# 5409057D.net
KiCad netlist of a schematic drawn in EAGLE
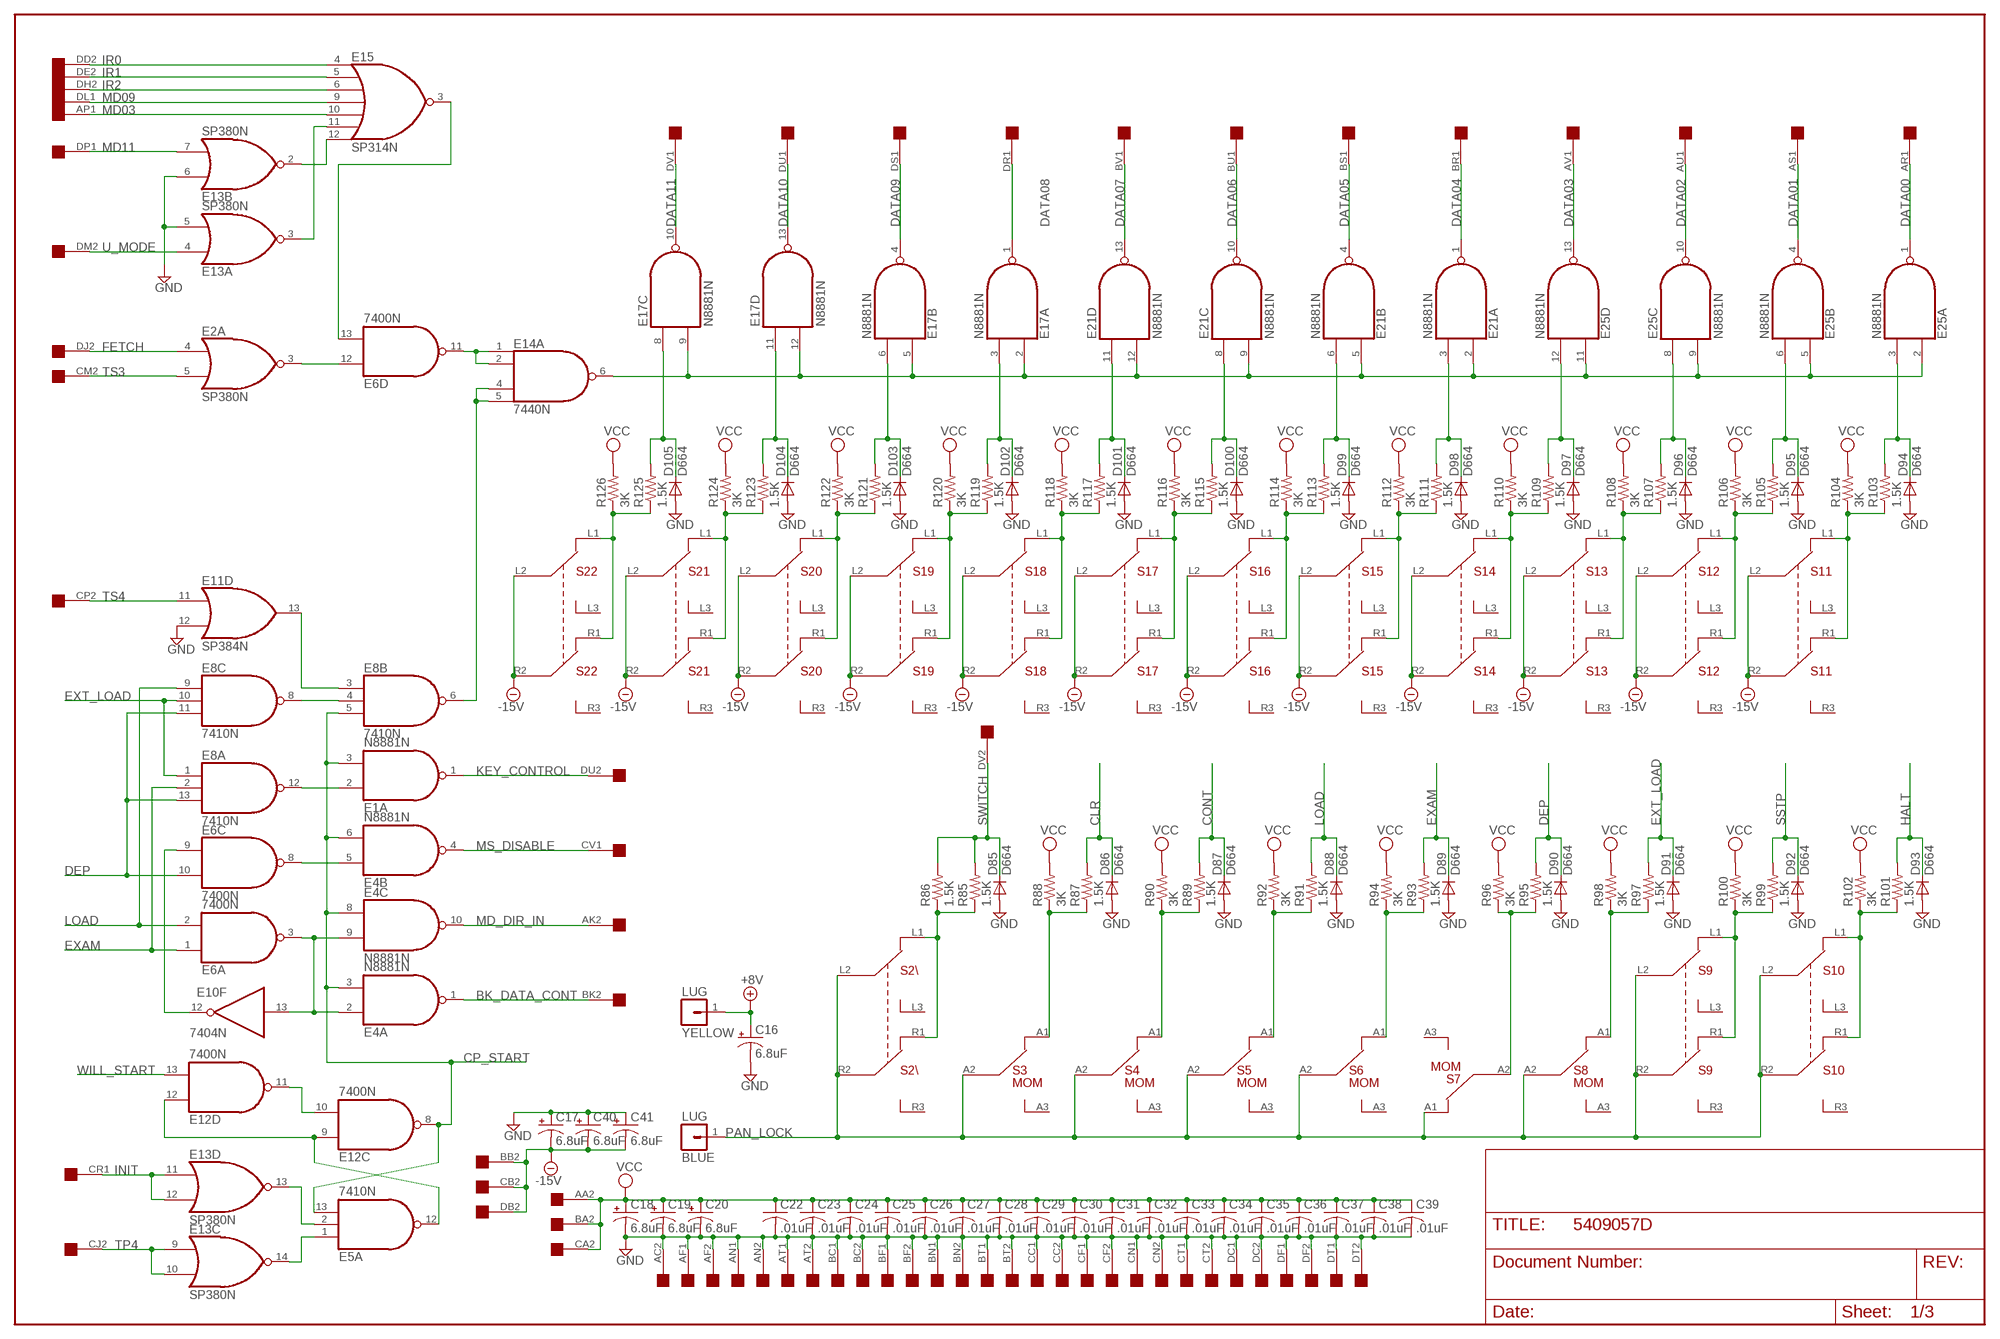
[diagram p0: schematic, sheet 1]
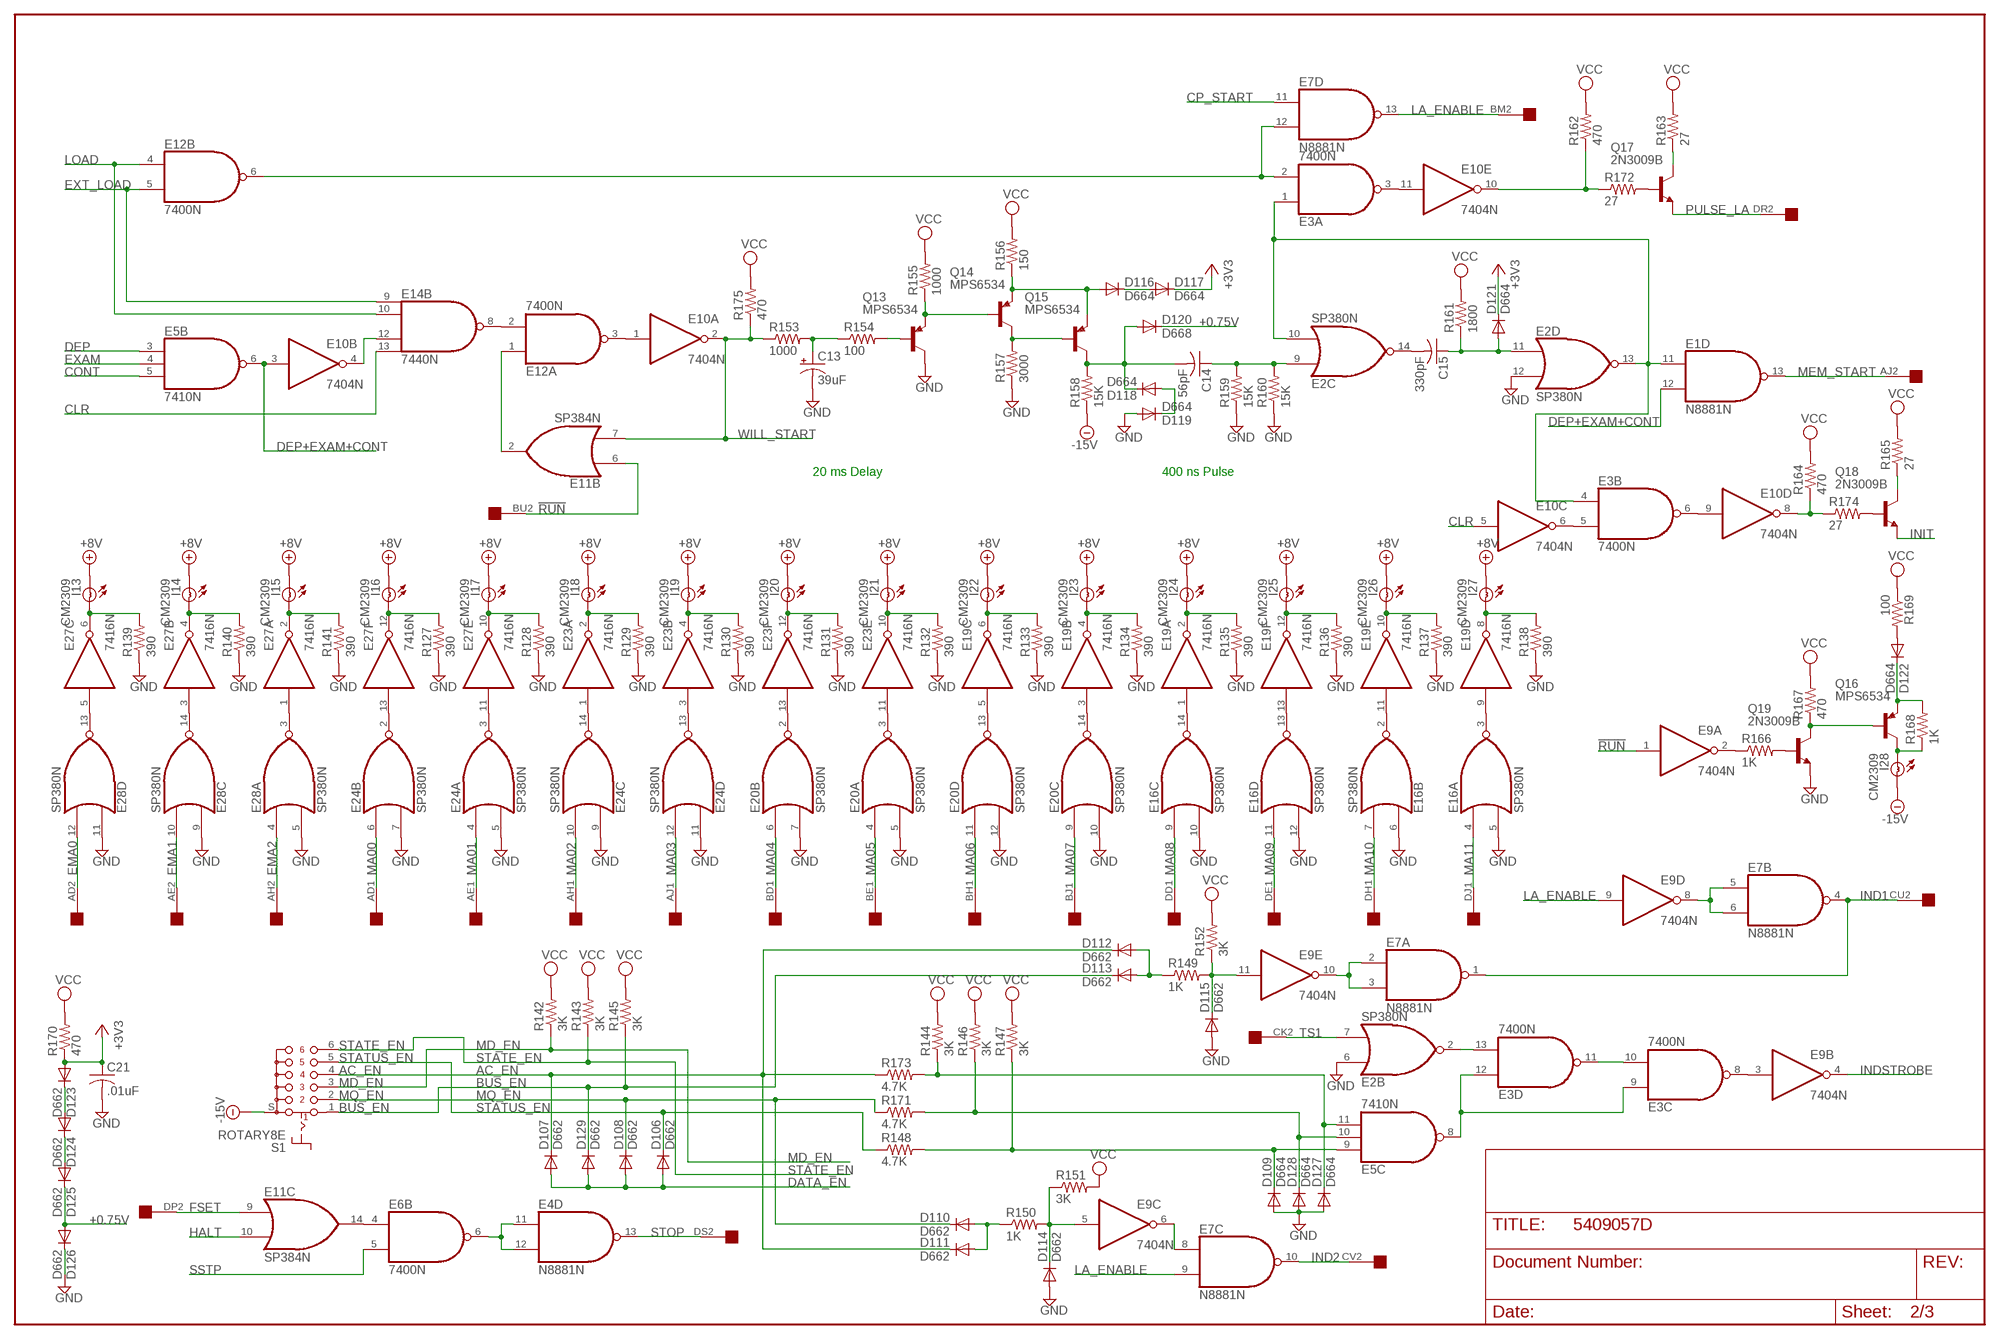
[diagram p1: schematic, sheet 2]
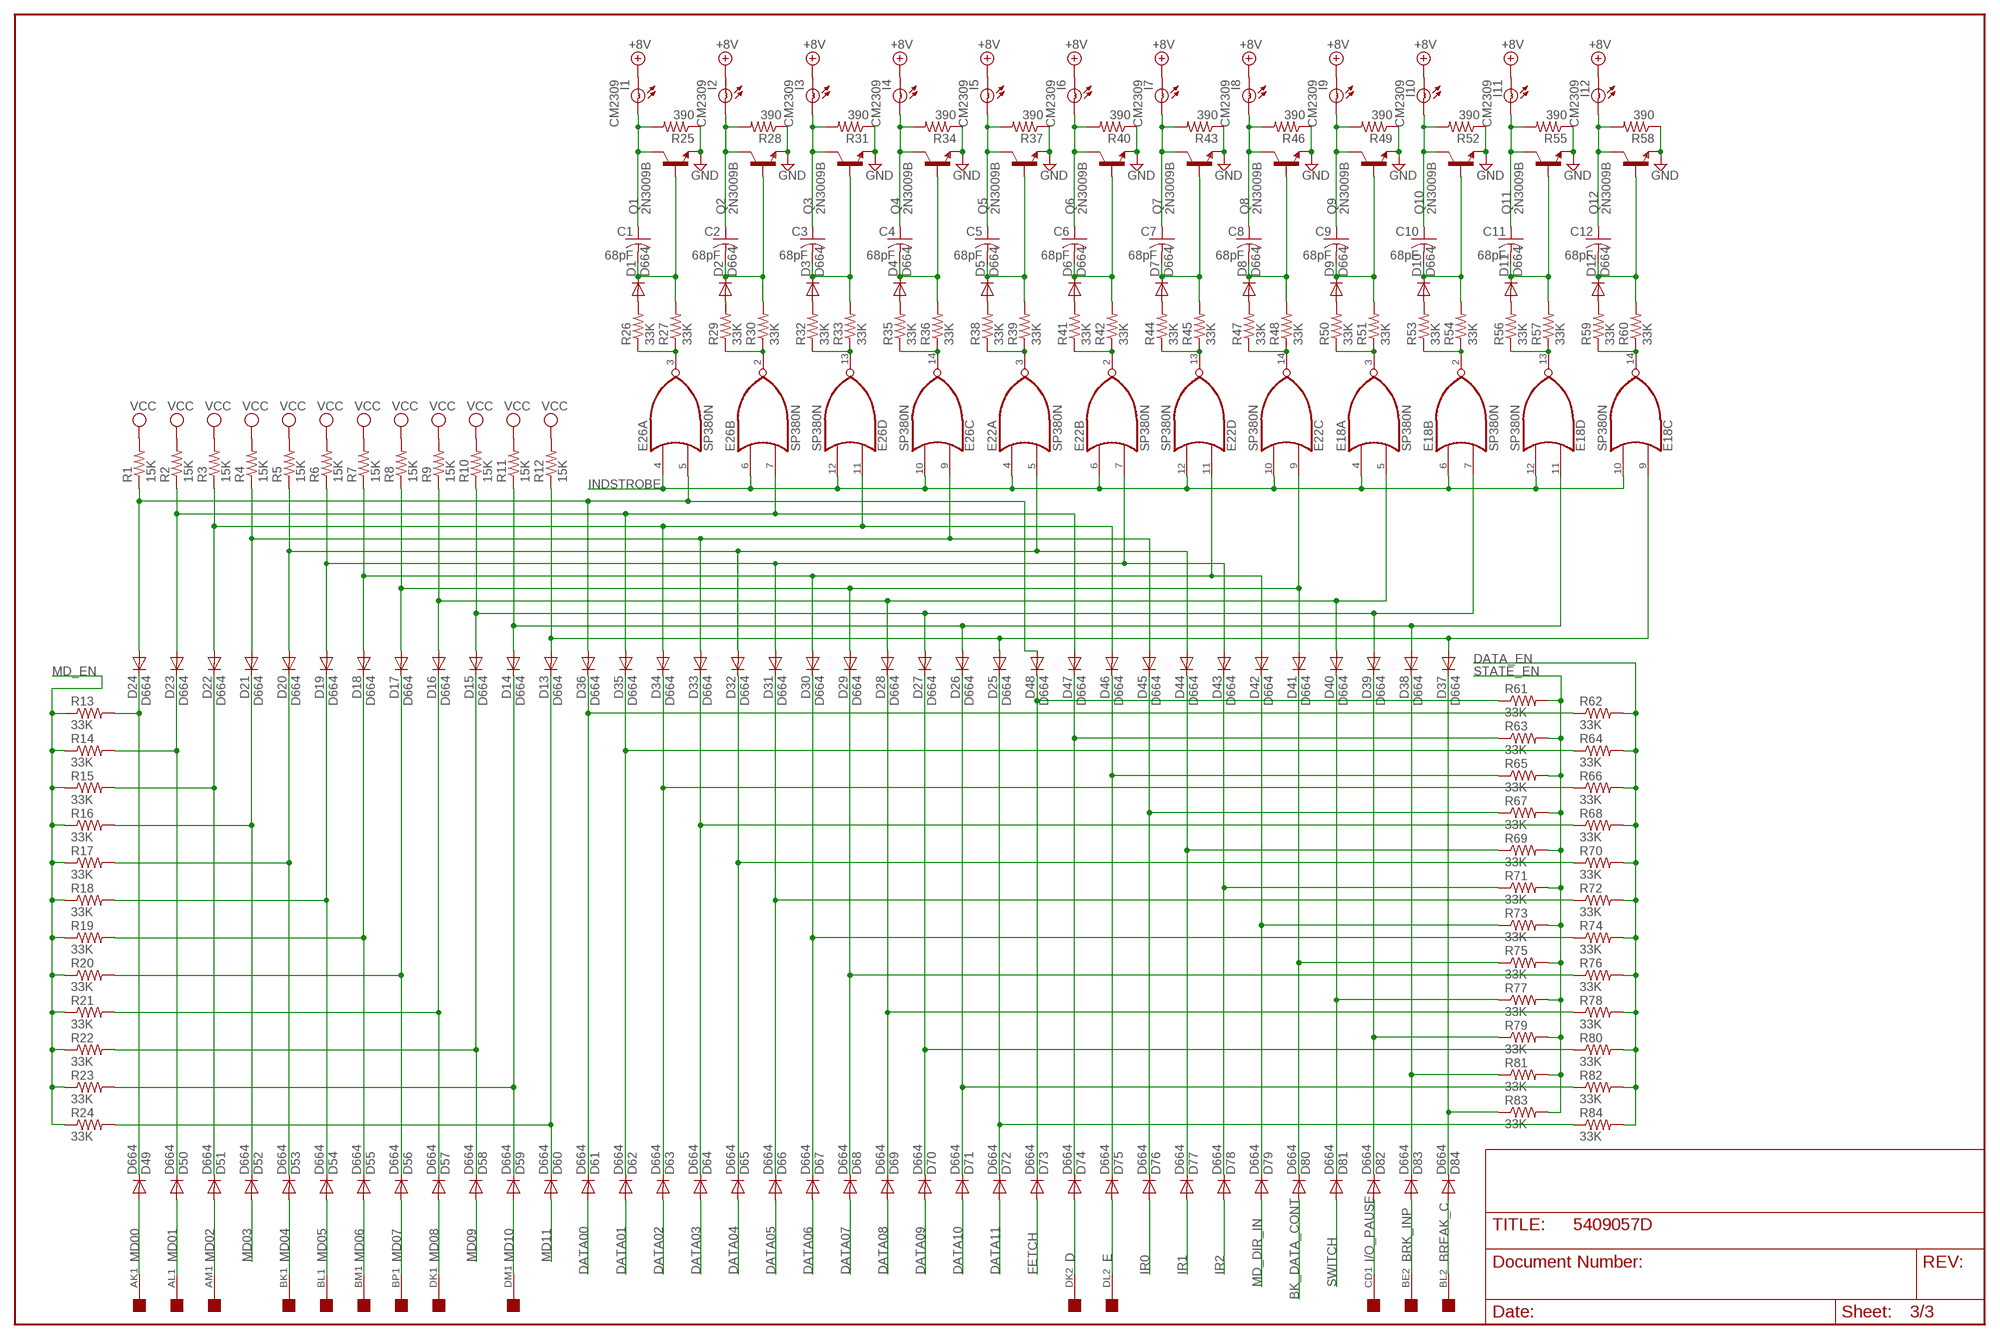
[diagram p2: schematic, sheet 3]

(export (version "E")
  (design (tool "Eeschema 10.0.6"))
  (components
    (comp (ref "BLUE")
      (value "LUG")
      (footprint "eagle-import:SPADELUG")
      (libsource (lib "eagle-import") (part "LUG"))
    )
    (comp (ref "C16")
      (value "6.8uF")
      (footprint "eagle-import:E12-8")
      (libsource (lib "eagle-import") (part "CPOL-USE20-8AXIAL"))
    )
    (comp (ref "C17")
      (value "6.8uF")
      (footprint "eagle-import:E12-8")
      (libsource (lib "eagle-import") (part "CPOL-USE20-8AXIAL"))
    )
    (comp (ref "C18")
      (value "6.8uF")
      (footprint "eagle-import:E12-8")
      (libsource (lib "eagle-import") (part "CPOL-USE20-8AXIAL"))
    )
    (comp (ref "C19")
      (value "6.8uF")
      (footprint "eagle-import:E12-8")
      (libsource (lib "eagle-import") (part "CPOL-USE20-8AXIAL"))
    )
    (comp (ref "C20")
      (value "6.8uF")
      (footprint "eagle-import:E12-8")
      (libsource (lib "eagle-import") (part "CPOL-USE20-8AXIAL"))
    )
    (comp (ref "C22")
      (value ".01uF")
      (footprint "eagle-import:C050-025X075")
      (libsource (lib "eagle-import") (part "C-US050-025X075"))
    )
    (comp (ref "C23")
      (value ".01uF")
      (footprint "eagle-import:C050-025X075")
      (libsource (lib "eagle-import") (part "C-US050-025X075"))
    )
    (comp (ref "C24")
      (value ".01uF")
      (footprint "eagle-import:C050-025X075")
      (libsource (lib "eagle-import") (part "C-US050-025X075"))
    )
    (comp (ref "C25")
      (value ".01uF")
      (footprint "eagle-import:C050-025X075")
      (libsource (lib "eagle-import") (part "C-US050-025X075"))
    )
    (comp (ref "C26")
      (value ".01uF")
      (footprint "eagle-import:C050-025X075")
      (libsource (lib "eagle-import") (part "C-US050-025X075"))
    )
    (comp (ref "C27")
      (value ".01uF")
      (footprint "eagle-import:C050-025X075")
      (libsource (lib "eagle-import") (part "C-US050-025X075"))
    )
    (comp (ref "C28")
      (value ".01uF")
      (footprint "eagle-import:C050-025X075")
      (libsource (lib "eagle-import") (part "C-US050-025X075"))
    )
    (comp (ref "C29")
      (value ".01uF")
      (footprint "eagle-import:C050-025X075")
      (libsource (lib "eagle-import") (part "C-US050-025X075"))
    )
    (comp (ref "C30")
      (value ".01uF")
      (footprint "eagle-import:C050-025X075")
      (libsource (lib "eagle-import") (part "C-US050-025X075"))
    )
    (comp (ref "C31")
      (value ".01uF")
      (footprint "eagle-import:C050-025X075")
      (libsource (lib "eagle-import") (part "C-US050-025X075"))
    )
    (comp (ref "C32")
      (value ".01uF")
      (footprint "eagle-import:C050-025X075")
      (libsource (lib "eagle-import") (part "C-US050-025X075"))
    )
    (comp (ref "C33")
      (value ".01uF")
      (footprint "eagle-import:C050-025X075")
      (libsource (lib "eagle-import") (part "C-US050-025X075"))
    )
    (comp (ref "C34")
      (value ".01uF")
      (footprint "eagle-import:C050-025X075")
      (libsource (lib "eagle-import") (part "C-US050-025X075"))
    )
    (comp (ref "C35")
      (value ".01uF")
      (footprint "eagle-import:C050-025X075")
      (libsource (lib "eagle-import") (part "C-US050-025X075"))
    )
    (comp (ref "C36")
      (value ".01uF")
      (footprint "eagle-import:C050-025X075")
      (libsource (lib "eagle-import") (part "C-US050-025X075"))
    )
    (comp (ref "C37")
      (value ".01uF")
      (footprint "eagle-import:C050-025X075")
      (libsource (lib "eagle-import") (part "C-US050-025X075"))
    )
    (comp (ref "C38")
      (value ".01uF")
      (footprint "eagle-import:C050-025X075")
      (libsource (lib "eagle-import") (part "C-US050-025X075"))
    )
    (comp (ref "C39")
      (value ".01uF")
      (footprint "eagle-import:C050-025X075")
      (libsource (lib "eagle-import") (part "C-US050-025X075"))
    )
    (comp (ref "C40")
      (value "6.8uF")
      (footprint "eagle-import:E12-8")
      (libsource (lib "eagle-import") (part "CPOL-USE20-8AXIAL"))
    )
    (comp (ref "C41")
      (value "6.8uF")
      (footprint "eagle-import:E12-8")
      (libsource (lib "eagle-import") (part "CPOL-USE20-8AXIAL"))
    )
    (comp (ref "D85")
      (value "D664")
      (footprint "eagle-import:DO35-10")
      (libsource (lib "eagle-import") (part "1N4148DO35-10"))
    )
    (comp (ref "D86")
      (value "D664")
      (footprint "eagle-import:DO35-10")
      (libsource (lib "eagle-import") (part "1N4148DO35-10"))
    )
    (comp (ref "D87")
      (value "D664")
      (footprint "eagle-import:DO35-10")
      (libsource (lib "eagle-import") (part "1N4148DO35-10"))
    )
    (comp (ref "D88")
      (value "D664")
      (footprint "eagle-import:DO35-10")
      (libsource (lib "eagle-import") (part "1N4148DO35-10"))
    )
    (comp (ref "D89")
      (value "D664")
      (footprint "eagle-import:DO35-10")
      (libsource (lib "eagle-import") (part "1N4148DO35-10"))
    )
    (comp (ref "D90")
      (value "D664")
      (footprint "eagle-import:DO35-10")
      (libsource (lib "eagle-import") (part "1N4148DO35-10"))
    )
    (comp (ref "D91")
      (value "D664")
      (footprint "eagle-import:DO35-10")
      (libsource (lib "eagle-import") (part "1N4148DO35-10"))
    )
    (comp (ref "D92")
      (value "D664")
      (footprint "eagle-import:DO35-10")
      (libsource (lib "eagle-import") (part "1N4148DO35-10"))
    )
    (comp (ref "D93")
      (value "D664")
      (footprint "eagle-import:DO35-10")
      (libsource (lib "eagle-import") (part "1N4148DO35-10"))
    )
    (comp (ref "D94")
      (value "D664")
      (footprint "eagle-import:DO35-10")
      (libsource (lib "eagle-import") (part "1N4148DO35-10"))
    )
    (comp (ref "D95")
      (value "D664")
      (footprint "eagle-import:DO35-10")
      (libsource (lib "eagle-import") (part "1N4148DO35-10"))
    )
    (comp (ref "D96")
      (value "D664")
      (footprint "eagle-import:DO35-10")
      (libsource (lib "eagle-import") (part "1N4148DO35-10"))
    )
    (comp (ref "D97")
      (value "D664")
      (footprint "eagle-import:DO35-10")
      (libsource (lib "eagle-import") (part "1N4148DO35-10"))
    )
    (comp (ref "D98")
      (value "D664")
      (footprint "eagle-import:DO35-10")
      (libsource (lib "eagle-import") (part "1N4148DO35-10"))
    )
    (comp (ref "D99")
      (value "D664")
      (footprint "eagle-import:DO35-10")
      (libsource (lib "eagle-import") (part "1N4148DO35-10"))
    )
    (comp (ref "D100")
      (value "D664")
      (footprint "eagle-import:DO35-10")
      (libsource (lib "eagle-import") (part "1N4148DO35-10"))
    )
    (comp (ref "D101")
      (value "D664")
      (footprint "eagle-import:DO35-10")
      (libsource (lib "eagle-import") (part "1N4148DO35-10"))
    )
    (comp (ref "D102")
      (value "D664")
      (footprint "eagle-import:DO35-10")
      (libsource (lib "eagle-import") (part "1N4148DO35-10"))
    )
    (comp (ref "D103")
      (value "D664")
      (footprint "eagle-import:DO35-10")
      (libsource (lib "eagle-import") (part "1N4148DO35-10"))
    )
    (comp (ref "D104")
      (value "D664")
      (footprint "eagle-import:DO35-10")
      (libsource (lib "eagle-import") (part "1N4148DO35-10"))
    )
    (comp (ref "D105")
      (value "D664")
      (footprint "eagle-import:DO35-10")
      (libsource (lib "eagle-import") (part "1N4148DO35-10"))
    )
    (comp (ref "E1")
      (value "N8881N")
      (footprint "eagle-import:DIL14")
      (libsource (lib "eagle-import") (part "N8881N"))
    )
    (comp (ref "E2")
      (value "SP380N")
      (footprint "eagle-import:DIL14")
      (libsource (lib "eagle-import") (part "SP380N"))
    )
    (comp (ref "E4")
      (value "N8881N")
      (footprint "eagle-import:DIL14")
      (libsource (lib "eagle-import") (part "N8881N"))
    )
    (comp (ref "E5")
      (value "7410N")
      (footprint "eagle-import:DIL14")
      (libsource (lib "eagle-import") (part "7410N"))
    )
    (comp (ref "E6")
      (value "7400N")
      (footprint "eagle-import:DIL14")
      (libsource (lib "eagle-import") (part "7400N"))
    )
    (comp (ref "E8")
      (value "7410N")
      (footprint "eagle-import:DIL14")
      (libsource (lib "eagle-import") (part "7410N"))
    )
    (comp (ref "E10")
      (value "7404N")
      (footprint "eagle-import:DIL14")
      (libsource (lib "eagle-import") (part "7404N"))
    )
    (comp (ref "E11")
      (value "SP384N")
      (footprint "eagle-import:DIL14")
      (libsource (lib "eagle-import") (part "SP384N"))
    )
    (comp (ref "E12")
      (value "7400N")
      (footprint "eagle-import:DIL14")
      (libsource (lib "eagle-import") (part "7400N"))
    )
    (comp (ref "E13")
      (value "SP380N")
      (footprint "eagle-import:DIL14")
      (libsource (lib "eagle-import") (part "SP380N"))
    )
    (comp (ref "E14")
      (value "7440N")
      (footprint "eagle-import:DIL14")
      (libsource (lib "eagle-import") (part "7420NS"))
    )
    (comp (ref "E15")
      (value "SP314N")
      (footprint "eagle-import:DIL14")
      (libsource (lib "eagle-import") (part "SP314N"))
    )
    (comp (ref "E17")
      (value "N8881N")
      (footprint "eagle-import:DIL14")
      (libsource (lib "eagle-import") (part "N8881N"))
    )
    (comp (ref "E21")
      (value "N8881N")
      (footprint "eagle-import:DIL14")
      (libsource (lib "eagle-import") (part "N8881N"))
    )
    (comp (ref "E25")
      (value "N8881N")
      (footprint "eagle-import:DIL14")
      (libsource (lib "eagle-import") (part "N8881N"))
    )
    (comp (ref "R85")
      (value "1.5K")
      (footprint "eagle-import:0207_10")
      (libsource (lib "eagle-import") (part "R-US_0207/10"))
    )
    (comp (ref "R86")
      (value "1.5K")
      (footprint "eagle-import:0207_10")
      (libsource (lib "eagle-import") (part "R-US_0207/10"))
    )
    (comp (ref "R87")
      (value "1.5K")
      (footprint "eagle-import:0207_10")
      (libsource (lib "eagle-import") (part "R-US_0207/10"))
    )
    (comp (ref "R88")
      (value "3K")
      (footprint "eagle-import:0207_10")
      (libsource (lib "eagle-import") (part "R-US_0207/10"))
    )
    (comp (ref "R89")
      (value "1.5K")
      (footprint "eagle-import:0207_10")
      (libsource (lib "eagle-import") (part "R-US_0207/10"))
    )
    (comp (ref "R90")
      (value "3K")
      (footprint "eagle-import:0207_10")
      (libsource (lib "eagle-import") (part "R-US_0207/10"))
    )
    (comp (ref "R91")
      (value "1.5K")
      (footprint "eagle-import:0207_10")
      (libsource (lib "eagle-import") (part "R-US_0207/10"))
    )
    (comp (ref "R92")
      (value "3K")
      (footprint "eagle-import:0207_10")
      (libsource (lib "eagle-import") (part "R-US_0207/10"))
    )
    (comp (ref "R93")
      (value "1.5K")
      (footprint "eagle-import:0207_10")
      (libsource (lib "eagle-import") (part "R-US_0207/10"))
    )
    (comp (ref "R94")
      (value "3K")
      (footprint "eagle-import:0207_10")
      (libsource (lib "eagle-import") (part "R-US_0207/10"))
    )
    (comp (ref "R95")
      (value "1.5K")
      (footprint "eagle-import:0207_10")
      (libsource (lib "eagle-import") (part "R-US_0207/10"))
    )
    (comp (ref "R96")
      (value "3K")
      (footprint "eagle-import:0207_10")
      (libsource (lib "eagle-import") (part "R-US_0207/10"))
    )
    (comp (ref "R97")
      (value "1.5K")
      (footprint "eagle-import:0207_10")
      (libsource (lib "eagle-import") (part "R-US_0207/10"))
    )
    (comp (ref "R98")
      (value "3K")
      (footprint "eagle-import:0207_10")
      (libsource (lib "eagle-import") (part "R-US_0207/10"))
    )
    (comp (ref "R99")
      (value "1.5K")
      (footprint "eagle-import:0207_10")
      (libsource (lib "eagle-import") (part "R-US_0207/10"))
    )
    (comp (ref "R100")
      (value "3K")
      (footprint "eagle-import:0207_10")
      (libsource (lib "eagle-import") (part "R-US_0207/10"))
    )
    (comp (ref "R101")
      (value "1.5K")
      (footprint "eagle-import:0207_10")
      (libsource (lib "eagle-import") (part "R-US_0207/10"))
    )
    (comp (ref "R102")
      (value "3K")
      (footprint "eagle-import:0207_10")
      (libsource (lib "eagle-import") (part "R-US_0207/10"))
    )
    (comp (ref "R103")
      (value "1.5K")
      (footprint "eagle-import:0207_10")
      (libsource (lib "eagle-import") (part "R-US_0207/10"))
    )
    (comp (ref "R104")
      (value "3K")
      (footprint "eagle-import:0207_10")
      (libsource (lib "eagle-import") (part "R-US_0207/10"))
    )
    (comp (ref "R105")
      (value "1.5K")
      (footprint "eagle-import:0207_10")
      (libsource (lib "eagle-import") (part "R-US_0207/10"))
    )
    (comp (ref "R106")
      (value "3K")
      (footprint "eagle-import:0207_10")
      (libsource (lib "eagle-import") (part "R-US_0207/10"))
    )
    (comp (ref "R107")
      (value "1.5K")
      (footprint "eagle-import:0207_10")
      (libsource (lib "eagle-import") (part "R-US_0207/10"))
    )
    (comp (ref "R108")
      (value "3K")
      (footprint "eagle-import:0207_10")
      (libsource (lib "eagle-import") (part "R-US_0207/10"))
    )
    (comp (ref "R109")
      (value "1.5K")
      (footprint "eagle-import:0207_10")
      (libsource (lib "eagle-import") (part "R-US_0207/10"))
    )
    (comp (ref "R110")
      (value "3K")
      (footprint "eagle-import:0207_10")
      (libsource (lib "eagle-import") (part "R-US_0207/10"))
    )
    (comp (ref "R111")
      (value "1.5K")
      (footprint "eagle-import:0207_10")
      (libsource (lib "eagle-import") (part "R-US_0207/10"))
    )
    (comp (ref "R112")
      (value "3K")
      (footprint "eagle-import:0207_10")
      (libsource (lib "eagle-import") (part "R-US_0207/10"))
    )
    (comp (ref "R113")
      (value "1.5K")
      (footprint "eagle-import:0207_10")
      (libsource (lib "eagle-import") (part "R-US_0207/10"))
    )
    (comp (ref "R114")
      (value "3K")
      (footprint "eagle-import:0207_10")
      (libsource (lib "eagle-import") (part "R-US_0207/10"))
    )
    (comp (ref "R115")
      (value "1.5K")
      (footprint "eagle-import:0207_10")
      (libsource (lib "eagle-import") (part "R-US_0207/10"))
    )
    (comp (ref "R116")
      (value "3K")
      (footprint "eagle-import:0207_10")
      (libsource (lib "eagle-import") (part "R-US_0207/10"))
    )
    (comp (ref "R117")
      (value "1.5K")
      (footprint "eagle-import:0207_10")
      (libsource (lib "eagle-import") (part "R-US_0207/10"))
    )
    (comp (ref "R118")
      (value "3K")
      (footprint "eagle-import:0207_10")
      (libsource (lib "eagle-import") (part "R-US_0207/10"))
    )
    (comp (ref "R119")
      (value "1.5K")
      (footprint "eagle-import:0207_10")
      (libsource (lib "eagle-import") (part "R-US_0207/10"))
    )
    (comp (ref "R120")
      (value "3K")
      (footprint "eagle-import:0207_10")
      (libsource (lib "eagle-import") (part "R-US_0207/10"))
    )
    (comp (ref "R121")
      (value "1.5K")
      (footprint "eagle-import:0207_10")
      (libsource (lib "eagle-import") (part "R-US_0207/10"))
    )
    (comp (ref "R122")
      (value "3K")
      (footprint "eagle-import:0207_10")
      (libsource (lib "eagle-import") (part "R-US_0207/10"))
    )
    (comp (ref "R123")
      (value "1.5K")
      (footprint "eagle-import:0207_10")
      (libsource (lib "eagle-import") (part "R-US_0207/10"))
    )
    (comp (ref "R124")
      (value "3K")
      (footprint "eagle-import:0207_10")
      (libsource (lib "eagle-import") (part "R-US_0207/10"))
    )
    (comp (ref "R125")
      (value "1.5K")
      (footprint "eagle-import:0207_10")
      (libsource (lib "eagle-import") (part "R-US_0207/10"))
    )
    (comp (ref "R126")
      (value "3K")
      (footprint "eagle-import:0207_10")
      (libsource (lib "eagle-import") (part "R-US_0207/10"))
    )
    (comp (ref "S2\\")
      (value "DPDT8I")
      (footprint "eagle-import:DPDT8I")
      (libsource (lib "eagle-import") (part "DPDT8I"))
    )
    (comp (ref "S3")
      (value "SPDT8I")
      (footprint "eagle-import:SPDT8I")
      (libsource (lib "eagle-import") (part "SPDT8I"))
    )
    (comp (ref "S4")
      (value "SPDT8I")
      (footprint "eagle-import:SPDT8I")
      (libsource (lib "eagle-import") (part "SPDT8I"))
    )
    (comp (ref "S5")
      (value "SPDT8I")
      (footprint "eagle-import:SPDT8I")
      (libsource (lib "eagle-import") (part "SPDT8I"))
    )
    (comp (ref "S6")
      (value "SPDT8I")
      (footprint "eagle-import:SPDT8I")
      (libsource (lib "eagle-import") (part "SPDT8I"))
    )
    (comp (ref "S7")
      (value "SPDT8I")
      (footprint "eagle-import:SPDT8I")
      (libsource (lib "eagle-import") (part "SPDT8I"))
    )
    (comp (ref "S8")
      (value "SPDT8I")
      (footprint "eagle-import:SPDT8I")
      (libsource (lib "eagle-import") (part "SPDT8I"))
    )
    (comp (ref "S9")
      (value "DPDT8I")
      (footprint "eagle-import:DPDT8I")
      (libsource (lib "eagle-import") (part "DPDT8I"))
    )
    (comp (ref "S10")
      (value "DPDT8I")
      (footprint "eagle-import:DPDT8I")
      (libsource (lib "eagle-import") (part "DPDT8I"))
    )
    (comp (ref "S11")
      (value "DPDT8I")
      (footprint "eagle-import:DPDT8I")
      (libsource (lib "eagle-import") (part "DPDT8I"))
    )
    (comp (ref "S12")
      (value "DPDT8I")
      (footprint "eagle-import:DPDT8I")
      (libsource (lib "eagle-import") (part "DPDT8I"))
    )
    (comp (ref "S13")
      (value "DPDT8I")
      (footprint "eagle-import:DPDT8I")
      (libsource (lib "eagle-import") (part "DPDT8I"))
    )
    (comp (ref "S14")
      (value "DPDT8I")
      (footprint "eagle-import:DPDT8I")
      (libsource (lib "eagle-import") (part "DPDT8I"))
    )
    (comp (ref "S15")
      (value "DPDT8I")
      (footprint "eagle-import:DPDT8I")
      (libsource (lib "eagle-import") (part "DPDT8I"))
    )
    (comp (ref "S16")
      (value "DPDT8I")
      (footprint "eagle-import:DPDT8I")
      (libsource (lib "eagle-import") (part "DPDT8I"))
    )
    (comp (ref "S17")
      (value "DPDT8I")
      (footprint "eagle-import:DPDT8I")
      (libsource (lib "eagle-import") (part "DPDT8I"))
    )
    (comp (ref "S18")
      (value "DPDT8I")
      (footprint "eagle-import:DPDT8I")
      (libsource (lib "eagle-import") (part "DPDT8I"))
    )
    (comp (ref "S19")
      (value "DPDT8I")
      (footprint "eagle-import:DPDT8I")
      (libsource (lib "eagle-import") (part "DPDT8I"))
    )
    (comp (ref "S20")
      (value "DPDT8I")
      (footprint "eagle-import:DPDT8I")
      (libsource (lib "eagle-import") (part "DPDT8I"))
    )
    (comp (ref "S21")
      (value "DPDT8I")
      (footprint "eagle-import:DPDT8I")
      (libsource (lib "eagle-import") (part "DPDT8I"))
    )
    (comp (ref "S22")
      (value "DPDT8I")
      (footprint "eagle-import:DPDT8I")
      (libsource (lib "eagle-import") (part "DPDT8I"))
    )
    (comp (ref "U$2")
      (value "QUAD")
      (footprint "eagle-import:EDGE-CON8")
      (libsource (lib "eagle-import") (part "QUAD"))
    )
    (comp (ref "YELLOW")
      (value "LUG")
      (footprint "eagle-import:SPADELUG")
      (libsource (lib "eagle-import") (part "LUG"))
    )
    (comp (ref "C1")
      (value "68pF")
      (footprint "eagle-import:C050-025X075")
      (libsource (lib "eagle-import") (part "C-US050-025X075"))
    )
    (comp (ref "C2")
      (value "68pF")
      (footprint "eagle-import:C050-025X075")
      (libsource (lib "eagle-import") (part "C-US050-025X075"))
    )
    (comp (ref "C3")
      (value "68pF")
      (footprint "eagle-import:C050-025X075")
      (libsource (lib "eagle-import") (part "C-US050-025X075"))
    )
    (comp (ref "C4")
      (value "68pF")
      (footprint "eagle-import:C050-025X075")
      (libsource (lib "eagle-import") (part "C-US050-025X075"))
    )
    (comp (ref "C5")
      (value "68pF")
      (footprint "eagle-import:C050-025X075")
      (libsource (lib "eagle-import") (part "C-US050-025X075"))
    )
    (comp (ref "C6")
      (value "68pF")
      (footprint "eagle-import:C050-025X075")
      (libsource (lib "eagle-import") (part "C-US050-025X075"))
    )
    (comp (ref "C7")
      (value "68pF")
      (footprint "eagle-import:C050-025X075")
      (libsource (lib "eagle-import") (part "C-US050-025X075"))
    )
    (comp (ref "C8")
      (value "68pF")
      (footprint "eagle-import:C050-025X075")
      (libsource (lib "eagle-import") (part "C-US050-025X075"))
    )
    (comp (ref "C9")
      (value "68pF")
      (footprint "eagle-import:C050-025X075")
      (libsource (lib "eagle-import") (part "C-US050-025X075"))
    )
    (comp (ref "C10")
      (value "68pF")
      (footprint "eagle-import:C050-025X075")
      (libsource (lib "eagle-import") (part "C-US050-025X075"))
    )
    (comp (ref "C11")
      (value "68pF")
      (footprint "eagle-import:C050-025X075")
      (libsource (lib "eagle-import") (part "C-US050-025X075"))
    )
    (comp (ref "C12")
      (value "68pF")
      (footprint "eagle-import:C050-025X075")
      (libsource (lib "eagle-import") (part "C-US050-025X075"))
    )
    (comp (ref "D1")
      (value "D664")
      (footprint "eagle-import:DO35-10")
      (libsource (lib "eagle-import") (part "1N4148DO35-10"))
    )
    (comp (ref "D2")
      (value "D664")
      (footprint "eagle-import:DO35-10")
      (libsource (lib "eagle-import") (part "1N4148DO35-10"))
    )
    (comp (ref "D3")
      (value "D664")
      (footprint "eagle-import:DO35-10")
      (libsource (lib "eagle-import") (part "1N4148DO35-10"))
    )
    (comp (ref "D4")
      (value "D664")
      (footprint "eagle-import:DO35-10")
      (libsource (lib "eagle-import") (part "1N4148DO35-10"))
    )
    (comp (ref "D5")
      (value "D664")
      (footprint "eagle-import:DO35-10")
      (libsource (lib "eagle-import") (part "1N4148DO35-10"))
    )
    (comp (ref "D6")
      (value "D664")
      (footprint "eagle-import:DO35-10")
      (libsource (lib "eagle-import") (part "1N4148DO35-10"))
    )
    (comp (ref "D7")
      (value "D664")
      (footprint "eagle-import:DO35-10")
      (libsource (lib "eagle-import") (part "1N4148DO35-10"))
    )
    (comp (ref "D8")
      (value "D664")
      (footprint "eagle-import:DO35-10")
      (libsource (lib "eagle-import") (part "1N4148DO35-10"))
    )
    (comp (ref "D9")
      (value "D664")
      (footprint "eagle-import:DO35-10")
      (libsource (lib "eagle-import") (part "1N4148DO35-10"))
    )
    (comp (ref "D10")
      (value "D664")
      (footprint "eagle-import:DO35-10")
      (libsource (lib "eagle-import") (part "1N4148DO35-10"))
    )
    (comp (ref "D11")
      (value "D664")
      (footprint "eagle-import:DO35-10")
      (libsource (lib "eagle-import") (part "1N4148DO35-10"))
    )
    (comp (ref "D12")
      (value "D664")
      (footprint "eagle-import:DO35-10")
      (libsource (lib "eagle-import") (part "1N4148DO35-10"))
    )
    (comp (ref "D13")
      (value "D664")
      (footprint "eagle-import:DO35-10")
      (libsource (lib "eagle-import") (part "1N4148DO35-10"))
    )
    (comp (ref "D14")
      (value "D664")
      (footprint "eagle-import:DO35-10")
      (libsource (lib "eagle-import") (part "1N4148DO35-10"))
    )
    (comp (ref "D15")
      (value "D664")
      (footprint "eagle-import:DO35-10")
      (libsource (lib "eagle-import") (part "1N4148DO35-10"))
    )
    (comp (ref "D16")
      (value "D664")
      (footprint "eagle-import:DO35-10")
      (libsource (lib "eagle-import") (part "1N4148DO35-10"))
    )
    (comp (ref "D17")
      (value "D664")
      (footprint "eagle-import:DO35-10")
      (libsource (lib "eagle-import") (part "1N4148DO35-10"))
    )
    (comp (ref "D18")
      (value "D664")
      (footprint "eagle-import:DO35-10")
      (libsource (lib "eagle-import") (part "1N4148DO35-10"))
    )
    (comp (ref "D19")
      (value "D664")
      (footprint "eagle-import:DO35-10")
      (libsource (lib "eagle-import") (part "1N4148DO35-10"))
    )
    (comp (ref "D20")
      (value "D664")
      (footprint "eagle-import:DO35-10")
      (libsource (lib "eagle-import") (part "1N4148DO35-10"))
    )
    (comp (ref "D21")
      (value "D664")
      (footprint "eagle-import:DO35-10")
      (libsource (lib "eagle-import") (part "1N4148DO35-10"))
    )
    (comp (ref "D22")
      (value "D664")
      (footprint "eagle-import:DO35-10")
      (libsource (lib "eagle-import") (part "1N4148DO35-10"))
    )
    (comp (ref "D23")
      (value "D664")
      (footprint "eagle-import:DO35-10")
      (libsource (lib "eagle-import") (part "1N4148DO35-10"))
    )
    (comp (ref "D24")
      (value "D664")
      (footprint "eagle-import:DO35-10")
      (libsource (lib "eagle-import") (part "1N4148DO35-10"))
    )
    (comp (ref "D25")
      (value "D664")
      (footprint "eagle-import:DO35-10")
      (libsource (lib "eagle-import") (part "1N4148DO35-10"))
    )
    (comp (ref "D26")
      (value "D664")
      (footprint "eagle-import:DO35-10")
      (libsource (lib "eagle-import") (part "1N4148DO35-10"))
    )
    (comp (ref "D27")
      (value "D664")
      (footprint "eagle-import:DO35-10")
      (libsource (lib "eagle-import") (part "1N4148DO35-10"))
    )
    (comp (ref "D28")
      (value "D664")
      (footprint "eagle-import:DO35-10")
      (libsource (lib "eagle-import") (part "1N4148DO35-10"))
    )
    (comp (ref "D29")
      (value "D664")
      (footprint "eagle-import:DO35-10")
      (libsource (lib "eagle-import") (part "1N4148DO35-10"))
    )
    (comp (ref "D30")
      (value "D664")
      (footprint "eagle-import:DO35-10")
      (libsource (lib "eagle-import") (part "1N4148DO35-10"))
    )
    (comp (ref "D31")
      (value "D664")
      (footprint "eagle-import:DO35-10")
      (libsource (lib "eagle-import") (part "1N4148DO35-10"))
    )
    (comp (ref "D32")
      (value "D664")
      (footprint "eagle-import:DO35-10")
      (libsource (lib "eagle-import") (part "1N4148DO35-10"))
    )
    (comp (ref "D33")
      (value "D664")
      (footprint "eagle-import:DO35-10")
      (libsource (lib "eagle-import") (part "1N4148DO35-10"))
    )
    (comp (ref "D34")
      (value "D664")
      (footprint "eagle-import:DO35-10")
      (libsource (lib "eagle-import") (part "1N4148DO35-10"))
    )
    (comp (ref "D35")
      (value "D664")
      (footprint "eagle-import:DO35-10")
      (libsource (lib "eagle-import") (part "1N4148DO35-10"))
    )
    (comp (ref "D36")
      (value "D664")
      (footprint "eagle-import:DO35-10")
      (libsource (lib "eagle-import") (part "1N4148DO35-10"))
    )
    (comp (ref "D37")
      (value "D664")
      (footprint "eagle-import:DO35-10")
      (libsource (lib "eagle-import") (part "1N4148DO35-10"))
    )
    (comp (ref "D38")
      (value "D664")
      (footprint "eagle-import:DO35-10")
      (libsource (lib "eagle-import") (part "1N4148DO35-10"))
    )
    (comp (ref "D39")
      (value "D664")
      (footprint "eagle-import:DO35-10")
      (libsource (lib "eagle-import") (part "1N4148DO35-10"))
    )
    (comp (ref "D40")
      (value "D664")
      (footprint "eagle-import:DO35-10")
      (libsource (lib "eagle-import") (part "1N4148DO35-10"))
    )
    (comp (ref "D41")
      (value "D664")
      (footprint "eagle-import:DO35-10")
      (libsource (lib "eagle-import") (part "1N4148DO35-10"))
    )
    (comp (ref "D42")
      (value "D664")
      (footprint "eagle-import:DO35-10")
      (libsource (lib "eagle-import") (part "1N4148DO35-10"))
    )
    (comp (ref "D43")
      (value "D664")
      (footprint "eagle-import:DO35-10")
      (libsource (lib "eagle-import") (part "1N4148DO35-10"))
    )
    (comp (ref "D44")
      (value "D664")
      (footprint "eagle-import:DO35-10")
      (libsource (lib "eagle-import") (part "1N4148DO35-10"))
    )
    (comp (ref "D45")
      (value "D664")
      (footprint "eagle-import:DO35-10")
      (libsource (lib "eagle-import") (part "1N4148DO35-10"))
    )
    (comp (ref "D46")
      (value "D664")
      (footprint "eagle-import:DO35-10")
      (libsource (lib "eagle-import") (part "1N4148DO35-10"))
    )
    (comp (ref "D47")
      (value "D664")
      (footprint "eagle-import:DO35-10")
      (libsource (lib "eagle-import") (part "1N4148DO35-10"))
    )
    (comp (ref "D48")
      (value "D664")
      (footprint "eagle-import:DO35-10")
      (libsource (lib "eagle-import") (part "1N4148DO35-10"))
    )
    (comp (ref "D49")
      (value "D664")
      (footprint "eagle-import:DO35-10")
      (libsource (lib "eagle-import") (part "1N4148DO35-10"))
    )
    (comp (ref "D50")
      (value "D664")
      (footprint "eagle-import:DO35-10")
      (libsource (lib "eagle-import") (part "1N4148DO35-10"))
    )
    (comp (ref "D51")
      (value "D664")
      (footprint "eagle-import:DO35-10")
      (libsource (lib "eagle-import") (part "1N4148DO35-10"))
    )
    (comp (ref "D52")
      (value "D664")
      (footprint "eagle-import:DO35-10")
      (libsource (lib "eagle-import") (part "1N4148DO35-10"))
    )
    (comp (ref "D53")
      (value "D664")
      (footprint "eagle-import:DO35-10")
      (libsource (lib "eagle-import") (part "1N4148DO35-10"))
    )
    (comp (ref "D54")
      (value "D664")
      (footprint "eagle-import:DO35-10")
      (libsource (lib "eagle-import") (part "1N4148DO35-10"))
    )
    (comp (ref "D55")
      (value "D664")
      (footprint "eagle-import:DO35-10")
      (libsource (lib "eagle-import") (part "1N4148DO35-10"))
    )
    (comp (ref "D56")
      (value "D664")
      (footprint "eagle-import:DO35-10")
      (libsource (lib "eagle-import") (part "1N4148DO35-10"))
    )
    (comp (ref "D57")
      (value "D664")
      (footprint "eagle-import:DO35-10")
      (libsource (lib "eagle-import") (part "1N4148DO35-10"))
    )
    (comp (ref "D58")
      (value "D664")
      (footprint "eagle-import:DO35-10")
      (libsource (lib "eagle-import") (part "1N4148DO35-10"))
    )
    (comp (ref "D59")
      (value "D664")
      (footprint "eagle-import:DO35-10")
      (libsource (lib "eagle-import") (part "1N4148DO35-10"))
    )
    (comp (ref "D60")
      (value "D664")
      (footprint "eagle-import:DO35-10")
      (libsource (lib "eagle-import") (part "1N4148DO35-10"))
    )
    (comp (ref "D61")
      (value "D664")
      (footprint "eagle-import:DO35-10")
      (libsource (lib "eagle-import") (part "1N4148DO35-10"))
    )
    (comp (ref "D62")
      (value "D664")
      (footprint "eagle-import:DO35-10")
      (libsource (lib "eagle-import") (part "1N4148DO35-10"))
    )
    (comp (ref "D63")
      (value "D664")
      (footprint "eagle-import:DO35-10")
      (libsource (lib "eagle-import") (part "1N4148DO35-10"))
    )
    (comp (ref "D64")
      (value "D664")
      (footprint "eagle-import:DO35-10")
      (libsource (lib "eagle-import") (part "1N4148DO35-10"))
    )
    (comp (ref "D65")
      (value "D664")
      (footprint "eagle-import:DO35-10")
      (libsource (lib "eagle-import") (part "1N4148DO35-10"))
    )
    (comp (ref "D66")
      (value "D664")
      (footprint "eagle-import:DO35-10")
      (libsource (lib "eagle-import") (part "1N4148DO35-10"))
    )
    (comp (ref "D67")
      (value "D664")
      (footprint "eagle-import:DO35-10")
      (libsource (lib "eagle-import") (part "1N4148DO35-10"))
    )
    (comp (ref "D68")
      (value "D664")
      (footprint "eagle-import:DO35-10")
      (libsource (lib "eagle-import") (part "1N4148DO35-10"))
    )
    (comp (ref "D69")
      (value "D664")
      (footprint "eagle-import:DO35-10")
      (libsource (lib "eagle-import") (part "1N4148DO35-10"))
    )
    (comp (ref "D70")
      (value "D664")
      (footprint "eagle-import:DO35-10")
      (libsource (lib "eagle-import") (part "1N4148DO35-10"))
    )
    (comp (ref "D71")
      (value "D664")
      (footprint "eagle-import:DO35-10")
      (libsource (lib "eagle-import") (part "1N4148DO35-10"))
    )
    (comp (ref "D72")
      (value "D664")
      (footprint "eagle-import:DO35-10")
      (libsource (lib "eagle-import") (part "1N4148DO35-10"))
    )
    (comp (ref "D73")
      (value "D664")
      (footprint "eagle-import:DO35-10")
      (libsource (lib "eagle-import") (part "1N4148DO35-10"))
    )
    (comp (ref "D74")
      (value "D664")
      (footprint "eagle-import:DO35-10")
      (libsource (lib "eagle-import") (part "1N4148DO35-10"))
    )
    (comp (ref "D75")
      (value "D664")
      (footprint "eagle-import:DO35-10")
      (libsource (lib "eagle-import") (part "1N4148DO35-10"))
    )
    (comp (ref "D76")
      (value "D664")
      (footprint "eagle-import:DO35-10")
      (libsource (lib "eagle-import") (part "1N4148DO35-10"))
    )
    (comp (ref "D77")
      (value "D664")
      (footprint "eagle-import:DO35-10")
      (libsource (lib "eagle-import") (part "1N4148DO35-10"))
    )
    (comp (ref "D78")
      (value "D664")
      (footprint "eagle-import:DO35-10")
      (libsource (lib "eagle-import") (part "1N4148DO35-10"))
    )
    (comp (ref "D79")
      (value "D664")
      (footprint "eagle-import:DO35-10")
      (libsource (lib "eagle-import") (part "1N4148DO35-10"))
    )
    (comp (ref "D80")
      (value "D664")
      (footprint "eagle-import:DO35-10")
      (libsource (lib "eagle-import") (part "1N4148DO35-10"))
    )
    (comp (ref "D81")
      (value "D664")
      (footprint "eagle-import:DO35-10")
      (libsource (lib "eagle-import") (part "1N4148DO35-10"))
    )
    (comp (ref "D82")
      (value "D664")
      (footprint "eagle-import:DO35-10")
      (libsource (lib "eagle-import") (part "1N4148DO35-10"))
    )
    (comp (ref "D83")
      (value "D664")
      (footprint "eagle-import:DO35-10")
      (libsource (lib "eagle-import") (part "1N4148DO35-10"))
    )
    (comp (ref "D84")
      (value "D664")
      (footprint "eagle-import:DO35-10")
      (libsource (lib "eagle-import") (part "1N4148DO35-10"))
    )
    (comp (ref "E18")
      (value "SP380N")
      (footprint "eagle-import:DIL14")
      (libsource (lib "eagle-import") (part "SP380N"))
    )
    (comp (ref "E22")
      (value "SP380N")
      (footprint "eagle-import:DIL14")
      (libsource (lib "eagle-import") (part "SP380N"))
    )
    (comp (ref "E26")
      (value "SP380N")
      (footprint "eagle-import:DIL14")
      (libsource (lib "eagle-import") (part "SP380N"))
    )
    (comp (ref "I1")
      (value "CM2309")
      (footprint "eagle-import:BULB")
      (libsource (lib "eagle-import") (part "BULB"))
    )
    (comp (ref "I2")
      (value "CM2309")
      (footprint "eagle-import:BULB")
      (libsource (lib "eagle-import") (part "BULB"))
    )
    (comp (ref "I3")
      (value "CM2309")
      (footprint "eagle-import:BULB")
      (libsource (lib "eagle-import") (part "BULB"))
    )
    (comp (ref "I4")
      (value "CM2309")
      (footprint "eagle-import:BULB")
      (libsource (lib "eagle-import") (part "BULB"))
    )
    (comp (ref "I5")
      (value "CM2309")
      (footprint "eagle-import:BULB")
      (libsource (lib "eagle-import") (part "BULB"))
    )
    (comp (ref "I6")
      (value "CM2309")
      (footprint "eagle-import:BULB")
      (libsource (lib "eagle-import") (part "BULB"))
    )
    (comp (ref "I7")
      (value "CM2309")
      (footprint "eagle-import:BULB")
      (libsource (lib "eagle-import") (part "BULB"))
    )
    (comp (ref "I8")
      (value "CM2309")
      (footprint "eagle-import:BULB")
      (libsource (lib "eagle-import") (part "BULB"))
    )
    (comp (ref "I9")
      (value "CM2309")
      (footprint "eagle-import:BULB")
      (libsource (lib "eagle-import") (part "BULB"))
    )
    (comp (ref "I10")
      (value "CM2309")
      (footprint "eagle-import:BULB")
      (libsource (lib "eagle-import") (part "BULB"))
    )
    (comp (ref "I11")
      (value "CM2309")
      (footprint "eagle-import:BULB")
      (libsource (lib "eagle-import") (part "BULB"))
    )
    (comp (ref "I12")
      (value "CM2309")
      (footprint "eagle-import:BULB")
      (libsource (lib "eagle-import") (part "BULB"))
    )
    (comp (ref "Q1")
      (value "2N3009B")
      (footprint "eagle-import:TO39")
      (libsource (lib "eagle-import") (part "2N3019"))
    )
    (comp (ref "Q2")
      (value "2N3009B")
      (footprint "eagle-import:TO39")
      (libsource (lib "eagle-import") (part "2N3019"))
    )
    (comp (ref "Q3")
      (value "2N3009B")
      (footprint "eagle-import:TO39")
      (libsource (lib "eagle-import") (part "2N3019"))
    )
    (comp (ref "Q4")
      (value "2N3009B")
      (footprint "eagle-import:TO39")
      (libsource (lib "eagle-import") (part "2N3019"))
    )
    (comp (ref "Q5")
      (value "2N3009B")
      (footprint "eagle-import:TO39")
      (libsource (lib "eagle-import") (part "2N3019"))
    )
    (comp (ref "Q6")
      (value "2N3009B")
      (footprint "eagle-import:TO39")
      (libsource (lib "eagle-import") (part "2N3019"))
    )
    (comp (ref "Q7")
      (value "2N3009B")
      (footprint "eagle-import:TO39")
      (libsource (lib "eagle-import") (part "2N3019"))
    )
    (comp (ref "Q8")
      (value "2N3009B")
      (footprint "eagle-import:TO39")
      (libsource (lib "eagle-import") (part "2N3019"))
    )
    (comp (ref "Q9")
      (value "2N3009B")
      (footprint "eagle-import:TO39")
      (libsource (lib "eagle-import") (part "2N3019"))
    )
    (comp (ref "Q10")
      (value "2N3009B")
      (footprint "eagle-import:TO39")
      (libsource (lib "eagle-import") (part "2N3019"))
    )
    (comp (ref "Q11")
      (value "2N3009B")
      (footprint "eagle-import:TO39")
      (libsource (lib "eagle-import") (part "2N3019"))
    )
    (comp (ref "Q12")
      (value "2N3009B")
      (footprint "eagle-import:TO39")
      (libsource (lib "eagle-import") (part "2N3019"))
    )
    (comp (ref "R1")
      (value "15K")
      (footprint "eagle-import:0207_10")
      (libsource (lib "eagle-import") (part "R-US_0207/10"))
    )
    (comp (ref "R2")
      (value "15K")
      (footprint "eagle-import:0207_10")
      (libsource (lib "eagle-import") (part "R-US_0207/10"))
    )
    (comp (ref "R3")
      (value "15K")
      (footprint "eagle-import:0207_10")
      (libsource (lib "eagle-import") (part "R-US_0207/10"))
    )
    (comp (ref "R4")
      (value "15K")
      (footprint "eagle-import:0207_10")
      (libsource (lib "eagle-import") (part "R-US_0207/10"))
    )
    (comp (ref "R5")
      (value "15K")
      (footprint "eagle-import:0207_10")
      (libsource (lib "eagle-import") (part "R-US_0207/10"))
    )
    (comp (ref "R6")
      (value "15K")
      (footprint "eagle-import:0207_10")
      (libsource (lib "eagle-import") (part "R-US_0207/10"))
    )
    (comp (ref "R7")
      (value "15K")
      (footprint "eagle-import:0207_10")
      (libsource (lib "eagle-import") (part "R-US_0207/10"))
    )
    (comp (ref "R8")
      (value "15K")
      (footprint "eagle-import:0207_10")
      (libsource (lib "eagle-import") (part "R-US_0207/10"))
    )
    (comp (ref "R9")
      (value "15K")
      (footprint "eagle-import:0207_10")
      (libsource (lib "eagle-import") (part "R-US_0207/10"))
    )
    (comp (ref "R10")
      (value "15K")
      (footprint "eagle-import:0207_10")
      (libsource (lib "eagle-import") (part "R-US_0207/10"))
    )
    (comp (ref "R11")
      (value "15K")
      (footprint "eagle-import:0207_10")
      (libsource (lib "eagle-import") (part "R-US_0207/10"))
    )
    (comp (ref "R12")
      (value "15K")
      (footprint "eagle-import:0207_10")
      (libsource (lib "eagle-import") (part "R-US_0207/10"))
    )
    (comp (ref "R13")
      (value "33K")
      (footprint "eagle-import:0207_10")
      (libsource (lib "eagle-import") (part "R-US_0207/10"))
    )
    (comp (ref "R14")
      (value "33K")
      (footprint "eagle-import:0207_10")
      (libsource (lib "eagle-import") (part "R-US_0207/10"))
    )
    (comp (ref "R15")
      (value "33K")
      (footprint "eagle-import:0207_10")
      (libsource (lib "eagle-import") (part "R-US_0207/10"))
    )
    (comp (ref "R16")
      (value "33K")
      (footprint "eagle-import:0207_10")
      (libsource (lib "eagle-import") (part "R-US_0207/10"))
    )
    (comp (ref "R17")
      (value "33K")
      (footprint "eagle-import:0207_10")
      (libsource (lib "eagle-import") (part "R-US_0207/10"))
    )
    (comp (ref "R18")
      (value "33K")
      (footprint "eagle-import:0207_10")
      (libsource (lib "eagle-import") (part "R-US_0207/10"))
    )
    (comp (ref "R19")
      (value "33K")
      (footprint "eagle-import:0207_10")
      (libsource (lib "eagle-import") (part "R-US_0207/10"))
    )
    (comp (ref "R20")
      (value "33K")
      (footprint "eagle-import:0207_10")
      (libsource (lib "eagle-import") (part "R-US_0207/10"))
    )
    (comp (ref "R21")
      (value "33K")
      (footprint "eagle-import:0207_10")
      (libsource (lib "eagle-import") (part "R-US_0207/10"))
    )
    (comp (ref "R22")
      (value "33K")
      (footprint "eagle-import:0207_10")
      (libsource (lib "eagle-import") (part "R-US_0207/10"))
    )
    (comp (ref "R23")
      (value "33K")
      (footprint "eagle-import:0207_10")
      (libsource (lib "eagle-import") (part "R-US_0207/10"))
    )
    (comp (ref "R24")
      (value "33K")
      (footprint "eagle-import:0207_10")
      (libsource (lib "eagle-import") (part "R-US_0207/10"))
    )
    (comp (ref "R25")
      (value "390")
      (footprint "eagle-import:0207_10")
      (libsource (lib "eagle-import") (part "R-US_0207/10"))
    )
    (comp (ref "R26")
      (value "33K")
      (footprint "eagle-import:0207_10")
      (libsource (lib "eagle-import") (part "R-US_0207/10"))
    )
    (comp (ref "R27")
      (value "33K")
      (footprint "eagle-import:0207_10")
      (libsource (lib "eagle-import") (part "R-US_0207/10"))
    )
    (comp (ref "R28")
      (value "390")
      (footprint "eagle-import:0207_10")
      (libsource (lib "eagle-import") (part "R-US_0207/10"))
    )
    (comp (ref "R29")
      (value "33K")
      (footprint "eagle-import:0207_10")
      (libsource (lib "eagle-import") (part "R-US_0207/10"))
    )
    (comp (ref "R30")
      (value "33K")
      (footprint "eagle-import:0207_10")
      (libsource (lib "eagle-import") (part "R-US_0207/10"))
    )
    (comp (ref "R31")
      (value "390")
      (footprint "eagle-import:0207_10")
      (libsource (lib "eagle-import") (part "R-US_0207/10"))
    )
    (comp (ref "R32")
      (value "33K")
      (footprint "eagle-import:0207_10")
      (libsource (lib "eagle-import") (part "R-US_0207/10"))
    )
    (comp (ref "R33")
      (value "33K")
      (footprint "eagle-import:0207_10")
      (libsource (lib "eagle-import") (part "R-US_0207/10"))
    )
    (comp (ref "R34")
      (value "390")
      (footprint "eagle-import:0207_10")
      (libsource (lib "eagle-import") (part "R-US_0207/10"))
    )
    (comp (ref "R35")
      (value "33K")
      (footprint "eagle-import:0207_10")
      (libsource (lib "eagle-import") (part "R-US_0207/10"))
    )
    (comp (ref "R36")
      (value "33K")
      (footprint "eagle-import:0207_10")
      (libsource (lib "eagle-import") (part "R-US_0207/10"))
    )
    (comp (ref "R37")
      (value "390")
      (footprint "eagle-import:0207_10")
      (libsource (lib "eagle-import") (part "R-US_0207/10"))
    )
    (comp (ref "R38")
      (value "33K")
      (footprint "eagle-import:0207_10")
      (libsource (lib "eagle-import") (part "R-US_0207/10"))
    )
    (comp (ref "R39")
      (value "33K")
      (footprint "eagle-import:0207_10")
      (libsource (lib "eagle-import") (part "R-US_0207/10"))
    )
    (comp (ref "R40")
      (value "390")
      (footprint "eagle-import:0207_10")
      (libsource (lib "eagle-import") (part "R-US_0207/10"))
    )
    (comp (ref "R41")
      (value "33K")
      (footprint "eagle-import:0207_10")
      (libsource (lib "eagle-import") (part "R-US_0207/10"))
    )
    (comp (ref "R42")
      (value "33K")
      (footprint "eagle-import:0207_10")
      (libsource (lib "eagle-import") (part "R-US_0207/10"))
    )
    (comp (ref "R43")
      (value "390")
      (footprint "eagle-import:0207_10")
      (libsource (lib "eagle-import") (part "R-US_0207/10"))
    )
    (comp (ref "R44")
      (value "33K")
      (footprint "eagle-import:0207_10")
      (libsource (lib "eagle-import") (part "R-US_0207/10"))
    )
    (comp (ref "R45")
      (value "33K")
      (footprint "eagle-import:0207_10")
      (libsource (lib "eagle-import") (part "R-US_0207/10"))
    )
    (comp (ref "R46")
      (value "390")
      (footprint "eagle-import:0207_10")
      (libsource (lib "eagle-import") (part "R-US_0207/10"))
    )
    (comp (ref "R47")
      (value "33K")
      (footprint "eagle-import:0207_10")
      (libsource (lib "eagle-import") (part "R-US_0207/10"))
    )
    (comp (ref "R48")
      (value "33K")
      (footprint "eagle-import:0207_10")
      (libsource (lib "eagle-import") (part "R-US_0207/10"))
    )
    (comp (ref "R49")
      (value "390")
      (footprint "eagle-import:0207_10")
      (libsource (lib "eagle-import") (part "R-US_0207/10"))
    )
    (comp (ref "R50")
      (value "33K")
      (footprint "eagle-import:0207_10")
      (libsource (lib "eagle-import") (part "R-US_0207/10"))
    )
    (comp (ref "R51")
      (value "33K")
      (footprint "eagle-import:0207_10")
      (libsource (lib "eagle-import") (part "R-US_0207/10"))
    )
    (comp (ref "R52")
      (value "390")
      (footprint "eagle-import:0207_10")
      (libsource (lib "eagle-import") (part "R-US_0207/10"))
    )
    (comp (ref "R53")
      (value "33K")
      (footprint "eagle-import:0207_10")
      (libsource (lib "eagle-import") (part "R-US_0207/10"))
    )
    (comp (ref "R54")
      (value "33K")
      (footprint "eagle-import:0207_10")
      (libsource (lib "eagle-import") (part "R-US_0207/10"))
    )
    (comp (ref "R55")
      (value "390")
      (footprint "eagle-import:0207_10")
      (libsource (lib "eagle-import") (part "R-US_0207/10"))
    )
    (comp (ref "R56")
      (value "33K")
      (footprint "eagle-import:0207_10")
      (libsource (lib "eagle-import") (part "R-US_0207/10"))
    )
    (comp (ref "R57")
      (value "33K")
      (footprint "eagle-import:0207_10")
      (libsource (lib "eagle-import") (part "R-US_0207/10"))
    )
    (comp (ref "R58")
      (value "390")
      (footprint "eagle-import:0207_10")
      (libsource (lib "eagle-import") (part "R-US_0207/10"))
    )
    (comp (ref "R59")
      (value "33K")
      (footprint "eagle-import:0207_10")
      (libsource (lib "eagle-import") (part "R-US_0207/10"))
    )
    (comp (ref "R60")
      (value "33K")
      (footprint "eagle-import:0207_10")
      (libsource (lib "eagle-import") (part "R-US_0207/10"))
    )
    (comp (ref "R61")
      (value "33K")
      (footprint "eagle-import:0207_10")
      (libsource (lib "eagle-import") (part "R-US_0207/10"))
    )
    (comp (ref "R62")
      (value "33K")
      (footprint "eagle-import:0207_10")
      (libsource (lib "eagle-import") (part "R-US_0207/10"))
    )
    (comp (ref "R63")
      (value "33K")
      (footprint "eagle-import:0207_10")
      (libsource (lib "eagle-import") (part "R-US_0207/10"))
    )
    (comp (ref "R64")
      (value "33K")
      (footprint "eagle-import:0207_10")
      (libsource (lib "eagle-import") (part "R-US_0207/10"))
    )
    (comp (ref "R65")
      (value "33K")
      (footprint "eagle-import:0207_10")
      (libsource (lib "eagle-import") (part "R-US_0207/10"))
    )
    (comp (ref "R66")
      (value "33K")
      (footprint "eagle-import:0207_10")
      (libsource (lib "eagle-import") (part "R-US_0207/10"))
    )
    (comp (ref "R67")
      (value "33K")
      (footprint "eagle-import:0207_10")
      (libsource (lib "eagle-import") (part "R-US_0207/10"))
    )
    (comp (ref "R68")
      (value "33K")
      (footprint "eagle-import:0207_10")
      (libsource (lib "eagle-import") (part "R-US_0207/10"))
    )
    (comp (ref "R69")
      (value "33K")
      (footprint "eagle-import:0207_10")
      (libsource (lib "eagle-import") (part "R-US_0207/10"))
    )
    (comp (ref "R70")
      (value "33K")
      (footprint "eagle-import:0207_10")
      (libsource (lib "eagle-import") (part "R-US_0207/10"))
    )
    (comp (ref "R71")
      (value "33K")
      (footprint "eagle-import:0207_10")
      (libsource (lib "eagle-import") (part "R-US_0207/10"))
    )
    (comp (ref "R72")
      (value "33K")
      (footprint "eagle-import:0207_10")
      (libsource (lib "eagle-import") (part "R-US_0207/10"))
    )
    (comp (ref "R73")
      (value "33K")
      (footprint "eagle-import:0207_10")
      (libsource (lib "eagle-import") (part "R-US_0207/10"))
    )
    (comp (ref "R74")
      (value "33K")
      (footprint "eagle-import:0207_10")
      (libsource (lib "eagle-import") (part "R-US_0207/10"))
    )
    (comp (ref "R75")
      (value "33K")
      (footprint "eagle-import:0207_10")
      (libsource (lib "eagle-import") (part "R-US_0207/10"))
    )
    (comp (ref "R76")
      (value "33K")
      (footprint "eagle-import:0207_10")
      (libsource (lib "eagle-import") (part "R-US_0207/10"))
    )
    (comp (ref "R77")
      (value "33K")
      (footprint "eagle-import:0207_10")
      (libsource (lib "eagle-import") (part "R-US_0207/10"))
    )
    (comp (ref "R78")
      (value "33K")
      (footprint "eagle-import:0207_10")
      (libsource (lib "eagle-import") (part "R-US_0207/10"))
    )
    (comp (ref "R79")
      (value "33K")
      (footprint "eagle-import:0207_10")
      (libsource (lib "eagle-import") (part "R-US_0207/10"))
    )
    (comp (ref "R80")
      (value "33K")
      (footprint "eagle-import:0207_10")
      (libsource (lib "eagle-import") (part "R-US_0207/10"))
    )
    (comp (ref "R81")
      (value "33K")
      (footprint "eagle-import:0207_10")
      (libsource (lib "eagle-import") (part "R-US_0207/10"))
    )
    (comp (ref "R82")
      (value "33K")
      (footprint "eagle-import:0207_10")
      (libsource (lib "eagle-import") (part "R-US_0207/10"))
    )
    (comp (ref "R83")
      (value "33K")
      (footprint "eagle-import:0207_10")
      (libsource (lib "eagle-import") (part "R-US_0207/10"))
    )
    (comp (ref "R84")
      (value "33K")
      (footprint "eagle-import:0207_10")
      (libsource (lib "eagle-import") (part "R-US_0207/10"))
    )
    (comp (ref "C13")
      (value "39uF")
      (footprint "eagle-import:E12-8")
      (libsource (lib "eagle-import") (part "CPOL-USE20-8AXIAL"))
    )
    (comp (ref "C14")
      (value "56pF")
      (footprint "eagle-import:C050-025X075")
      (libsource (lib "eagle-import") (part "C-US050-025X075"))
    )
    (comp (ref "C15")
      (value "330pF")
      (footprint "eagle-import:C050-025X075")
      (libsource (lib "eagle-import") (part "C-US050-025X075"))
    )
    (comp (ref "C21")
      (value ".01uF")
      (footprint "eagle-import:C050-025X075")
      (libsource (lib "eagle-import") (part "C-US050-025X075"))
    )
    (comp (ref "D106")
      (value "D662")
      (footprint "eagle-import:DO35-10")
      (libsource (lib "eagle-import") (part "1N4148DO35-10"))
    )
    (comp (ref "D107")
      (value "D662")
      (footprint "eagle-import:DO35-10")
      (libsource (lib "eagle-import") (part "1N4148DO35-10"))
    )
    (comp (ref "D108")
      (value "D662")
      (footprint "eagle-import:DO35-10")
      (libsource (lib "eagle-import") (part "1N4148DO35-10"))
    )
    (comp (ref "D109")
      (value "D664")
      (footprint "eagle-import:DO35-10")
      (libsource (lib "eagle-import") (part "1N4148DO35-10"))
    )
    (comp (ref "D110")
      (value "D662")
      (footprint "eagle-import:DO35-10")
      (libsource (lib "eagle-import") (part "1N4148DO35-10"))
    )
    (comp (ref "D111")
      (value "D662")
      (footprint "eagle-import:DO35-10")
      (libsource (lib "eagle-import") (part "1N4148DO35-10"))
    )
    (comp (ref "D112")
      (value "D662")
      (footprint "eagle-import:DO35-10")
      (libsource (lib "eagle-import") (part "1N4148DO35-10"))
    )
    (comp (ref "D113")
      (value "D662")
      (footprint "eagle-import:DO35-10")
      (libsource (lib "eagle-import") (part "1N4148DO35-10"))
    )
    (comp (ref "D114")
      (value "D662")
      (footprint "eagle-import:DO35-10")
      (libsource (lib "eagle-import") (part "1N4148DO35-10"))
    )
    (comp (ref "D115")
      (value "D662")
      (footprint "eagle-import:DO35-10")
      (libsource (lib "eagle-import") (part "1N4148DO35-10"))
    )
    (comp (ref "D116")
      (value "D664")
      (footprint "eagle-import:DO35-10")
      (libsource (lib "eagle-import") (part "1N4148DO35-10"))
    )
    (comp (ref "D117")
      (value "D664")
      (footprint "eagle-import:DO35-10")
      (libsource (lib "eagle-import") (part "1N4148DO35-10"))
    )
    (comp (ref "D118")
      (value "D664")
      (footprint "eagle-import:DO35-10")
      (libsource (lib "eagle-import") (part "1N4148DO35-10"))
    )
    (comp (ref "D119")
      (value "D664")
      (footprint "eagle-import:DO35-10")
      (libsource (lib "eagle-import") (part "1N4148DO35-10"))
    )
    (comp (ref "D120")
      (value "D668")
      (footprint "eagle-import:DO35-10")
      (libsource (lib "eagle-import") (part "1N4148DO35-10"))
    )
    (comp (ref "D121")
      (value "D664")
      (footprint "eagle-import:DO35-10")
      (libsource (lib "eagle-import") (part "1N4148DO35-10"))
    )
    (comp (ref "D122")
      (value "D664")
      (footprint "eagle-import:DO35-10")
      (libsource (lib "eagle-import") (part "1N4148DO35-10"))
    )
    (comp (ref "D123")
      (value "D662")
      (footprint "eagle-import:DO35-10")
      (libsource (lib "eagle-import") (part "1N4148DO35-10"))
    )
    (comp (ref "D124")
      (value "D662")
      (footprint "eagle-import:DO35-10")
      (libsource (lib "eagle-import") (part "1N4148DO35-10"))
    )
    (comp (ref "D125")
      (value "D662")
      (footprint "eagle-import:DO35-10")
      (libsource (lib "eagle-import") (part "1N4148DO35-10"))
    )
    (comp (ref "D126")
      (value "D662")
      (footprint "eagle-import:DO35-10")
      (libsource (lib "eagle-import") (part "1N4148DO35-10"))
    )
    (comp (ref "D127")
      (value "D664")
      (footprint "eagle-import:DO35-10")
      (libsource (lib "eagle-import") (part "1N4148DO35-10"))
    )
    (comp (ref "D128")
      (value "D664")
      (footprint "eagle-import:DO35-10")
      (libsource (lib "eagle-import") (part "1N4148DO35-10"))
    )
    (comp (ref "D129")
      (value "D662")
      (footprint "eagle-import:DO35-10")
      (libsource (lib "eagle-import") (part "1N4148DO35-10"))
    )
    (comp (ref "E3")
      (value "7400N")
      (footprint "eagle-import:DIL14")
      (libsource (lib "eagle-import") (part "7400N"))
    )
    (comp (ref "E7")
      (value "N8881N")
      (footprint "eagle-import:DIL14")
      (libsource (lib "eagle-import") (part "N8881N"))
    )
    (comp (ref "E9")
      (value "7404N")
      (footprint "eagle-import:DIL14")
      (libsource (lib "eagle-import") (part "7404N"))
    )
    (comp (ref "E16")
      (value "SP380N")
      (footprint "eagle-import:DIL14")
      (libsource (lib "eagle-import") (part "SP380N"))
    )
    (comp (ref "E19")
      (value "7416N")
      (footprint "eagle-import:DIL14")
      (libsource (lib "eagle-import") (part "7416N"))
    )
    (comp (ref "E20")
      (value "SP380N")
      (footprint "eagle-import:DIL14")
      (libsource (lib "eagle-import") (part "SP380N"))
    )
    (comp (ref "E23")
      (value "7416N")
      (footprint "eagle-import:DIL14")
      (libsource (lib "eagle-import") (part "7416N"))
    )
    (comp (ref "E24")
      (value "SP380N")
      (footprint "eagle-import:DIL14")
      (libsource (lib "eagle-import") (part "SP380N"))
    )
    (comp (ref "E27")
      (value "7416N")
      (footprint "eagle-import:DIL14")
      (libsource (lib "eagle-import") (part "7416N"))
    )
    (comp (ref "E28")
      (value "SP380N")
      (footprint "eagle-import:DIL14")
      (libsource (lib "eagle-import") (part "SP380N"))
    )
    (comp (ref "I13")
      (value "CM2309")
      (footprint "eagle-import:BULB")
      (libsource (lib "eagle-import") (part "BULB"))
    )
    (comp (ref "I14")
      (value "CM2309")
      (footprint "eagle-import:BULB")
      (libsource (lib "eagle-import") (part "BULB"))
    )
    (comp (ref "I15")
      (value "CM2309")
      (footprint "eagle-import:BULB")
      (libsource (lib "eagle-import") (part "BULB"))
    )
    (comp (ref "I16")
      (value "CM2309")
      (footprint "eagle-import:BULB")
      (libsource (lib "eagle-import") (part "BULB"))
    )
    (comp (ref "I17")
      (value "CM2309")
      (footprint "eagle-import:BULB")
      (libsource (lib "eagle-import") (part "BULB"))
    )
    (comp (ref "I18")
      (value "CM2309")
      (footprint "eagle-import:BULB")
      (libsource (lib "eagle-import") (part "BULB"))
    )
    (comp (ref "I19")
      (value "CM2309")
      (footprint "eagle-import:BULB")
      (libsource (lib "eagle-import") (part "BULB"))
    )
    (comp (ref "I20")
      (value "CM2309")
      (footprint "eagle-import:BULB")
      (libsource (lib "eagle-import") (part "BULB"))
    )
    (comp (ref "I21")
      (value "CM2309")
      (footprint "eagle-import:BULB")
      (libsource (lib "eagle-import") (part "BULB"))
    )
    (comp (ref "I22")
      (value "CM2309")
      (footprint "eagle-import:BULB")
      (libsource (lib "eagle-import") (part "BULB"))
    )
    (comp (ref "I23")
      (value "CM2309")
      (footprint "eagle-import:BULB")
      (libsource (lib "eagle-import") (part "BULB"))
    )
    (comp (ref "I24")
      (value "CM2309")
      (footprint "eagle-import:BULB")
      (libsource (lib "eagle-import") (part "BULB"))
    )
    (comp (ref "I25")
      (value "CM2309")
      (footprint "eagle-import:BULB")
      (libsource (lib "eagle-import") (part "BULB"))
    )
    (comp (ref "I26")
      (value "CM2309")
      (footprint "eagle-import:BULB")
      (libsource (lib "eagle-import") (part "BULB"))
    )
    (comp (ref "I27")
      (value "CM2309")
      (footprint "eagle-import:BULB")
      (libsource (lib "eagle-import") (part "BULB"))
    )
    (comp (ref "I28")
      (value "CM2309")
      (footprint "eagle-import:BULB")
      (libsource (lib "eagle-import") (part "BULB"))
    )
    (comp (ref "Q13")
      (value "MPS6534")
      (footprint "eagle-import:TO39")
      (libsource (lib "eagle-import") (part "2N3637"))
    )
    (comp (ref "Q14")
      (value "MPS6534")
      (footprint "eagle-import:TO39")
      (libsource (lib "eagle-import") (part "2N3637"))
    )
    (comp (ref "Q15")
      (value "MPS6534")
      (footprint "eagle-import:TO39")
      (libsource (lib "eagle-import") (part "2N3637"))
    )
    (comp (ref "Q16")
      (value "MPS6534")
      (footprint "eagle-import:TO39")
      (libsource (lib "eagle-import") (part "2N3637"))
    )
    (comp (ref "Q17")
      (value "2N3009B")
      (footprint "eagle-import:TO39")
      (libsource (lib "eagle-import") (part "2N3019"))
    )
    (comp (ref "Q18")
      (value "2N3009B")
      (footprint "eagle-import:TO39")
      (libsource (lib "eagle-import") (part "2N3019"))
    )
    (comp (ref "Q19")
      (value "2N3009B")
      (footprint "eagle-import:TO39")
      (libsource (lib "eagle-import") (part "2N3019"))
    )
    (comp (ref "R127")
      (value "390")
      (footprint "eagle-import:0207_10")
      (libsource (lib "eagle-import") (part "R-US_0207/10"))
    )
    (comp (ref "R128")
      (value "390")
      (footprint "eagle-import:0207_10")
      (libsource (lib "eagle-import") (part "R-US_0207/10"))
    )
    (comp (ref "R129")
      (value "390")
      (footprint "eagle-import:0207_10")
      (libsource (lib "eagle-import") (part "R-US_0207/10"))
    )
    (comp (ref "R130")
      (value "390")
      (footprint "eagle-import:0207_10")
      (libsource (lib "eagle-import") (part "R-US_0207/10"))
    )
    (comp (ref "R131")
      (value "390")
      (footprint "eagle-import:0207_10")
      (libsource (lib "eagle-import") (part "R-US_0207/10"))
    )
    (comp (ref "R132")
      (value "390")
      (footprint "eagle-import:0207_10")
      (libsource (lib "eagle-import") (part "R-US_0207/10"))
    )
    (comp (ref "R133")
      (value "390")
      (footprint "eagle-import:0207_10")
      (libsource (lib "eagle-import") (part "R-US_0207/10"))
    )
    (comp (ref "R134")
      (value "390")
      (footprint "eagle-import:0207_10")
      (libsource (lib "eagle-import") (part "R-US_0207/10"))
    )
    (comp (ref "R135")
      (value "390")
      (footprint "eagle-import:0207_10")
      (libsource (lib "eagle-import") (part "R-US_0207/10"))
    )
    (comp (ref "R136")
      (value "390")
      (footprint "eagle-import:0207_10")
      (libsource (lib "eagle-import") (part "R-US_0207/10"))
    )
    (comp (ref "R137")
      (value "390")
      (footprint "eagle-import:0207_10")
      (libsource (lib "eagle-import") (part "R-US_0207/10"))
    )
    (comp (ref "R138")
      (value "390")
      (footprint "eagle-import:0207_10")
      (libsource (lib "eagle-import") (part "R-US_0207/10"))
    )
    (comp (ref "R139")
      (value "390")
      (footprint "eagle-import:0207_10")
      (libsource (lib "eagle-import") (part "R-US_0207/10"))
    )
    (comp (ref "R140")
      (value "390")
      (footprint "eagle-import:0207_10")
      (libsource (lib "eagle-import") (part "R-US_0207/10"))
    )
    (comp (ref "R141")
      (value "390")
      (footprint "eagle-import:0207_10")
      (libsource (lib "eagle-import") (part "R-US_0207/10"))
    )
    (comp (ref "R142")
      (value "3K")
      (footprint "eagle-import:0207_10")
      (libsource (lib "eagle-import") (part "R-US_0207/10"))
    )
    (comp (ref "R143")
      (value "3K")
      (footprint "eagle-import:0207_10")
      (libsource (lib "eagle-import") (part "R-US_0207/10"))
    )
    (comp (ref "R144")
      (value "3K")
      (footprint "eagle-import:0207_10")
      (libsource (lib "eagle-import") (part "R-US_0207/10"))
    )
    (comp (ref "R145")
      (value "3K")
      (footprint "eagle-import:0207_10")
      (libsource (lib "eagle-import") (part "R-US_0207/10"))
    )
    (comp (ref "R146")
      (value "3K")
      (footprint "eagle-import:0207_10")
      (libsource (lib "eagle-import") (part "R-US_0207/10"))
    )
    (comp (ref "R147")
      (value "3K")
      (footprint "eagle-import:0207_10")
      (libsource (lib "eagle-import") (part "R-US_0207/10"))
    )
    (comp (ref "R148")
      (value "4.7K")
      (footprint "eagle-import:0207_10")
      (libsource (lib "eagle-import") (part "R-US_0207/10"))
    )
    (comp (ref "R149")
      (value "1K")
      (footprint "eagle-import:0207_10")
      (libsource (lib "eagle-import") (part "R-US_0207/10"))
    )
    (comp (ref "R150")
      (value "1K")
      (footprint "eagle-import:0207_10")
      (libsource (lib "eagle-import") (part "R-US_0207/10"))
    )
    (comp (ref "R151")
      (value "3K")
      (footprint "eagle-import:0207_10")
      (libsource (lib "eagle-import") (part "R-US_0207/10"))
    )
    (comp (ref "R152")
      (value "3K")
      (footprint "eagle-import:0207_10")
      (libsource (lib "eagle-import") (part "R-US_0207/10"))
    )
    (comp (ref "R153")
      (value "1000")
      (footprint "eagle-import:0207_10")
      (libsource (lib "eagle-import") (part "R-US_0207/10"))
    )
    (comp (ref "R154")
      (value "100")
      (footprint "eagle-import:0207_10")
      (libsource (lib "eagle-import") (part "R-US_0207/10"))
    )
    (comp (ref "R155")
      (value "1000")
      (footprint "eagle-import:0207_10")
      (libsource (lib "eagle-import") (part "R-US_0207/10"))
    )
    (comp (ref "R156")
      (value "150")
      (footprint "eagle-import:0207_10")
      (libsource (lib "eagle-import") (part "R-US_0207/10"))
    )
    (comp (ref "R157")
      (value "3000")
      (footprint "eagle-import:0207_10")
      (libsource (lib "eagle-import") (part "R-US_0207/10"))
    )
    (comp (ref "R158")
      (value "15K")
      (footprint "eagle-import:0207_10")
      (libsource (lib "eagle-import") (part "R-US_0207/10"))
    )
    (comp (ref "R159")
      (value "15K")
      (footprint "eagle-import:0207_10")
      (libsource (lib "eagle-import") (part "R-US_0207/10"))
    )
    (comp (ref "R160")
      (value "15K")
      (footprint "eagle-import:0207_10")
      (libsource (lib "eagle-import") (part "R-US_0207/10"))
    )
    (comp (ref "R161")
      (value "1800")
      (footprint "eagle-import:0207_10")
      (libsource (lib "eagle-import") (part "R-US_0207/10"))
    )
    (comp (ref "R162")
      (value "470")
      (footprint "eagle-import:0207_10")
      (libsource (lib "eagle-import") (part "R-US_0207/10"))
    )
    (comp (ref "R163")
      (value "27")
      (footprint "eagle-import:0207_10")
      (libsource (lib "eagle-import") (part "R-US_0207/10"))
    )
    (comp (ref "R164")
      (value "470")
      (footprint "eagle-import:0207_10")
      (libsource (lib "eagle-import") (part "R-US_0207/10"))
    )
    (comp (ref "R165")
      (value "27")
      (footprint "eagle-import:0207_10")
      (libsource (lib "eagle-import") (part "R-US_0207/10"))
    )
    (comp (ref "R166")
      (value "1K")
      (footprint "eagle-import:0207_10")
      (libsource (lib "eagle-import") (part "R-US_0207/10"))
    )
    (comp (ref "R167")
      (value "470")
      (footprint "eagle-import:0207_10")
      (libsource (lib "eagle-import") (part "R-US_0207/10"))
    )
    (comp (ref "R168")
      (value "1K")
      (footprint "eagle-import:0207_10")
      (libsource (lib "eagle-import") (part "R-US_0207/10"))
    )
    (comp (ref "R169")
      (value "100")
      (footprint "eagle-import:0207_10")
      (libsource (lib "eagle-import") (part "R-US_0207/10"))
    )
    (comp (ref "R170")
      (value "470")
      (footprint "eagle-import:0207_10")
      (libsource (lib "eagle-import") (part "R-US_0207/10"))
    )
    (comp (ref "R171")
      (value "4.7K")
      (footprint "eagle-import:0207_10")
      (libsource (lib "eagle-import") (part "R-US_0207/10"))
    )
    (comp (ref "R172")
      (value "27")
      (footprint "eagle-import:0207_10")
      (libsource (lib "eagle-import") (part "R-US_0207/10"))
    )
    (comp (ref "R173")
      (value "4.7K")
      (footprint "eagle-import:0207_10")
      (libsource (lib "eagle-import") (part "R-US_0207/10"))
    )
    (comp (ref "R174")
      (value "27")
      (footprint "eagle-import:0207_10")
      (libsource (lib "eagle-import") (part "R-US_0207/10"))
    )
    (comp (ref "R175")
      (value "470")
      (footprint "eagle-import:0204_7")
      (libsource (lib "eagle-import") (part "R-US_0204/7"))
    )
    (comp (ref "S1")
      (value "ROTARY8E")
      (footprint "eagle-import:ROTARY-8E")
      (libsource (lib "eagle-import") (part "ROTARY8E"))
    )
  )
  (nets
    (net (code "1") (name "+0.75V") (class "Default")
      (node (ref "D120") (pin "C") (pinfunction "C_C") (pintype "passive"))
      (node (ref "D125") (pin "C") (pinfunction "C_C") (pintype "passive"))
      (node (ref "D126") (pin "A") (pinfunction "A_A") (pintype "passive"))
    )
    (net (code "2") (name "+3V3") (class "Default")
      (node (ref "C21") (pin "1") (pinfunction "1_1") (pintype "passive"))
      (node (ref "D117") (pin "C") (pinfunction "C_C") (pintype "passive"))
      (node (ref "D121") (pin "C") (pinfunction "C_C") (pintype "passive"))
      (node (ref "D123") (pin "A") (pinfunction "A_A") (pintype "passive"))
      (node (ref "R170") (pin "1") (pinfunction "1_1") (pintype "passive"))
    )
    (net (code "3") (name "+8V") (class "Default")
      (node (ref "C16") (pin "+") (pinfunction "+_+") (pintype "passive"))
      (node (ref "I1") (pin "B") (pinfunction "B_B") (pintype "passive"))
      (node (ref "I10") (pin "B") (pinfunction "B_B") (pintype "passive"))
      (node (ref "I11") (pin "B") (pinfunction "B_B") (pintype "passive"))
      (node (ref "I12") (pin "B") (pinfunction "B_B") (pintype "passive"))
      (node (ref "I13") (pin "B") (pinfunction "B_B") (pintype "passive"))
      (node (ref "I14") (pin "B") (pinfunction "B_B") (pintype "passive"))
      (node (ref "I15") (pin "B") (pinfunction "B_B") (pintype "passive"))
      (node (ref "I16") (pin "B") (pinfunction "B_B") (pintype "passive"))
      (node (ref "I17") (pin "B") (pinfunction "B_B") (pintype "passive"))
      (node (ref "I18") (pin "B") (pinfunction "B_B") (pintype "passive"))
      (node (ref "I19") (pin "B") (pinfunction "B_B") (pintype "passive"))
      (node (ref "I2") (pin "B") (pinfunction "B_B") (pintype "passive"))
      (node (ref "I20") (pin "B") (pinfunction "B_B") (pintype "passive"))
      (node (ref "I21") (pin "B") (pinfunction "B_B") (pintype "passive"))
      (node (ref "I22") (pin "B") (pinfunction "B_B") (pintype "passive"))
      (node (ref "I23") (pin "B") (pinfunction "B_B") (pintype "passive"))
      (node (ref "I24") (pin "B") (pinfunction "B_B") (pintype "passive"))
      (node (ref "I25") (pin "B") (pinfunction "B_B") (pintype "passive"))
      (node (ref "I26") (pin "B") (pinfunction "B_B") (pintype "passive"))
      (node (ref "I27") (pin "B") (pinfunction "B_B") (pintype "passive"))
      (node (ref "I3") (pin "B") (pinfunction "B_B") (pintype "passive"))
      (node (ref "I4") (pin "B") (pinfunction "B_B") (pintype "passive"))
      (node (ref "I5") (pin "B") (pinfunction "B_B") (pintype "passive"))
      (node (ref "I6") (pin "B") (pinfunction "B_B") (pintype "passive"))
      (node (ref "I7") (pin "B") (pinfunction "B_B") (pintype "passive"))
      (node (ref "I8") (pin "B") (pinfunction "B_B") (pintype "passive"))
      (node (ref "I9") (pin "B") (pinfunction "B_B") (pintype "passive"))
      (node (ref "YELLOW") (pin "1") (pinfunction "1_1") (pintype "passive"))
    )
    (net (code "4") (name "-15V") (class "Default")
      (node (ref "C17") (pin "-") (pinfunction "-_-") (pintype "passive"))
      (node (ref "C40") (pin "-") (pinfunction "-_-") (pintype "passive"))
      (node (ref "C41") (pin "-") (pinfunction "-_-") (pintype "passive"))
      (node (ref "I28") (pin "A") (pinfunction "A_A") (pintype "passive"))
      (node (ref "R158") (pin "1") (pinfunction "1_1") (pintype "passive"))
      (node (ref "S1") (pin "S") (pinfunction "S_S") (pintype "passive"))
      (node (ref "S11") (pin "L2") (pinfunction "A2_L2") (pintype "bidirectional"))
      (node (ref "S11") (pin "R2") (pinfunction "B2_R2") (pintype "bidirectional"))
      (node (ref "S12") (pin "L2") (pinfunction "A2_L2") (pintype "bidirectional"))
      (node (ref "S12") (pin "R2") (pinfunction "B2_R2") (pintype "bidirectional"))
      (node (ref "S13") (pin "L2") (pinfunction "A2_L2") (pintype "bidirectional"))
      (node (ref "S13") (pin "R2") (pinfunction "B2_R2") (pintype "bidirectional"))
      (node (ref "S14") (pin "L2") (pinfunction "A2_L2") (pintype "bidirectional"))
      (node (ref "S14") (pin "R2") (pinfunction "B2_R2") (pintype "bidirectional"))
      (node (ref "S15") (pin "L2") (pinfunction "A2_L2") (pintype "bidirectional"))
      (node (ref "S15") (pin "R2") (pinfunction "B2_R2") (pintype "bidirectional"))
      (node (ref "S16") (pin "L2") (pinfunction "A2_L2") (pintype "bidirectional"))
      (node (ref "S16") (pin "R2") (pinfunction "B2_R2") (pintype "bidirectional"))
      (node (ref "S17") (pin "L2") (pinfunction "A2_L2") (pintype "bidirectional"))
      (node (ref "S17") (pin "R2") (pinfunction "B2_R2") (pintype "bidirectional"))
      (node (ref "S18") (pin "L2") (pinfunction "A2_L2") (pintype "bidirectional"))
      (node (ref "S18") (pin "R2") (pinfunction "B2_R2") (pintype "bidirectional"))
      (node (ref "S19") (pin "L2") (pinfunction "A2_L2") (pintype "bidirectional"))
      (node (ref "S19") (pin "R2") (pinfunction "B2_R2") (pintype "bidirectional"))
      (node (ref "S20") (pin "L2") (pinfunction "A2_L2") (pintype "bidirectional"))
      (node (ref "S20") (pin "R2") (pinfunction "B2_R2") (pintype "bidirectional"))
      (node (ref "S21") (pin "L2") (pinfunction "A2_L2") (pintype "bidirectional"))
      (node (ref "S21") (pin "R2") (pinfunction "B2_R2") (pintype "bidirectional"))
      (node (ref "S22") (pin "L2") (pinfunction "A2_L2") (pintype "bidirectional"))
      (node (ref "S22") (pin "R2") (pinfunction "B2_R2") (pintype "bidirectional"))
      (node (ref "U$2") (pin "BB2") (pinfunction "1_BB2") (pintype "bidirectional"))
      (node (ref "U$2") (pin "CB2") (pinfunction "1_CB2") (pintype "bidirectional"))
      (node (ref "U$2") (pin "DB2") (pinfunction "1_DB2") (pintype "bidirectional"))
    )
    (net (code "5") (name "AC_EN") (class "Default")
      (node (ref "D107") (pin "C") (pinfunction "C_C") (pintype "passive"))
      (node (ref "D111") (pin "C") (pinfunction "C_C") (pintype "passive"))
      (node (ref "D112") (pin "C") (pinfunction "C_C") (pintype "passive"))
      (node (ref "R173") (pin "1") (pinfunction "1_1") (pintype "passive"))
      (node (ref "S1") (pin "4") (pinfunction "4_4") (pintype "passive"))
    )
    (net (code "6") (name "BK_DATA_CONT") (class "Default")
      (node (ref "D80") (pin "A") (pinfunction "A_A") (pintype "passive"))
      (node (ref "E4") (pin "1") (pinfunction "O_1") (pintype "open_collector"))
      (node (ref "U$2") (pin "BK2") (pinfunction "1_BK2") (pintype "bidirectional"))
    )
    (net (code "7") (name "BREAK_C") (class "Default")
      (node (ref "D84") (pin "A") (pinfunction "A_A") (pintype "passive"))
      (node (ref "U$2") (pin "BL2") (pinfunction "1_BL2") (pintype "bidirectional"))
    )
    (net (code "8") (name "BRK_INP") (class "Default")
      (node (ref "D83") (pin "A") (pinfunction "A_A") (pintype "passive"))
      (node (ref "U$2") (pin "BE2") (pinfunction "1_BE2") (pintype "bidirectional"))
    )
    (net (code "9") (name "BUS_EN") (class "Default")
      (node (ref "D113") (pin "C") (pinfunction "C_C") (pintype "passive"))
      (node (ref "D129") (pin "C") (pinfunction "C_C") (pintype "passive"))
      (node (ref "R145") (pin "1") (pinfunction "1_1") (pintype "passive"))
      (node (ref "S1") (pin "1") (pinfunction "1_1") (pintype "passive"))
    )
    (net (code "10") (name "CLR") (class "Default")
      (node (ref "D86") (pin "C") (pinfunction "C_C") (pintype "passive"))
      (node (ref "E10") (pin "5") (pinfunction "I_5") (pintype "input"))
      (node (ref "E14") (pin "13") (pinfunction "I3_13") (pintype "input"))
      (node (ref "R87") (pin "2") (pinfunction "2_2") (pintype "passive"))
    )
    (net (code "11") (name "CONT") (class "Default")
      (node (ref "D87") (pin "C") (pinfunction "C_C") (pintype "passive"))
      (node (ref "E5") (pin "5") (pinfunction "I2_5") (pintype "input"))
      (node (ref "R89") (pin "2") (pinfunction "2_2") (pintype "passive"))
    )
    (net (code "12") (name "CP_START") (class "Default")
      (node (ref "E1") (pin "3") (pinfunction "I1_3") (pintype "input"))
      (node (ref "E12") (pin "8") (pinfunction "O_8") (pintype "output"))
      (node (ref "E4") (pin "3") (pinfunction "I1_3") (pintype "input"))
      (node (ref "E4") (pin "6") (pinfunction "I1_6") (pintype "input"))
      (node (ref "E4") (pin "8") (pinfunction "I0_8") (pintype "input"))
      (node (ref "E5") (pin "13") (pinfunction "I2_13") (pintype "input"))
      (node (ref "E7") (pin "11") (pinfunction "I0_11") (pintype "input"))
      (node (ref "E8") (pin "5") (pinfunction "I2_5") (pintype "input"))
    )
    (net (code "13") (name "D") (class "Default")
      (node (ref "D74") (pin "A") (pinfunction "A_A") (pintype "passive"))
      (node (ref "U$2") (pin "DK2") (pinfunction "1_DK2") (pintype "bidirectional"))
    )
    (net (code "14") (name "DATA00") (class "Default")
      (node (ref "D61") (pin "A") (pinfunction "A_A") (pintype "passive"))
      (node (ref "E25") (pin "1") (pinfunction "O_1") (pintype "open_collector"))
      (node (ref "U$2") (pin "AR1") (pinfunction "1_AR1") (pintype "bidirectional"))
    )
    (net (code "15") (name "DATA01") (class "Default")
      (node (ref "D62") (pin "A") (pinfunction "A_A") (pintype "passive"))
      (node (ref "E25") (pin "4") (pinfunction "O_4") (pintype "open_collector"))
      (node (ref "U$2") (pin "AS1") (pinfunction "1_AS1") (pintype "bidirectional"))
    )
    (net (code "16") (name "DATA02") (class "Default")
      (node (ref "D63") (pin "A") (pinfunction "A_A") (pintype "passive"))
      (node (ref "E25") (pin "10") (pinfunction "O_10") (pintype "open_collector"))
      (node (ref "U$2") (pin "AU1") (pinfunction "1_AU1") (pintype "bidirectional"))
    )
    (net (code "17") (name "DATA03") (class "Default")
      (node (ref "D64") (pin "A") (pinfunction "A_A") (pintype "passive"))
      (node (ref "E25") (pin "13") (pinfunction "O_13") (pintype "open_collector"))
      (node (ref "U$2") (pin "AV1") (pinfunction "1_AV1") (pintype "bidirectional"))
    )
    (net (code "18") (name "DATA04") (class "Default")
      (node (ref "D65") (pin "A") (pinfunction "A_A") (pintype "passive"))
      (node (ref "E21") (pin "1") (pinfunction "O_1") (pintype "open_collector"))
      (node (ref "U$2") (pin "BR1") (pinfunction "1_BR1") (pintype "bidirectional"))
    )
    (net (code "19") (name "DATA05") (class "Default")
      (node (ref "D66") (pin "A") (pinfunction "A_A") (pintype "passive"))
      (node (ref "E21") (pin "4") (pinfunction "O_4") (pintype "open_collector"))
      (node (ref "U$2") (pin "BS1") (pinfunction "1_BS1") (pintype "bidirectional"))
    )
    (net (code "20") (name "DATA06") (class "Default")
      (node (ref "D67") (pin "A") (pinfunction "A_A") (pintype "passive"))
      (node (ref "E21") (pin "10") (pinfunction "O_10") (pintype "open_collector"))
      (node (ref "U$2") (pin "BU1") (pinfunction "1_BU1") (pintype "bidirectional"))
    )
    (net (code "21") (name "DATA07") (class "Default")
      (node (ref "D68") (pin "A") (pinfunction "A_A") (pintype "passive"))
      (node (ref "E21") (pin "13") (pinfunction "O_13") (pintype "open_collector"))
      (node (ref "U$2") (pin "BV1") (pinfunction "1_BV1") (pintype "bidirectional"))
    )
    (net (code "22") (name "DATA08") (class "Default")
      (node (ref "D69") (pin "A") (pinfunction "A_A") (pintype "passive"))
      (node (ref "E17") (pin "1") (pinfunction "O_1") (pintype "open_collector"))
      (node (ref "U$2") (pin "DR1") (pinfunction "1_DR1") (pintype "bidirectional"))
    )
    (net (code "23") (name "DATA09") (class "Default")
      (node (ref "D70") (pin "A") (pinfunction "A_A") (pintype "passive"))
      (node (ref "E17") (pin "4") (pinfunction "O_4") (pintype "open_collector"))
      (node (ref "U$2") (pin "DS1") (pinfunction "1_DS1") (pintype "bidirectional"))
    )
    (net (code "24") (name "DATA10") (class "Default")
      (node (ref "D71") (pin "A") (pinfunction "A_A") (pintype "passive"))
      (node (ref "E17") (pin "13") (pinfunction "O_13") (pintype "open_collector"))
      (node (ref "U$2") (pin "DU1") (pinfunction "1_DU1") (pintype "bidirectional"))
    )
    (net (code "25") (name "DATA11") (class "Default")
      (node (ref "D72") (pin "A") (pinfunction "A_A") (pintype "passive"))
      (node (ref "E17") (pin "10") (pinfunction "O_10") (pintype "open_collector"))
      (node (ref "U$2") (pin "DV1") (pinfunction "1_DV1") (pintype "bidirectional"))
    )
    (net (code "26") (name "DATA_EN") (class "Default")
      (node (ref "D106") (pin "A") (pinfunction "A_A") (pintype "passive"))
      (node (ref "D107") (pin "A") (pinfunction "A_A") (pintype "passive"))
      (node (ref "D108") (pin "A") (pinfunction "A_A") (pintype "passive"))
      (node (ref "D129") (pin "A") (pinfunction "A_A") (pintype "passive"))
      (node (ref "R62") (pin "2") (pinfunction "2_2") (pintype "passive"))
      (node (ref "R64") (pin "2") (pinfunction "2_2") (pintype "passive"))
      (node (ref "R66") (pin "2") (pinfunction "2_2") (pintype "passive"))
      (node (ref "R68") (pin "2") (pinfunction "2_2") (pintype "passive"))
      (node (ref "R70") (pin "2") (pinfunction "2_2") (pintype "passive"))
      (node (ref "R72") (pin "2") (pinfunction "2_2") (pintype "passive"))
      (node (ref "R74") (pin "2") (pinfunction "2_2") (pintype "passive"))
      (node (ref "R76") (pin "2") (pinfunction "2_2") (pintype "passive"))
      (node (ref "R78") (pin "2") (pinfunction "2_2") (pintype "passive"))
      (node (ref "R80") (pin "2") (pinfunction "2_2") (pintype "passive"))
      (node (ref "R82") (pin "2") (pinfunction "2_2") (pintype "passive"))
      (node (ref "R84") (pin "2") (pinfunction "2_2") (pintype "passive"))
    )
    (net (code "27") (name "DEP") (class "Default")
      (node (ref "D90") (pin "C") (pinfunction "C_C") (pintype "passive"))
      (node (ref "E5") (pin "3") (pinfunction "I0_3") (pintype "input"))
      (node (ref "E6") (pin "10") (pinfunction "I1_10") (pintype "input"))
      (node (ref "E8") (pin "11") (pinfunction "I2_11") (pintype "input"))
      (node (ref "E8") (pin "13") (pinfunction "I2_13") (pintype "input"))
      (node (ref "R95") (pin "2") (pinfunction "2_2") (pintype "passive"))
    )
    (net (code "28") (name "DEP+EXAM+CONT") (class "Default")
      (node (ref "E1") (pin "12") (pinfunction "I1_12") (pintype "input"))
      (node (ref "E10") (pin "3") (pinfunction "I_3") (pintype "input"))
      (node (ref "E5") (pin "6") (pinfunction "O_6") (pintype "output"))
    )
    (net (code "29") (name "E") (class "Default")
      (node (ref "D75") (pin "A") (pinfunction "A_A") (pintype "passive"))
      (node (ref "U$2") (pin "DL2") (pinfunction "1_DL2") (pintype "bidirectional"))
    )
    (net (code "30") (name "EMA0") (class "Default")
      (node (ref "E28") (pin "12") (pinfunction "I1_12") (pintype "input"))
      (node (ref "U$2") (pin "AD2") (pinfunction "1_AD2") (pintype "bidirectional"))
    )
    (net (code "31") (name "EMA1") (class "Default")
      (node (ref "E28") (pin "10") (pinfunction "I1_10") (pintype "input"))
      (node (ref "U$2") (pin "AE2") (pinfunction "1_AE2") (pintype "bidirectional"))
    )
    (net (code "32") (name "EMA2") (class "Default")
      (node (ref "E28") (pin "4") (pinfunction "I0_4") (pintype "input"))
      (node (ref "U$2") (pin "AH2") (pinfunction "1_AH2") (pintype "bidirectional"))
    )
    (net (code "33") (name "EXAM") (class "Default")
      (node (ref "D89") (pin "C") (pinfunction "C_C") (pintype "passive"))
      (node (ref "E5") (pin "4") (pinfunction "I1_4") (pintype "input"))
      (node (ref "E6") (pin "1") (pinfunction "I0_1") (pintype "input"))
      (node (ref "E8") (pin "2") (pinfunction "I1_2") (pintype "input"))
      (node (ref "R93") (pin "2") (pinfunction "2_2") (pintype "passive"))
    )
    (net (code "34") (name "EXT_LOAD") (class "Default")
      (node (ref "D91") (pin "C") (pinfunction "C_C") (pintype "passive"))
      (node (ref "E12") (pin "5") (pinfunction "I1_5") (pintype "input"))
      (node (ref "E14") (pin "9") (pinfunction "I0_9") (pintype "input"))
      (node (ref "E8") (pin "1") (pinfunction "I0_1") (pintype "input"))
      (node (ref "E8") (pin "10") (pinfunction "I1_10") (pintype "input"))
      (node (ref "R97") (pin "2") (pinfunction "2_2") (pintype "passive"))
    )
    (net (code "35") (name "FETCH") (class "Default")
      (node (ref "D73") (pin "A") (pinfunction "A_A") (pintype "passive"))
      (node (ref "E2") (pin "4") (pinfunction "I0_4") (pintype "input"))
      (node (ref "U$2") (pin "DJ2") (pinfunction "1_DJ2") (pintype "bidirectional"))
    )
    (net (code "36") (name "FSET") (class "Default")
      (node (ref "E11") (pin "9") (pinfunction "I0_9") (pintype "input"))
      (node (ref "U$2") (pin "DP2") (pinfunction "1_DP2") (pintype "bidirectional"))
    )
    (net (code "37") (name "GND") (class "Default")
      (node (ref "C13") (pin "-") (pinfunction "-_-") (pintype "passive"))
      (node (ref "C16") (pin "-") (pinfunction "-_-") (pintype "passive"))
      (node (ref "C17") (pin "+") (pinfunction "+_+") (pintype "passive"))
      (node (ref "C18") (pin "-") (pinfunction "-_-") (pintype "passive"))
      (node (ref "C19") (pin "-") (pinfunction "-_-") (pintype "passive"))
      (node (ref "C20") (pin "-") (pinfunction "-_-") (pintype "passive"))
      (node (ref "C21") (pin "2") (pinfunction "2_2") (pintype "passive"))
      (node (ref "C22") (pin "2") (pinfunction "2_2") (pintype "passive"))
      (node (ref "C23") (pin "2") (pinfunction "2_2") (pintype "passive"))
      (node (ref "C24") (pin "2") (pinfunction "2_2") (pintype "passive"))
      (node (ref "C25") (pin "2") (pinfunction "2_2") (pintype "passive"))
      (node (ref "C26") (pin "2") (pinfunction "2_2") (pintype "passive"))
      (node (ref "C27") (pin "2") (pinfunction "2_2") (pintype "passive"))
      (node (ref "C28") (pin "2") (pinfunction "2_2") (pintype "passive"))
      (node (ref "C29") (pin "2") (pinfunction "2_2") (pintype "passive"))
      (node (ref "C30") (pin "2") (pinfunction "2_2") (pintype "passive"))
      (node (ref "C31") (pin "2") (pinfunction "2_2") (pintype "passive"))
      (node (ref "C32") (pin "2") (pinfunction "2_2") (pintype "passive"))
      (node (ref "C33") (pin "2") (pinfunction "2_2") (pintype "passive"))
      (node (ref "C34") (pin "2") (pinfunction "2_2") (pintype "passive"))
      (node (ref "C35") (pin "2") (pinfunction "2_2") (pintype "passive"))
      (node (ref "C36") (pin "2") (pinfunction "2_2") (pintype "passive"))
      (node (ref "C37") (pin "2") (pinfunction "2_2") (pintype "passive"))
      (node (ref "C38") (pin "2") (pinfunction "2_2") (pintype "passive"))
      (node (ref "C39") (pin "2") (pinfunction "2_2") (pintype "passive"))
      (node (ref "C40") (pin "+") (pinfunction "+_+") (pintype "passive"))
      (node (ref "C41") (pin "+") (pinfunction "+_+") (pintype "passive"))
      (node (ref "D100") (pin "A") (pinfunction "A_A") (pintype "passive"))
      (node (ref "D101") (pin "A") (pinfunction "A_A") (pintype "passive"))
      (node (ref "D102") (pin "A") (pinfunction "A_A") (pintype "passive"))
      (node (ref "D103") (pin "A") (pinfunction "A_A") (pintype "passive"))
      (node (ref "D104") (pin "A") (pinfunction "A_A") (pintype "passive"))
      (node (ref "D105") (pin "A") (pinfunction "A_A") (pintype "passive"))
      (node (ref "D109") (pin "A") (pinfunction "A_A") (pintype "passive"))
      (node (ref "D114") (pin "A") (pinfunction "A_A") (pintype "passive"))
      (node (ref "D115") (pin "A") (pinfunction "A_A") (pintype "passive"))
      (node (ref "D119") (pin "A") (pinfunction "A_A") (pintype "passive"))
      (node (ref "D126") (pin "C") (pinfunction "C_C") (pintype "passive"))
      (node (ref "D127") (pin "A") (pinfunction "A_A") (pintype "passive"))
      (node (ref "D128") (pin "A") (pinfunction "A_A") (pintype "passive"))
      (node (ref "D85") (pin "A") (pinfunction "A_A") (pintype "passive"))
      (node (ref "D86") (pin "A") (pinfunction "A_A") (pintype "passive"))
      (node (ref "D87") (pin "A") (pinfunction "A_A") (pintype "passive"))
      (node (ref "D88") (pin "A") (pinfunction "A_A") (pintype "passive"))
      (node (ref "D89") (pin "A") (pinfunction "A_A") (pintype "passive"))
      (node (ref "D90") (pin "A") (pinfunction "A_A") (pintype "passive"))
      (node (ref "D91") (pin "A") (pinfunction "A_A") (pintype "passive"))
      (node (ref "D92") (pin "A") (pinfunction "A_A") (pintype "passive"))
      (node (ref "D93") (pin "A") (pinfunction "A_A") (pintype "passive"))
      (node (ref "D94") (pin "A") (pinfunction "A_A") (pintype "passive"))
      (node (ref "D95") (pin "A") (pinfunction "A_A") (pintype "passive"))
      (node (ref "D96") (pin "A") (pinfunction "A_A") (pintype "passive"))
      (node (ref "D97") (pin "A") (pinfunction "A_A") (pintype "passive"))
      (node (ref "D98") (pin "A") (pinfunction "A_A") (pintype "passive"))
      (node (ref "D99") (pin "A") (pinfunction "A_A") (pintype "passive"))
      (node (ref "E11") (pin "12") (pinfunction "I1_12") (pintype "input"))
      (node (ref "E13") (pin "5") (pinfunction "I1_5") (pintype "input"))
      (node (ref "E13") (pin "6") (pinfunction "I0_6") (pintype "input"))
      (node (ref "E16") (pin "10") (pinfunction "I1_10") (pintype "input"))
      (node (ref "E16") (pin "12") (pinfunction "I1_12") (pintype "input"))
      (node (ref "E16") (pin "5") (pinfunction "I1_5") (pintype "input"))
      (node (ref "E16") (pin "6") (pinfunction "I0_6") (pintype "input"))
      (node (ref "E2") (pin "12") (pinfunction "I1_12") (pintype "input"))
      (node (ref "E2") (pin "6") (pinfunction "I0_6") (pintype "input"))
      (node (ref "E20") (pin "10") (pinfunction "I1_10") (pintype "input"))
      (node (ref "E20") (pin "12") (pinfunction "I1_12") (pintype "input"))
      (node (ref "E20") (pin "5") (pinfunction "I1_5") (pintype "input"))
      (node (ref "E20") (pin "7") (pinfunction "I1_7") (pintype "input"))
      (node (ref "E24") (pin "11") (pinfunction "I0_11") (pintype "input"))
      (node (ref "E24") (pin "5") (pinfunction "I1_5") (pintype "input"))
      (node (ref "E24") (pin "7") (pinfunction "I1_7") (pintype "input"))
      (node (ref "E24") (pin "9") (pinfunction "I0_9") (pintype "input"))
      (node (ref "E28") (pin "11") (pinfunction "I0_11") (pintype "input"))
      (node (ref "E28") (pin "5") (pinfunction "I1_5") (pintype "input"))
      (node (ref "E28") (pin "9") (pinfunction "I0_9") (pintype "input"))
      (node (ref "Q1") (pin "1") (pinfunction "E_1") (pintype "passive"))
      (node (ref "Q10") (pin "1") (pinfunction "E_1") (pintype "passive"))
      (node (ref "Q11") (pin "1") (pinfunction "E_1") (pintype "passive"))
      (node (ref "Q12") (pin "1") (pinfunction "E_1") (pintype "passive"))
      (node (ref "Q13") (pin "3") (pinfunction "C_3") (pintype "passive"))
      (node (ref "Q19") (pin "1") (pinfunction "E_1") (pintype "passive"))
      (node (ref "Q2") (pin "1") (pinfunction "E_1") (pintype "passive"))
      (node (ref "Q3") (pin "1") (pinfunction "E_1") (pintype "passive"))
      (node (ref "Q4") (pin "1") (pinfunction "E_1") (pintype "passive"))
      (node (ref "Q5") (pin "1") (pinfunction "E_1") (pintype "passive"))
      (node (ref "Q6") (pin "1") (pinfunction "E_1") (pintype "passive"))
      (node (ref "Q7") (pin "1") (pinfunction "E_1") (pintype "passive"))
      (node (ref "Q8") (pin "1") (pinfunction "E_1") (pintype "passive"))
      (node (ref "Q9") (pin "1") (pinfunction "E_1") (pintype "passive"))
      (node (ref "R127") (pin "1") (pinfunction "1_1") (pintype "passive"))
      (node (ref "R128") (pin "1") (pinfunction "1_1") (pintype "passive"))
      (node (ref "R129") (pin "1") (pinfunction "1_1") (pintype "passive"))
      (node (ref "R130") (pin "1") (pinfunction "1_1") (pintype "passive"))
      (node (ref "R131") (pin "1") (pinfunction "1_1") (pintype "passive"))
      (node (ref "R132") (pin "1") (pinfunction "1_1") (pintype "passive"))
      (node (ref "R133") (pin "1") (pinfunction "1_1") (pintype "passive"))
      (node (ref "R134") (pin "1") (pinfunction "1_1") (pintype "passive"))
      (node (ref "R135") (pin "1") (pinfunction "1_1") (pintype "passive"))
      (node (ref "R136") (pin "1") (pinfunction "1_1") (pintype "passive"))
      (node (ref "R137") (pin "1") (pinfunction "1_1") (pintype "passive"))
      (node (ref "R138") (pin "1") (pinfunction "1_1") (pintype "passive"))
      (node (ref "R139") (pin "1") (pinfunction "1_1") (pintype "passive"))
      (node (ref "R140") (pin "1") (pinfunction "1_1") (pintype "passive"))
      (node (ref "R141") (pin "1") (pinfunction "1_1") (pintype "passive"))
      (node (ref "R157") (pin "1") (pinfunction "1_1") (pintype "passive"))
      (node (ref "R159") (pin "1") (pinfunction "1_1") (pintype "passive"))
      (node (ref "R160") (pin "1") (pinfunction "1_1") (pintype "passive"))
      (node (ref "R25") (pin "1") (pinfunction "1_1") (pintype "passive"))
      (node (ref "R28") (pin "1") (pinfunction "1_1") (pintype "passive"))
      (node (ref "R31") (pin "1") (pinfunction "1_1") (pintype "passive"))
      (node (ref "R34") (pin "1") (pinfunction "1_1") (pintype "passive"))
      (node (ref "R37") (pin "1") (pinfunction "1_1") (pintype "passive"))
      (node (ref "R40") (pin "1") (pinfunction "1_1") (pintype "passive"))
      (node (ref "R43") (pin "1") (pinfunction "1_1") (pintype "passive"))
      (node (ref "R46") (pin "1") (pinfunction "1_1") (pintype "passive"))
      (node (ref "R49") (pin "1") (pinfunction "1_1") (pintype "passive"))
      (node (ref "R52") (pin "1") (pinfunction "1_1") (pintype "passive"))
      (node (ref "R55") (pin "1") (pinfunction "1_1") (pintype "passive"))
      (node (ref "R58") (pin "1") (pinfunction "1_1") (pintype "passive"))
      (node (ref "U$2") (pin "AC2") (pinfunction "1_AC2") (pintype "bidirectional"))
      (node (ref "U$2") (pin "AF1") (pinfunction "1_AF1") (pintype "bidirectional"))
      (node (ref "U$2") (pin "AF2") (pinfunction "1_AF2") (pintype "bidirectional"))
      (node (ref "U$2") (pin "AN1") (pinfunction "1_AN1") (pintype "bidirectional"))
      (node (ref "U$2") (pin "AN2") (pinfunction "1_AN2") (pintype "bidirectional"))
      (node (ref "U$2") (pin "AT1") (pinfunction "1_AT1") (pintype "bidirectional"))
      (node (ref "U$2") (pin "AT2") (pinfunction "1_AT2") (pintype "bidirectional"))
      (node (ref "U$2") (pin "BC1") (pinfunction "1_BC1") (pintype "bidirectional"))
      (node (ref "U$2") (pin "BC2") (pinfunction "1_BC2") (pintype "bidirectional"))
      (node (ref "U$2") (pin "BF1") (pinfunction "1_BF1") (pintype "bidirectional"))
      (node (ref "U$2") (pin "BF2") (pinfunction "1_BF2") (pintype "bidirectional"))
      (node (ref "U$2") (pin "BN1") (pinfunction "1_BN1") (pintype "bidirectional"))
      (node (ref "U$2") (pin "BN2") (pinfunction "1_BN2") (pintype "bidirectional"))
      (node (ref "U$2") (pin "BT1") (pinfunction "1_BT1") (pintype "bidirectional"))
      (node (ref "U$2") (pin "BT2") (pinfunction "1_BT2") (pintype "bidirectional"))
      (node (ref "U$2") (pin "CC1") (pinfunction "1_CC1") (pintype "bidirectional"))
      (node (ref "U$2") (pin "CC2") (pinfunction "1_CC2") (pintype "bidirectional"))
      (node (ref "U$2") (pin "CF1") (pinfunction "1_CF1") (pintype "bidirectional"))
      (node (ref "U$2") (pin "CF2") (pinfunction "1_CF2") (pintype "bidirectional"))
      (node (ref "U$2") (pin "CN1") (pinfunction "1_CN1") (pintype "bidirectional"))
      (node (ref "U$2") (pin "CN2") (pinfunction "1_CN2") (pintype "bidirectional"))
      (node (ref "U$2") (pin "CT1") (pinfunction "1_CT1") (pintype "bidirectional"))
      (node (ref "U$2") (pin "CT2") (pinfunction "1_CT2") (pintype "bidirectional"))
      (node (ref "U$2") (pin "DC1") (pinfunction "1_DC1") (pintype "bidirectional"))
      (node (ref "U$2") (pin "DC2") (pinfunction "1_DC2") (pintype "bidirectional"))
      (node (ref "U$2") (pin "DF1") (pinfunction "1_DF1") (pintype "bidirectional"))
      (node (ref "U$2") (pin "DF2") (pinfunction "1_DF2") (pintype "bidirectional"))
      (node (ref "U$2") (pin "DT1") (pinfunction "1_DT1") (pintype "bidirectional"))
      (node (ref "U$2") (pin "DT2") (pinfunction "1_DT2") (pintype "bidirectional"))
    )
    (net (code "38") (name "HALT") (class "Default")
      (node (ref "D93") (pin "C") (pinfunction "C_C") (pintype "passive"))
      (node (ref "E11") (pin "10") (pinfunction "I1_10") (pintype "input"))
      (node (ref "R101") (pin "2") (pinfunction "2_2") (pintype "passive"))
    )
    (net (code "39") (name "IND1") (class "Default")
      (node (ref "E7") (pin "1") (pinfunction "O_1") (pintype "open_collector"))
      (node (ref "E7") (pin "4") (pinfunction "O_4") (pintype "open_collector"))
      (node (ref "U$2") (pin "CU2") (pinfunction "1_CU2") (pintype "bidirectional"))
    )
    (net (code "40") (name "IND2") (class "Default")
      (node (ref "E7") (pin "10") (pinfunction "O_10") (pintype "open_collector"))
      (node (ref "U$2") (pin "CV2") (pinfunction "1_CV2") (pintype "bidirectional"))
    )
    (net (code "41") (name "INDSTROBE") (class "Default")
      (node (ref "E18") (pin "10") (pinfunction "I1_10") (pintype "input"))
      (node (ref "E18") (pin "12") (pinfunction "I1_12") (pintype "input"))
      (node (ref "E18") (pin "4") (pinfunction "I0_4") (pintype "input"))
      (node (ref "E18") (pin "6") (pinfunction "I0_6") (pintype "input"))
      (node (ref "E22") (pin "10") (pinfunction "I1_10") (pintype "input"))
      (node (ref "E22") (pin "12") (pinfunction "I1_12") (pintype "input"))
      (node (ref "E22") (pin "4") (pinfunction "I0_4") (pintype "input"))
      (node (ref "E22") (pin "6") (pinfunction "I0_6") (pintype "input"))
      (node (ref "E26") (pin "10") (pinfunction "I1_10") (pintype "input"))
      (node (ref "E26") (pin "12") (pinfunction "I1_12") (pintype "input"))
      (node (ref "E26") (pin "4") (pinfunction "I0_4") (pintype "input"))
      (node (ref "E26") (pin "6") (pinfunction "I0_6") (pintype "input"))
      (node (ref "E9") (pin "4") (pinfunction "O_4") (pintype "output"))
    )
    (net (code "42") (name "INIT") (class "Default")
      (node (ref "E13") (pin "11") (pinfunction "I0_11") (pintype "input"))
      (node (ref "E13") (pin "12") (pinfunction "I1_12") (pintype "input"))
      (node (ref "Q18") (pin "1") (pinfunction "E_1") (pintype "passive"))
      (node (ref "U$2") (pin "CR1") (pinfunction "1_CR1") (pintype "bidirectional"))
    )
    (net (code "43") (name "IR0") (class "Default")
      (node (ref "D76") (pin "A") (pinfunction "A_A") (pintype "passive"))
      (node (ref "E15") (pin "4") (pinfunction "I0_4") (pintype "input"))
      (node (ref "U$2") (pin "DD2") (pinfunction "1_DD2") (pintype "bidirectional"))
    )
    (net (code "44") (name "IR1") (class "Default")
      (node (ref "D77") (pin "A") (pinfunction "A_A") (pintype "passive"))
      (node (ref "E15") (pin "5") (pinfunction "I1_5") (pintype "input"))
      (node (ref "U$2") (pin "DE2") (pinfunction "1_DE2") (pintype "bidirectional"))
    )
    (net (code "45") (name "IR2") (class "Default")
      (node (ref "D78") (pin "A") (pinfunction "A_A") (pintype "passive"))
      (node (ref "E15") (pin "6") (pinfunction "I2_6") (pintype "input"))
      (node (ref "U$2") (pin "DH2") (pinfunction "1_DH2") (pintype "bidirectional"))
    )
    (net (code "46") (name "I{slash}O_PAUSE") (class "Default")
      (node (ref "D82") (pin "A") (pinfunction "A_A") (pintype "passive"))
      (node (ref "U$2") (pin "CD1") (pinfunction "1_CD1") (pintype "bidirectional"))
    )
    (net (code "47") (name "KEY_CONTROL") (class "Default")
      (node (ref "E1") (pin "1") (pinfunction "O_1") (pintype "open_collector"))
      (node (ref "U$2") (pin "DU2") (pinfunction "1_DU2") (pintype "bidirectional"))
    )
    (net (code "48") (name "LA_ENABLE") (class "Default")
      (node (ref "E7") (pin "13") (pinfunction "O_13") (pintype "open_collector"))
      (node (ref "E7") (pin "9") (pinfunction "I1_9") (pintype "input"))
      (node (ref "E9") (pin "9") (pinfunction "I_9") (pintype "input"))
      (node (ref "U$2") (pin "BM2") (pinfunction "1_BM2") (pintype "bidirectional"))
    )
    (net (code "49") (name "LOAD") (class "Default")
      (node (ref "D88") (pin "C") (pinfunction "C_C") (pintype "passive"))
      (node (ref "E12") (pin "4") (pinfunction "I0_4") (pintype "input"))
      (node (ref "E14") (pin "10") (pinfunction "I1_10") (pintype "input"))
      (node (ref "E6") (pin "2") (pinfunction "I1_2") (pintype "input"))
      (node (ref "E8") (pin "9") (pinfunction "I0_9") (pintype "input"))
      (node (ref "R91") (pin "2") (pinfunction "2_2") (pintype "passive"))
    )
    (net (code "50") (name "MA00") (class "Default")
      (node (ref "E24") (pin "6") (pinfunction "I0_6") (pintype "input"))
      (node (ref "U$2") (pin "AD1") (pinfunction "1_AD1") (pintype "bidirectional"))
    )
    (net (code "51") (name "MA01") (class "Default")
      (node (ref "E24") (pin "4") (pinfunction "I0_4") (pintype "input"))
      (node (ref "U$2") (pin "AE1") (pinfunction "1_AE1") (pintype "bidirectional"))
    )
    (net (code "52") (name "MA02") (class "Default")
      (node (ref "E24") (pin "10") (pinfunction "I1_10") (pintype "input"))
      (node (ref "U$2") (pin "AH1") (pinfunction "1_AH1") (pintype "bidirectional"))
    )
    (net (code "53") (name "MA03") (class "Default")
      (node (ref "E24") (pin "12") (pinfunction "I1_12") (pintype "input"))
      (node (ref "U$2") (pin "AJ1") (pinfunction "1_AJ1") (pintype "bidirectional"))
    )
    (net (code "54") (name "MA04") (class "Default")
      (node (ref "E20") (pin "6") (pinfunction "I0_6") (pintype "input"))
      (node (ref "U$2") (pin "BD1") (pinfunction "1_BD1") (pintype "bidirectional"))
    )
    (net (code "55") (name "MA05") (class "Default")
      (node (ref "E20") (pin "4") (pinfunction "I0_4") (pintype "input"))
      (node (ref "U$2") (pin "BE1") (pinfunction "1_BE1") (pintype "bidirectional"))
    )
    (net (code "56") (name "MA06") (class "Default")
      (node (ref "E20") (pin "11") (pinfunction "I0_11") (pintype "input"))
      (node (ref "U$2") (pin "BH1") (pinfunction "1_BH1") (pintype "bidirectional"))
    )
    (net (code "57") (name "MA07") (class "Default")
      (node (ref "E20") (pin "9") (pinfunction "I0_9") (pintype "input"))
      (node (ref "U$2") (pin "BJ1") (pinfunction "1_BJ1") (pintype "bidirectional"))
    )
    (net (code "58") (name "MA08") (class "Default")
      (node (ref "E16") (pin "9") (pinfunction "I0_9") (pintype "input"))
      (node (ref "U$2") (pin "DD1") (pinfunction "1_DD1") (pintype "bidirectional"))
    )
    (net (code "59") (name "MA09") (class "Default")
      (node (ref "E16") (pin "11") (pinfunction "I0_11") (pintype "input"))
      (node (ref "U$2") (pin "DE1") (pinfunction "1_DE1") (pintype "bidirectional"))
    )
    (net (code "60") (name "MA10") (class "Default")
      (node (ref "E16") (pin "7") (pinfunction "I1_7") (pintype "input"))
      (node (ref "U$2") (pin "DH1") (pinfunction "1_DH1") (pintype "bidirectional"))
    )
    (net (code "61") (name "MA11") (class "Default")
      (node (ref "E16") (pin "4") (pinfunction "I0_4") (pintype "input"))
      (node (ref "U$2") (pin "DJ1") (pinfunction "1_DJ1") (pintype "bidirectional"))
    )
    (net (code "62") (name "MD00") (class "Default")
      (node (ref "D49") (pin "A") (pinfunction "A_A") (pintype "passive"))
      (node (ref "U$2") (pin "AK1") (pinfunction "1_AK1") (pintype "bidirectional"))
    )
    (net (code "63") (name "MD01") (class "Default")
      (node (ref "D50") (pin "A") (pinfunction "A_A") (pintype "passive"))
      (node (ref "U$2") (pin "AL1") (pinfunction "1_AL1") (pintype "bidirectional"))
    )
    (net (code "64") (name "MD02") (class "Default")
      (node (ref "D51") (pin "A") (pinfunction "A_A") (pintype "passive"))
      (node (ref "U$2") (pin "AM1") (pinfunction "1_AM1") (pintype "bidirectional"))
    )
    (net (code "65") (name "MD03") (class "Default")
      (node (ref "D52") (pin "A") (pinfunction "A_A") (pintype "passive"))
      (node (ref "E15") (pin "10") (pinfunction "I4_10") (pintype "input"))
      (node (ref "U$2") (pin "AP1") (pinfunction "1_AP1") (pintype "bidirectional"))
    )
    (net (code "66") (name "MD04") (class "Default")
      (node (ref "D53") (pin "A") (pinfunction "A_A") (pintype "passive"))
      (node (ref "U$2") (pin "BK1") (pinfunction "1_BK1") (pintype "bidirectional"))
    )
    (net (code "67") (name "MD05") (class "Default")
      (node (ref "D54") (pin "A") (pinfunction "A_A") (pintype "passive"))
      (node (ref "U$2") (pin "BL1") (pinfunction "1_BL1") (pintype "bidirectional"))
    )
    (net (code "68") (name "MD06") (class "Default")
      (node (ref "D55") (pin "A") (pinfunction "A_A") (pintype "passive"))
      (node (ref "U$2") (pin "BM1") (pinfunction "1_BM1") (pintype "bidirectional"))
    )
    (net (code "69") (name "MD07") (class "Default")
      (node (ref "D56") (pin "A") (pinfunction "A_A") (pintype "passive"))
      (node (ref "U$2") (pin "BP1") (pinfunction "1_BP1") (pintype "bidirectional"))
    )
    (net (code "70") (name "MD08") (class "Default")
      (node (ref "D57") (pin "A") (pinfunction "A_A") (pintype "passive"))
      (node (ref "U$2") (pin "DK1") (pinfunction "1_DK1") (pintype "bidirectional"))
    )
    (net (code "71") (name "MD09") (class "Default")
      (node (ref "D58") (pin "A") (pinfunction "A_A") (pintype "passive"))
      (node (ref "E15") (pin "9") (pinfunction "I3_9") (pintype "input"))
      (node (ref "U$2") (pin "DL1") (pinfunction "1_DL1") (pintype "bidirectional"))
    )
    (net (code "72") (name "MD10") (class "Default")
      (node (ref "D59") (pin "A") (pinfunction "A_A") (pintype "passive"))
      (node (ref "U$2") (pin "DM1") (pinfunction "1_DM1") (pintype "bidirectional"))
    )
    (net (code "73") (name "MD11") (class "Default")
      (node (ref "D60") (pin "A") (pinfunction "A_A") (pintype "passive"))
      (node (ref "E13") (pin "7") (pinfunction "I1_7") (pintype "input"))
      (node (ref "U$2") (pin "DP1") (pinfunction "1_DP1") (pintype "bidirectional"))
    )
    (net (code "74") (name "MD_DIR_IN") (class "Default")
      (node (ref "D79") (pin "A") (pinfunction "A_A") (pintype "passive"))
      (node (ref "E4") (pin "10") (pinfunction "O_10") (pintype "open_collector"))
      (node (ref "U$2") (pin "AK2") (pinfunction "1_AK2") (pintype "bidirectional"))
    )
    (net (code "75") (name "MD_EN") (class "Default")
      (node (ref "R13") (pin "1") (pinfunction "1_1") (pintype "passive"))
      (node (ref "R14") (pin "1") (pinfunction "1_1") (pintype "passive"))
      (node (ref "R142") (pin "1") (pinfunction "1_1") (pintype "passive"))
      (node (ref "R15") (pin "1") (pinfunction "1_1") (pintype "passive"))
      (node (ref "R16") (pin "1") (pinfunction "1_1") (pintype "passive"))
      (node (ref "R17") (pin "1") (pinfunction "1_1") (pintype "passive"))
      (node (ref "R18") (pin "1") (pinfunction "1_1") (pintype "passive"))
      (node (ref "R19") (pin "1") (pinfunction "1_1") (pintype "passive"))
      (node (ref "R20") (pin "1") (pinfunction "1_1") (pintype "passive"))
      (node (ref "R21") (pin "1") (pinfunction "1_1") (pintype "passive"))
      (node (ref "R22") (pin "1") (pinfunction "1_1") (pintype "passive"))
      (node (ref "R23") (pin "1") (pinfunction "1_1") (pintype "passive"))
      (node (ref "R24") (pin "1") (pinfunction "1_1") (pintype "passive"))
      (node (ref "S1") (pin "3") (pinfunction "3_3") (pintype "passive"))
    )
    (net (code "76") (name "MEM_START") (class "Default")
      (node (ref "E1") (pin "13") (pinfunction "O_13") (pintype "open_collector"))
      (node (ref "U$2") (pin "AJ2") (pinfunction "1_AJ2") (pintype "bidirectional"))
    )
    (net (code "77") (name "MQ_EN") (class "Default")
      (node (ref "D108") (pin "C") (pinfunction "C_C") (pintype "passive"))
      (node (ref "D110") (pin "C") (pinfunction "C_C") (pintype "passive"))
      (node (ref "R171") (pin "1") (pinfunction "1_1") (pintype "passive"))
      (node (ref "S1") (pin "2") (pinfunction "2_2") (pintype "passive"))
    )
    (net (code "78") (name "MS_DISABLE") (class "Default")
      (node (ref "E4") (pin "4") (pinfunction "O_4") (pintype "open_collector"))
      (node (ref "U$2") (pin "CV1") (pinfunction "1_CV1") (pintype "bidirectional"))
    )
    (net (code "79") (name "Net-(C13-Pad+)") (class "Default")
      (node (ref "C13") (pin "+") (pinfunction "+_+") (pintype "passive"))
      (node (ref "R153") (pin "2") (pinfunction "2_2") (pintype "passive"))
      (node (ref "R154") (pin "1") (pinfunction "1_1") (pintype "passive"))
    )
    (net (code "80") (name "Net-(D1-PadA)") (class "Default")
      (node (ref "D1") (pin "A") (pinfunction "A_A") (pintype "passive"))
      (node (ref "R26") (pin "2") (pinfunction "2_2") (pintype "passive"))
    )
    (net (code "81") (name "Net-(D2-PadA)") (class "Default")
      (node (ref "D2") (pin "A") (pinfunction "A_A") (pintype "passive"))
      (node (ref "R29") (pin "2") (pinfunction "2_2") (pintype "passive"))
    )
    (net (code "82") (name "Net-(D3-PadA)") (class "Default")
      (node (ref "D3") (pin "A") (pinfunction "A_A") (pintype "passive"))
      (node (ref "R32") (pin "2") (pinfunction "2_2") (pintype "passive"))
    )
    (net (code "83") (name "Net-(D4-PadA)") (class "Default")
      (node (ref "D4") (pin "A") (pinfunction "A_A") (pintype "passive"))
      (node (ref "R35") (pin "2") (pinfunction "2_2") (pintype "passive"))
    )
    (net (code "84") (name "Net-(D5-PadA)") (class "Default")
      (node (ref "D5") (pin "A") (pinfunction "A_A") (pintype "passive"))
      (node (ref "R38") (pin "2") (pinfunction "2_2") (pintype "passive"))
    )
    (net (code "85") (name "Net-(D6-PadA)") (class "Default")
      (node (ref "D6") (pin "A") (pinfunction "A_A") (pintype "passive"))
      (node (ref "R41") (pin "2") (pinfunction "2_2") (pintype "passive"))
    )
    (net (code "86") (name "Net-(D7-PadA)") (class "Default")
      (node (ref "D7") (pin "A") (pinfunction "A_A") (pintype "passive"))
      (node (ref "R44") (pin "2") (pinfunction "2_2") (pintype "passive"))
    )
    (net (code "87") (name "Net-(D8-PadA)") (class "Default")
      (node (ref "D8") (pin "A") (pinfunction "A_A") (pintype "passive"))
      (node (ref "R47") (pin "2") (pinfunction "2_2") (pintype "passive"))
    )
    (net (code "88") (name "Net-(D9-PadA)") (class "Default")
      (node (ref "D9") (pin "A") (pinfunction "A_A") (pintype "passive"))
      (node (ref "R50") (pin "2") (pinfunction "2_2") (pintype "passive"))
    )
    (net (code "89") (name "Net-(D10-PadA)") (class "Default")
      (node (ref "D10") (pin "A") (pinfunction "A_A") (pintype "passive"))
      (node (ref "R53") (pin "2") (pinfunction "2_2") (pintype "passive"))
    )
    (net (code "90") (name "Net-(D11-PadA)") (class "Default")
      (node (ref "D11") (pin "A") (pinfunction "A_A") (pintype "passive"))
      (node (ref "R56") (pin "2") (pinfunction "2_2") (pintype "passive"))
    )
    (net (code "91") (name "Net-(D12-PadA)") (class "Default")
      (node (ref "D12") (pin "A") (pinfunction "A_A") (pintype "passive"))
      (node (ref "R59") (pin "2") (pinfunction "2_2") (pintype "passive"))
    )
    (net (code "92") (name "Net-(D13-PadC)") (class "Default")
      (node (ref "D13") (pin "C") (pinfunction "C_C") (pintype "passive"))
      (node (ref "D60") (pin "C") (pinfunction "C_C") (pintype "passive"))
      (node (ref "R24") (pin "2") (pinfunction "2_2") (pintype "passive"))
    )
    (net (code "93") (name "Net-(D14-PadC)") (class "Default")
      (node (ref "D14") (pin "C") (pinfunction "C_C") (pintype "passive"))
      (node (ref "D59") (pin "C") (pinfunction "C_C") (pintype "passive"))
      (node (ref "R23") (pin "2") (pinfunction "2_2") (pintype "passive"))
    )
    (net (code "94") (name "Net-(D15-PadC)") (class "Default")
      (node (ref "D15") (pin "C") (pinfunction "C_C") (pintype "passive"))
      (node (ref "D58") (pin "C") (pinfunction "C_C") (pintype "passive"))
      (node (ref "R22") (pin "2") (pinfunction "2_2") (pintype "passive"))
    )
    (net (code "95") (name "Net-(D16-PadC)") (class "Default")
      (node (ref "D16") (pin "C") (pinfunction "C_C") (pintype "passive"))
      (node (ref "D57") (pin "C") (pinfunction "C_C") (pintype "passive"))
      (node (ref "R21") (pin "2") (pinfunction "2_2") (pintype "passive"))
    )
    (net (code "96") (name "Net-(D17-PadC)") (class "Default")
      (node (ref "D17") (pin "C") (pinfunction "C_C") (pintype "passive"))
      (node (ref "D56") (pin "C") (pinfunction "C_C") (pintype "passive"))
      (node (ref "R20") (pin "2") (pinfunction "2_2") (pintype "passive"))
    )
    (net (code "97") (name "Net-(D18-PadC)") (class "Default")
      (node (ref "D18") (pin "C") (pinfunction "C_C") (pintype "passive"))
      (node (ref "D55") (pin "C") (pinfunction "C_C") (pintype "passive"))
      (node (ref "R19") (pin "2") (pinfunction "2_2") (pintype "passive"))
    )
    (net (code "98") (name "Net-(D19-PadC)") (class "Default")
      (node (ref "D19") (pin "C") (pinfunction "C_C") (pintype "passive"))
      (node (ref "D54") (pin "C") (pinfunction "C_C") (pintype "passive"))
      (node (ref "R18") (pin "2") (pinfunction "2_2") (pintype "passive"))
    )
    (net (code "99") (name "Net-(D20-PadC)") (class "Default")
      (node (ref "D20") (pin "C") (pinfunction "C_C") (pintype "passive"))
      (node (ref "D53") (pin "C") (pinfunction "C_C") (pintype "passive"))
      (node (ref "R17") (pin "2") (pinfunction "2_2") (pintype "passive"))
    )
    (net (code "100") (name "Net-(D21-PadC)") (class "Default")
      (node (ref "D21") (pin "C") (pinfunction "C_C") (pintype "passive"))
      (node (ref "D52") (pin "C") (pinfunction "C_C") (pintype "passive"))
      (node (ref "R16") (pin "2") (pinfunction "2_2") (pintype "passive"))
    )
    (net (code "101") (name "Net-(D22-PadC)") (class "Default")
      (node (ref "D22") (pin "C") (pinfunction "C_C") (pintype "passive"))
      (node (ref "D51") (pin "C") (pinfunction "C_C") (pintype "passive"))
      (node (ref "R15") (pin "2") (pinfunction "2_2") (pintype "passive"))
    )
    (net (code "102") (name "Net-(D23-PadC)") (class "Default")
      (node (ref "D23") (pin "C") (pinfunction "C_C") (pintype "passive"))
      (node (ref "D50") (pin "C") (pinfunction "C_C") (pintype "passive"))
      (node (ref "R14") (pin "2") (pinfunction "2_2") (pintype "passive"))
    )
    (net (code "103") (name "Net-(D24-PadC)") (class "Default")
      (node (ref "D24") (pin "C") (pinfunction "C_C") (pintype "passive"))
      (node (ref "D49") (pin "C") (pinfunction "C_C") (pintype "passive"))
      (node (ref "R13") (pin "2") (pinfunction "2_2") (pintype "passive"))
    )
    (net (code "104") (name "Net-(D25-PadC)") (class "Default")
      (node (ref "D25") (pin "C") (pinfunction "C_C") (pintype "passive"))
      (node (ref "D72") (pin "C") (pinfunction "C_C") (pintype "passive"))
      (node (ref "R84") (pin "1") (pinfunction "1_1") (pintype "passive"))
    )
    (net (code "105") (name "Net-(D26-PadC)") (class "Default")
      (node (ref "D26") (pin "C") (pinfunction "C_C") (pintype "passive"))
      (node (ref "D71") (pin "C") (pinfunction "C_C") (pintype "passive"))
      (node (ref "R82") (pin "1") (pinfunction "1_1") (pintype "passive"))
    )
    (net (code "106") (name "Net-(D27-PadC)") (class "Default")
      (node (ref "D27") (pin "C") (pinfunction "C_C") (pintype "passive"))
      (node (ref "D70") (pin "C") (pinfunction "C_C") (pintype "passive"))
      (node (ref "R80") (pin "1") (pinfunction "1_1") (pintype "passive"))
    )
    (net (code "107") (name "Net-(D28-PadC)") (class "Default")
      (node (ref "D28") (pin "C") (pinfunction "C_C") (pintype "passive"))
      (node (ref "D69") (pin "C") (pinfunction "C_C") (pintype "passive"))
      (node (ref "R78") (pin "1") (pinfunction "1_1") (pintype "passive"))
    )
    (net (code "108") (name "Net-(D29-PadC)") (class "Default")
      (node (ref "D29") (pin "C") (pinfunction "C_C") (pintype "passive"))
      (node (ref "D68") (pin "C") (pinfunction "C_C") (pintype "passive"))
      (node (ref "R76") (pin "1") (pinfunction "1_1") (pintype "passive"))
    )
    (net (code "109") (name "Net-(D30-PadC)") (class "Default")
      (node (ref "D30") (pin "C") (pinfunction "C_C") (pintype "passive"))
      (node (ref "D67") (pin "C") (pinfunction "C_C") (pintype "passive"))
      (node (ref "R74") (pin "1") (pinfunction "1_1") (pintype "passive"))
    )
    (net (code "110") (name "Net-(D31-PadC)") (class "Default")
      (node (ref "D31") (pin "C") (pinfunction "C_C") (pintype "passive"))
      (node (ref "D66") (pin "C") (pinfunction "C_C") (pintype "passive"))
      (node (ref "R72") (pin "1") (pinfunction "1_1") (pintype "passive"))
    )
    (net (code "111") (name "Net-(D32-PadC)") (class "Default")
      (node (ref "D32") (pin "C") (pinfunction "C_C") (pintype "passive"))
      (node (ref "D65") (pin "C") (pinfunction "C_C") (pintype "passive"))
      (node (ref "R70") (pin "1") (pinfunction "1_1") (pintype "passive"))
    )
    (net (code "112") (name "Net-(D33-PadC)") (class "Default")
      (node (ref "D33") (pin "C") (pinfunction "C_C") (pintype "passive"))
      (node (ref "D64") (pin "C") (pinfunction "C_C") (pintype "passive"))
      (node (ref "R68") (pin "1") (pinfunction "1_1") (pintype "passive"))
    )
    (net (code "113") (name "Net-(D34-PadC)") (class "Default")
      (node (ref "D34") (pin "C") (pinfunction "C_C") (pintype "passive"))
      (node (ref "D63") (pin "C") (pinfunction "C_C") (pintype "passive"))
      (node (ref "R66") (pin "1") (pinfunction "1_1") (pintype "passive"))
    )
    (net (code "114") (name "Net-(D35-PadC)") (class "Default")
      (node (ref "D35") (pin "C") (pinfunction "C_C") (pintype "passive"))
      (node (ref "D62") (pin "C") (pinfunction "C_C") (pintype "passive"))
      (node (ref "R64") (pin "1") (pinfunction "1_1") (pintype "passive"))
    )
    (net (code "115") (name "Net-(D36-PadC)") (class "Default")
      (node (ref "D36") (pin "C") (pinfunction "C_C") (pintype "passive"))
      (node (ref "D61") (pin "C") (pinfunction "C_C") (pintype "passive"))
      (node (ref "R62") (pin "1") (pinfunction "1_1") (pintype "passive"))
    )
    (net (code "116") (name "Net-(D37-PadC)") (class "Default")
      (node (ref "D37") (pin "C") (pinfunction "C_C") (pintype "passive"))
      (node (ref "D84") (pin "C") (pinfunction "C_C") (pintype "passive"))
      (node (ref "R83") (pin "1") (pinfunction "1_1") (pintype "passive"))
    )
    (net (code "117") (name "Net-(D38-PadC)") (class "Default")
      (node (ref "D38") (pin "C") (pinfunction "C_C") (pintype "passive"))
      (node (ref "D83") (pin "C") (pinfunction "C_C") (pintype "passive"))
      (node (ref "R81") (pin "1") (pinfunction "1_1") (pintype "passive"))
    )
    (net (code "118") (name "Net-(D39-PadC)") (class "Default")
      (node (ref "D39") (pin "C") (pinfunction "C_C") (pintype "passive"))
      (node (ref "D82") (pin "C") (pinfunction "C_C") (pintype "passive"))
      (node (ref "R79") (pin "1") (pinfunction "1_1") (pintype "passive"))
    )
    (net (code "119") (name "Net-(D40-PadC)") (class "Default")
      (node (ref "D40") (pin "C") (pinfunction "C_C") (pintype "passive"))
      (node (ref "D81") (pin "C") (pinfunction "C_C") (pintype "passive"))
      (node (ref "R77") (pin "1") (pinfunction "1_1") (pintype "passive"))
    )
    (net (code "120") (name "Net-(D41-PadC)") (class "Default")
      (node (ref "D41") (pin "C") (pinfunction "C_C") (pintype "passive"))
      (node (ref "D80") (pin "C") (pinfunction "C_C") (pintype "passive"))
      (node (ref "R75") (pin "1") (pinfunction "1_1") (pintype "passive"))
    )
    (net (code "121") (name "Net-(D42-PadC)") (class "Default")
      (node (ref "D42") (pin "C") (pinfunction "C_C") (pintype "passive"))
      (node (ref "D79") (pin "C") (pinfunction "C_C") (pintype "passive"))
      (node (ref "R73") (pin "1") (pinfunction "1_1") (pintype "passive"))
    )
    (net (code "122") (name "Net-(D43-PadC)") (class "Default")
      (node (ref "D43") (pin "C") (pinfunction "C_C") (pintype "passive"))
      (node (ref "D78") (pin "C") (pinfunction "C_C") (pintype "passive"))
      (node (ref "R71") (pin "1") (pinfunction "1_1") (pintype "passive"))
    )
    (net (code "123") (name "Net-(D44-PadC)") (class "Default")
      (node (ref "D44") (pin "C") (pinfunction "C_C") (pintype "passive"))
      (node (ref "D77") (pin "C") (pinfunction "C_C") (pintype "passive"))
      (node (ref "R69") (pin "1") (pinfunction "1_1") (pintype "passive"))
    )
    (net (code "124") (name "Net-(D45-PadC)") (class "Default")
      (node (ref "D45") (pin "C") (pinfunction "C_C") (pintype "passive"))
      (node (ref "D76") (pin "C") (pinfunction "C_C") (pintype "passive"))
      (node (ref "R67") (pin "1") (pinfunction "1_1") (pintype "passive"))
    )
    (net (code "125") (name "Net-(D46-PadC)") (class "Default")
      (node (ref "D46") (pin "C") (pinfunction "C_C") (pintype "passive"))
      (node (ref "D75") (pin "C") (pinfunction "C_C") (pintype "passive"))
      (node (ref "R65") (pin "1") (pinfunction "1_1") (pintype "passive"))
    )
    (net (code "126") (name "Net-(D47-PadC)") (class "Default")
      (node (ref "D47") (pin "C") (pinfunction "C_C") (pintype "passive"))
      (node (ref "D74") (pin "C") (pinfunction "C_C") (pintype "passive"))
      (node (ref "R63") (pin "1") (pinfunction "1_1") (pintype "passive"))
    )
    (net (code "127") (name "Net-(D48-PadC)") (class "Default")
      (node (ref "D48") (pin "C") (pinfunction "C_C") (pintype "passive"))
      (node (ref "D73") (pin "C") (pinfunction "C_C") (pintype "passive"))
      (node (ref "R61") (pin "1") (pinfunction "1_1") (pintype "passive"))
    )
    (net (code "128") (name "Net-(D110-PadA)") (class "Default")
      (node (ref "D110") (pin "A") (pinfunction "A_A") (pintype "passive"))
      (node (ref "D111") (pin "A") (pinfunction "A_A") (pintype "passive"))
      (node (ref "R150") (pin "1") (pinfunction "1_1") (pintype "passive"))
    )
    (net (code "129") (name "Net-(D112-PadA)") (class "Default")
      (node (ref "D112") (pin "A") (pinfunction "A_A") (pintype "passive"))
      (node (ref "D113") (pin "A") (pinfunction "A_A") (pintype "passive"))
      (node (ref "R149") (pin "1") (pinfunction "1_1") (pintype "passive"))
    )
    (net (code "130") (name "Net-(D116-PadC)") (class "Default")
      (node (ref "D116") (pin "C") (pinfunction "C_C") (pintype "passive"))
      (node (ref "D117") (pin "A") (pinfunction "A_A") (pintype "passive"))
    )
    (net (code "131") (name "Net-(D118-PadA)") (class "Default")
      (node (ref "D118") (pin "A") (pinfunction "A_A") (pintype "passive"))
      (node (ref "D119") (pin "C") (pinfunction "C_C") (pintype "passive"))
    )
    (net (code "132") (name "Net-(D122-PadA)") (class "Default")
      (node (ref "D122") (pin "A") (pinfunction "A_A") (pintype "passive"))
      (node (ref "R169") (pin "2") (pinfunction "2_2") (pintype "passive"))
    )
    (net (code "133") (name "Net-(D123-PadC)") (class "Default")
      (node (ref "D123") (pin "C") (pinfunction "C_C") (pintype "passive"))
      (node (ref "D124") (pin "A") (pinfunction "A_A") (pintype "passive"))
    )
    (net (code "134") (name "Net-(D124-PadC)") (class "Default")
      (node (ref "D124") (pin "C") (pinfunction "C_C") (pintype "passive"))
      (node (ref "D125") (pin "A") (pinfunction "A_A") (pintype "passive"))
    )
    (net (code "135") (name "Net-(E1A-I0)") (class "Default")
      (node (ref "E1") (pin "2") (pinfunction "I0_2") (pintype "input"))
      (node (ref "E8") (pin "12") (pinfunction "O_12") (pintype "output"))
    )
    (net (code "136") (name "Net-(E1D-I0)") (class "Default")
      (node (ref "E1") (pin "11") (pinfunction "I0_11") (pintype "input"))
      (node (ref "E2") (pin "10") (pinfunction "I1_10") (pintype "input"))
      (node (ref "E2") (pin "13") (pinfunction "O_13") (pintype "output"))
      (node (ref "E3") (pin "1") (pinfunction "I0_1") (pintype "input"))
      (node (ref "E3") (pin "4") (pinfunction "I0_4") (pintype "input"))
    )
    (net (code "137") (name "Net-(E2A-O)") (class "Default")
      (node (ref "E2") (pin "3") (pinfunction "O_3") (pintype "output"))
      (node (ref "E6") (pin "12") (pinfunction "I0_12") (pintype "input"))
    )
    (net (code "138") (name "Net-(E2B-O)") (class "Default")
      (node (ref "E2") (pin "2") (pinfunction "O_2") (pintype "output"))
      (node (ref "E3") (pin "13") (pinfunction "I1_13") (pintype "input"))
    )
    (net (code "139") (name "Net-(E2C-I0)") (class "Default")
      (node (ref "C14") (pin "1") (pinfunction "1_1") (pintype "passive"))
      (node (ref "E2") (pin "9") (pinfunction "I0_9") (pintype "input"))
      (node (ref "R159") (pin "2") (pinfunction "2_2") (pintype "passive"))
      (node (ref "R160") (pin "2") (pinfunction "2_2") (pintype "passive"))
    )
    (net (code "140") (name "Net-(E2C-O)") (class "Default")
      (node (ref "C15") (pin "2") (pinfunction "2_2") (pintype "passive"))
      (node (ref "E2") (pin "14") (pinfunction "O_14") (pintype "output"))
    )
    (net (code "141") (name "Net-(E2D-I0)") (class "Default")
      (node (ref "C15") (pin "1") (pinfunction "1_1") (pintype "passive"))
      (node (ref "D121") (pin "A") (pinfunction "A_A") (pintype "passive"))
      (node (ref "E2") (pin "11") (pinfunction "I0_11") (pintype "input"))
      (node (ref "R161") (pin "1") (pinfunction "1_1") (pintype "passive"))
    )
    (net (code "142") (name "Net-(E3C-I0)") (class "Default")
      (node (ref "E3") (pin "12") (pinfunction "I0_12") (pintype "input"))
      (node (ref "E3") (pin "9") (pinfunction "I0_9") (pintype "input"))
      (node (ref "E5") (pin "8") (pinfunction "O_8") (pintype "output"))
    )
    (net (code "143") (name "Net-(E3C-I1)") (class "Default")
      (node (ref "E3") (pin "10") (pinfunction "I1_10") (pintype "input"))
      (node (ref "E3") (pin "11") (pinfunction "O_11") (pintype "output"))
    )
    (net (code "144") (name "Net-(E3C-O)") (class "Default")
      (node (ref "E3") (pin "8") (pinfunction "O_8") (pintype "output"))
      (node (ref "E9") (pin "3") (pinfunction "I_3") (pintype "input"))
    )
    (net (code "145") (name "Net-(E4B-I0)") (class "Default")
      (node (ref "E4") (pin "5") (pinfunction "I0_5") (pintype "input"))
      (node (ref "E6") (pin "8") (pinfunction "O_8") (pintype "output"))
    )
    (net (code "146") (name "Net-(E4D-I0)") (class "Default")
      (node (ref "E4") (pin "11") (pinfunction "I0_11") (pintype "input"))
      (node (ref "E4") (pin "12") (pinfunction "I1_12") (pintype "input"))
      (node (ref "E6") (pin "6") (pinfunction "O_6") (pintype "output"))
    )
    (net (code "147") (name "Net-(E5C-I0)") (class "Default")
      (node (ref "D109") (pin "C") (pinfunction "C_C") (pintype "passive"))
      (node (ref "E5") (pin "9") (pinfunction "I0_9") (pintype "input"))
      (node (ref "R147") (pin "1") (pinfunction "1_1") (pintype "passive"))
      (node (ref "R148") (pin "2") (pinfunction "2_2") (pintype "passive"))
    )
    (net (code "148") (name "Net-(E5C-I1)") (class "Default")
      (node (ref "D128") (pin "C") (pinfunction "C_C") (pintype "passive"))
      (node (ref "E5") (pin "10") (pinfunction "I1_10") (pintype "input"))
      (node (ref "R146") (pin "1") (pinfunction "1_1") (pintype "passive"))
      (node (ref "R171") (pin "2") (pinfunction "2_2") (pintype "passive"))
    )
    (net (code "149") (name "Net-(E5C-I2)") (class "Default")
      (node (ref "D127") (pin "C") (pinfunction "C_C") (pintype "passive"))
      (node (ref "E5") (pin "11") (pinfunction "I2_11") (pintype "input"))
      (node (ref "R144") (pin "1") (pinfunction "1_1") (pintype "passive"))
      (node (ref "R173") (pin "2") (pinfunction "2_2") (pintype "passive"))
    )
    (net (code "150") (name "Net-(E7A-I0)") (class "Default")
      (node (ref "E7") (pin "2") (pinfunction "I0_2") (pintype "input"))
      (node (ref "E7") (pin "3") (pinfunction "I1_3") (pintype "input"))
      (node (ref "E9") (pin "10") (pinfunction "O_10") (pintype "output"))
    )
    (net (code "151") (name "Net-(E7B-I0)") (class "Default")
      (node (ref "E7") (pin "5") (pinfunction "I0_5") (pintype "input"))
      (node (ref "E7") (pin "6") (pinfunction "I1_6") (pintype "input"))
      (node (ref "E9") (pin "8") (pinfunction "O_8") (pintype "output"))
    )
    (net (code "152") (name "Net-(E7C-I0)") (class "Default")
      (node (ref "E7") (pin "8") (pinfunction "I0_8") (pintype "input"))
      (node (ref "E9") (pin "6") (pinfunction "O_6") (pintype "output"))
    )
    (net (code "153") (name "Net-(E8B-I1)") (class "Default")
      (node (ref "E8") (pin "4") (pinfunction "I1_4") (pintype "input"))
      (node (ref "E8") (pin "8") (pinfunction "O_8") (pintype "output"))
    )
    (net (code "154") (name "Net-(E9A-O)") (class "Default")
      (node (ref "E9") (pin "2") (pinfunction "O_2") (pintype "output"))
      (node (ref "R166") (pin "1") (pinfunction "1_1") (pintype "passive"))
    )
    (net (code "155") (name "Net-(E9C-I)") (class "Default")
      (node (ref "D114") (pin "C") (pinfunction "C_C") (pintype "passive"))
      (node (ref "E9") (pin "5") (pinfunction "I_5") (pintype "input"))
      (node (ref "R150") (pin "2") (pinfunction "2_2") (pintype "passive"))
      (node (ref "R151") (pin "1") (pinfunction "1_1") (pintype "passive"))
    )
    (net (code "156") (name "Net-(E9E-I)") (class "Default")
      (node (ref "D115") (pin "C") (pinfunction "C_C") (pintype "passive"))
      (node (ref "E9") (pin "11") (pinfunction "I_11") (pintype "input"))
      (node (ref "R149") (pin "2") (pinfunction "2_2") (pintype "passive"))
      (node (ref "R152") (pin "1") (pinfunction "1_1") (pintype "passive"))
    )
    (net (code "157") (name "Net-(E10A-I)") (class "Default")
      (node (ref "E10") (pin "1") (pinfunction "I_1") (pintype "input"))
      (node (ref "E12") (pin "3") (pinfunction "O_3") (pintype "output"))
    )
    (net (code "158") (name "Net-(E10B-O)") (class "Default")
      (node (ref "E10") (pin "4") (pinfunction "O_4") (pintype "output"))
      (node (ref "E14") (pin "12") (pinfunction "I2_12") (pintype "input"))
    )
    (net (code "159") (name "Net-(E10C-O)") (class "Default")
      (node (ref "E10") (pin "6") (pinfunction "O_6") (pintype "output"))
      (node (ref "E3") (pin "5") (pinfunction "I1_5") (pintype "input"))
    )
    (net (code "160") (name "Net-(E10D-I)") (class "Default")
      (node (ref "E10") (pin "9") (pinfunction "I_9") (pintype "input"))
      (node (ref "E3") (pin "6") (pinfunction "O_6") (pintype "output"))
    )
    (net (code "161") (name "Net-(E10D-O)") (class "Default")
      (node (ref "E10") (pin "8") (pinfunction "O_8") (pintype "output"))
      (node (ref "R164") (pin "1") (pinfunction "1_1") (pintype "passive"))
      (node (ref "R174") (pin "1") (pinfunction "1_1") (pintype "passive"))
    )
    (net (code "162") (name "Net-(E10E-I)") (class "Default")
      (node (ref "E10") (pin "11") (pinfunction "I_11") (pintype "input"))
      (node (ref "E3") (pin "3") (pinfunction "O_3") (pintype "output"))
    )
    (net (code "163") (name "Net-(E10E-O)") (class "Default")
      (node (ref "E10") (pin "10") (pinfunction "O_10") (pintype "output"))
      (node (ref "R162") (pin "1") (pinfunction "1_1") (pintype "passive"))
      (node (ref "R172") (pin "1") (pinfunction "1_1") (pintype "passive"))
    )
    (net (code "164") (name "Net-(E10F-I)") (class "Default")
      (node (ref "E10") (pin "13") (pinfunction "I_13") (pintype "input"))
      (node (ref "E4") (pin "2") (pinfunction "I0_2") (pintype "input"))
      (node (ref "E4") (pin "9") (pinfunction "I1_9") (pintype "input"))
      (node (ref "E6") (pin "3") (pinfunction "O_3") (pintype "output"))
    )
    (net (code "165") (name "Net-(E10F-O)") (class "Default")
      (node (ref "E10") (pin "12") (pinfunction "O_12") (pintype "output"))
      (node (ref "E6") (pin "9") (pinfunction "I0_9") (pintype "input"))
    )
    (net (code "166") (name "Net-(E11B-O)") (class "Default")
      (node (ref "E11") (pin "2") (pinfunction "O_2") (pintype "output"))
      (node (ref "E12") (pin "1") (pinfunction "I0_1") (pintype "input"))
    )
    (net (code "167") (name "Net-(E11C-O)") (class "Default")
      (node (ref "E11") (pin "14") (pinfunction "O_14") (pintype "output"))
      (node (ref "E6") (pin "4") (pinfunction "I0_4") (pintype "input"))
    )
    (net (code "168") (name "Net-(E11D-O)") (class "Default")
      (node (ref "E11") (pin "13") (pinfunction "O_13") (pintype "output"))
      (node (ref "E8") (pin "3") (pinfunction "I0_3") (pintype "input"))
    )
    (net (code "169") (name "Net-(E12A-I1)") (class "Default")
      (node (ref "E12") (pin "2") (pinfunction "I1_2") (pintype "input"))
      (node (ref "E14") (pin "8") (pinfunction "O_8") (pintype "output"))
    )
    (net (code "170") (name "Net-(E12B-O)") (class "Default")
      (node (ref "E12") (pin "6") (pinfunction "O_6") (pintype "output"))
      (node (ref "E3") (pin "2") (pinfunction "I1_2") (pintype "input"))
      (node (ref "E7") (pin "12") (pinfunction "I1_12") (pintype "input"))
    )
    (net (code "171") (name "Net-(E12C-I0)") (class "Default")
      (node (ref "E12") (pin "12") (pinfunction "I0_12") (pintype "input"))
      (node (ref "E12") (pin "9") (pinfunction "I0_9") (pintype "input"))
      (node (ref "E5") (pin "12") (pinfunction "O_12") (pintype "output"))
    )
    (net (code "172") (name "Net-(E12C-I1)") (class "Default")
      (node (ref "E12") (pin "10") (pinfunction "I1_10") (pintype "input"))
      (node (ref "E12") (pin "11") (pinfunction "O_11") (pintype "output"))
    )
    (net (code "173") (name "Net-(E13A-O)") (class "Default")
      (node (ref "E13") (pin "3") (pinfunction "O_3") (pintype "output"))
      (node (ref "E15") (pin "11") (pinfunction "I5_11") (pintype "input"))
    )
    (net (code "174") (name "Net-(E13B-O)") (class "Default")
      (node (ref "E13") (pin "2") (pinfunction "O_2") (pintype "output"))
      (node (ref "E15") (pin "12") (pinfunction "I6_12") (pintype "input"))
    )
    (net (code "175") (name "Net-(E13C-O)") (class "Default")
      (node (ref "E13") (pin "14") (pinfunction "O_14") (pintype "output"))
      (node (ref "E5") (pin "1") (pinfunction "I0_1") (pintype "input"))
    )
    (net (code "176") (name "Net-(E13D-O)") (class "Default")
      (node (ref "E13") (pin "13") (pinfunction "O_13") (pintype "output"))
      (node (ref "E5") (pin "2") (pinfunction "I1_2") (pintype "input"))
    )
    (net (code "177") (name "Net-(E14A-I0)") (class "Default")
      (node (ref "E14") (pin "1") (pinfunction "I0_1") (pintype "input"))
      (node (ref "E14") (pin "2") (pinfunction "I1_2") (pintype "input"))
      (node (ref "E6") (pin "11") (pinfunction "O_11") (pintype "output"))
    )
    (net (code "178") (name "Net-(E14A-I2)") (class "Default")
      (node (ref "E14") (pin "4") (pinfunction "I2_4") (pintype "input"))
      (node (ref "E14") (pin "5") (pinfunction "I3_5") (pintype "input"))
      (node (ref "E8") (pin "6") (pinfunction "O_6") (pintype "output"))
    )
    (net (code "179") (name "Net-(E14A-O)") (class "Default")
      (node (ref "E14") (pin "6") (pinfunction "O_6") (pintype "output"))
      (node (ref "E17") (pin "12") (pinfunction "I1_12") (pintype "input"))
      (node (ref "E17") (pin "2") (pinfunction "I0_2") (pintype "input"))
      (node (ref "E17") (pin "5") (pinfunction "I0_5") (pintype "input"))
      (node (ref "E17") (pin "9") (pinfunction "I1_9") (pintype "input"))
      (node (ref "E21") (pin "12") (pinfunction "I1_12") (pintype "input"))
      (node (ref "E21") (pin "2") (pinfunction "I0_2") (pintype "input"))
      (node (ref "E21") (pin "5") (pinfunction "I0_5") (pintype "input"))
      (node (ref "E21") (pin "9") (pinfunction "I1_9") (pintype "input"))
      (node (ref "E25") (pin "11") (pinfunction "I0_11") (pintype "input"))
      (node (ref "E25") (pin "2") (pinfunction "I0_2") (pintype "input"))
      (node (ref "E25") (pin "5") (pinfunction "I0_5") (pintype "input"))
      (node (ref "E25") (pin "9") (pinfunction "I1_9") (pintype "input"))
    )
    (net (code "180") (name "Net-(E15A-O)") (class "Default")
      (node (ref "E15") (pin "3") (pinfunction "O_3") (pintype "output"))
      (node (ref "E6") (pin "13") (pinfunction "I1_13") (pintype "input"))
    )
    (net (code "181") (name "Net-(E16A-O)") (class "Default")
      (node (ref "E16") (pin "3") (pinfunction "O_3") (pintype "output"))
      (node (ref "E19") (pin "9") (pinfunction "I_9") (pintype "input"))
    )
    (net (code "182") (name "Net-(E16B-O)") (class "Default")
      (node (ref "E16") (pin "2") (pinfunction "O_2") (pintype "output"))
      (node (ref "E19") (pin "11") (pinfunction "I_11") (pintype "input"))
    )
    (net (code "183") (name "Net-(E16C-O)") (class "Default")
      (node (ref "E16") (pin "14") (pinfunction "O_14") (pintype "output"))
      (node (ref "E19") (pin "1") (pinfunction "I_1") (pintype "input"))
    )
    (net (code "184") (name "Net-(E16D-O)") (class "Default")
      (node (ref "E16") (pin "13") (pinfunction "O_13") (pintype "output"))
      (node (ref "E19") (pin "13") (pinfunction "I_13") (pintype "input"))
    )
    (net (code "185") (name "Net-(E17A-I1)") (class "Default")
      (node (ref "D102") (pin "C") (pinfunction "C_C") (pintype "passive"))
      (node (ref "E17") (pin "3") (pinfunction "I1_3") (pintype "input"))
      (node (ref "R119") (pin "2") (pinfunction "2_2") (pintype "passive"))
    )
    (net (code "186") (name "Net-(E17B-I1)") (class "Default")
      (node (ref "D103") (pin "C") (pinfunction "C_C") (pintype "passive"))
      (node (ref "E17") (pin "6") (pinfunction "I1_6") (pintype "input"))
      (node (ref "R121") (pin "2") (pinfunction "2_2") (pintype "passive"))
    )
    (net (code "187") (name "Net-(E17C-I0)") (class "Default")
      (node (ref "D105") (pin "C") (pinfunction "C_C") (pintype "passive"))
      (node (ref "E17") (pin "8") (pinfunction "I0_8") (pintype "input"))
      (node (ref "R125") (pin "2") (pinfunction "2_2") (pintype "passive"))
    )
    (net (code "188") (name "Net-(E17D-I0)") (class "Default")
      (node (ref "D104") (pin "C") (pinfunction "C_C") (pintype "passive"))
      (node (ref "E17") (pin "11") (pinfunction "I0_11") (pintype "input"))
      (node (ref "R123") (pin "2") (pinfunction "2_2") (pintype "passive"))
    )
    (net (code "189") (name "Net-(E18A-I1)") (class "Default")
      (node (ref "D16") (pin "A") (pinfunction "A_A") (pintype "passive"))
      (node (ref "D28") (pin "A") (pinfunction "A_A") (pintype "passive"))
      (node (ref "D40") (pin "A") (pinfunction "A_A") (pintype "passive"))
      (node (ref "E18") (pin "5") (pinfunction "I1_5") (pintype "input"))
      (node (ref "R9") (pin "1") (pinfunction "1_1") (pintype "passive"))
    )
    (net (code "190") (name "Net-(E18A-O)") (class "Default")
      (node (ref "E18") (pin "3") (pinfunction "O_3") (pintype "output"))
      (node (ref "R50") (pin "1") (pinfunction "1_1") (pintype "passive"))
      (node (ref "R51") (pin "1") (pinfunction "1_1") (pintype "passive"))
    )
    (net (code "191") (name "Net-(E18B-I1)") (class "Default")
      (node (ref "D15") (pin "A") (pinfunction "A_A") (pintype "passive"))
      (node (ref "D27") (pin "A") (pinfunction "A_A") (pintype "passive"))
      (node (ref "D39") (pin "A") (pinfunction "A_A") (pintype "passive"))
      (node (ref "E18") (pin "7") (pinfunction "I1_7") (pintype "input"))
      (node (ref "R10") (pin "1") (pinfunction "1_1") (pintype "passive"))
    )
    (net (code "192") (name "Net-(E18B-O)") (class "Default")
      (node (ref "E18") (pin "2") (pinfunction "O_2") (pintype "output"))
      (node (ref "R53") (pin "1") (pinfunction "1_1") (pintype "passive"))
      (node (ref "R54") (pin "1") (pinfunction "1_1") (pintype "passive"))
    )
    (net (code "193") (name "Net-(E18C-I0)") (class "Default")
      (node (ref "D13") (pin "A") (pinfunction "A_A") (pintype "passive"))
      (node (ref "D25") (pin "A") (pinfunction "A_A") (pintype "passive"))
      (node (ref "D37") (pin "A") (pinfunction "A_A") (pintype "passive"))
      (node (ref "E18") (pin "9") (pinfunction "I0_9") (pintype "input"))
      (node (ref "R12") (pin "1") (pinfunction "1_1") (pintype "passive"))
    )
    (net (code "194") (name "Net-(E18C-O)") (class "Default")
      (node (ref "E18") (pin "14") (pinfunction "O_14") (pintype "output"))
      (node (ref "R59") (pin "1") (pinfunction "1_1") (pintype "passive"))
      (node (ref "R60") (pin "1") (pinfunction "1_1") (pintype "passive"))
    )
    (net (code "195") (name "Net-(E18D-I0)") (class "Default")
      (node (ref "D14") (pin "A") (pinfunction "A_A") (pintype "passive"))
      (node (ref "D26") (pin "A") (pinfunction "A_A") (pintype "passive"))
      (node (ref "D38") (pin "A") (pinfunction "A_A") (pintype "passive"))
      (node (ref "E18") (pin "11") (pinfunction "I0_11") (pintype "input"))
      (node (ref "R11") (pin "1") (pinfunction "1_1") (pintype "passive"))
    )
    (net (code "196") (name "Net-(E18D-O)") (class "Default")
      (node (ref "E18") (pin "13") (pinfunction "O_13") (pintype "output"))
      (node (ref "R56") (pin "1") (pinfunction "1_1") (pintype "passive"))
      (node (ref "R57") (pin "1") (pinfunction "1_1") (pintype "passive"))
    )
    (net (code "197") (name "Net-(E19A-O)") (class "Default")
      (node (ref "E19") (pin "2") (pinfunction "O_2") (pintype "open_collector"))
      (node (ref "I24") (pin "A") (pinfunction "A_A") (pintype "passive"))
      (node (ref "R135") (pin "2") (pinfunction "2_2") (pintype "passive"))
    )
    (net (code "198") (name "Net-(E19B-I)") (class "Default")
      (node (ref "E19") (pin "3") (pinfunction "I_3") (pintype "input"))
      (node (ref "E20") (pin "14") (pinfunction "O_14") (pintype "output"))
    )
    (net (code "199") (name "Net-(E19B-O)") (class "Default")
      (node (ref "E19") (pin "4") (pinfunction "O_4") (pintype "open_collector"))
      (node (ref "I23") (pin "A") (pinfunction "A_A") (pintype "passive"))
      (node (ref "R134") (pin "2") (pinfunction "2_2") (pintype "passive"))
    )
    (net (code "200") (name "Net-(E19C-I)") (class "Default")
      (node (ref "E19") (pin "5") (pinfunction "I_5") (pintype "input"))
      (node (ref "E20") (pin "13") (pinfunction "O_13") (pintype "output"))
    )
    (net (code "201") (name "Net-(E19C-O)") (class "Default")
      (node (ref "E19") (pin "6") (pinfunction "O_6") (pintype "open_collector"))
      (node (ref "I22") (pin "A") (pinfunction "A_A") (pintype "passive"))
      (node (ref "R133") (pin "2") (pinfunction "2_2") (pintype "passive"))
    )
    (net (code "202") (name "Net-(E19D-O)") (class "Default")
      (node (ref "E19") (pin "8") (pinfunction "O_8") (pintype "open_collector"))
      (node (ref "I27") (pin "A") (pinfunction "A_A") (pintype "passive"))
      (node (ref "R138") (pin "2") (pinfunction "2_2") (pintype "passive"))
    )
    (net (code "203") (name "Net-(E19E-O)") (class "Default")
      (node (ref "E19") (pin "10") (pinfunction "O_10") (pintype "open_collector"))
      (node (ref "I26") (pin "A") (pinfunction "A_A") (pintype "passive"))
      (node (ref "R137") (pin "2") (pinfunction "2_2") (pintype "passive"))
    )
    (net (code "204") (name "Net-(E19F-O)") (class "Default")
      (node (ref "E19") (pin "12") (pinfunction "O_12") (pintype "open_collector"))
      (node (ref "I25") (pin "A") (pinfunction "A_A") (pintype "passive"))
      (node (ref "R136") (pin "2") (pinfunction "2_2") (pintype "passive"))
    )
    (net (code "205") (name "Net-(E20A-O)") (class "Default")
      (node (ref "E20") (pin "3") (pinfunction "O_3") (pintype "output"))
      (node (ref "E23") (pin "11") (pinfunction "I_11") (pintype "input"))
    )
    (net (code "206") (name "Net-(E20B-O)") (class "Default")
      (node (ref "E20") (pin "2") (pinfunction "O_2") (pintype "output"))
      (node (ref "E23") (pin "13") (pinfunction "I_13") (pintype "input"))
    )
    (net (code "207") (name "Net-(E21A-I1)") (class "Default")
      (node (ref "D98") (pin "C") (pinfunction "C_C") (pintype "passive"))
      (node (ref "E21") (pin "3") (pinfunction "I1_3") (pintype "input"))
      (node (ref "R111") (pin "2") (pinfunction "2_2") (pintype "passive"))
    )
    (net (code "208") (name "Net-(E21B-I1)") (class "Default")
      (node (ref "D99") (pin "C") (pinfunction "C_C") (pintype "passive"))
      (node (ref "E21") (pin "6") (pinfunction "I1_6") (pintype "input"))
      (node (ref "R113") (pin "2") (pinfunction "2_2") (pintype "passive"))
    )
    (net (code "209") (name "Net-(E21C-I0)") (class "Default")
      (node (ref "D100") (pin "C") (pinfunction "C_C") (pintype "passive"))
      (node (ref "E21") (pin "8") (pinfunction "I0_8") (pintype "input"))
      (node (ref "R115") (pin "2") (pinfunction "2_2") (pintype "passive"))
    )
    (net (code "210") (name "Net-(E21D-I0)") (class "Default")
      (node (ref "D101") (pin "C") (pinfunction "C_C") (pintype "passive"))
      (node (ref "E21") (pin "11") (pinfunction "I0_11") (pintype "input"))
      (node (ref "R117") (pin "2") (pinfunction "2_2") (pintype "passive"))
    )
    (net (code "211") (name "Net-(E22A-I1)") (class "Default")
      (node (ref "D20") (pin "A") (pinfunction "A_A") (pintype "passive"))
      (node (ref "D32") (pin "A") (pinfunction "A_A") (pintype "passive"))
      (node (ref "D44") (pin "A") (pinfunction "A_A") (pintype "passive"))
      (node (ref "E22") (pin "5") (pinfunction "I1_5") (pintype "input"))
      (node (ref "R5") (pin "1") (pinfunction "1_1") (pintype "passive"))
    )
    (net (code "212") (name "Net-(E22A-O)") (class "Default")
      (node (ref "E22") (pin "3") (pinfunction "O_3") (pintype "output"))
      (node (ref "R38") (pin "1") (pinfunction "1_1") (pintype "passive"))
      (node (ref "R39") (pin "1") (pinfunction "1_1") (pintype "passive"))
    )
    (net (code "213") (name "Net-(E22B-I1)") (class "Default")
      (node (ref "D19") (pin "A") (pinfunction "A_A") (pintype "passive"))
      (node (ref "D31") (pin "A") (pinfunction "A_A") (pintype "passive"))
      (node (ref "D43") (pin "A") (pinfunction "A_A") (pintype "passive"))
      (node (ref "E22") (pin "7") (pinfunction "I1_7") (pintype "input"))
      (node (ref "R6") (pin "1") (pinfunction "1_1") (pintype "passive"))
    )
    (net (code "214") (name "Net-(E22B-O)") (class "Default")
      (node (ref "E22") (pin "2") (pinfunction "O_2") (pintype "output"))
      (node (ref "R41") (pin "1") (pinfunction "1_1") (pintype "passive"))
      (node (ref "R42") (pin "1") (pinfunction "1_1") (pintype "passive"))
    )
    (net (code "215") (name "Net-(E22C-I0)") (class "Default")
      (node (ref "D17") (pin "A") (pinfunction "A_A") (pintype "passive"))
      (node (ref "D29") (pin "A") (pinfunction "A_A") (pintype "passive"))
      (node (ref "D41") (pin "A") (pinfunction "A_A") (pintype "passive"))
      (node (ref "E22") (pin "9") (pinfunction "I0_9") (pintype "input"))
      (node (ref "R8") (pin "1") (pinfunction "1_1") (pintype "passive"))
    )
    (net (code "216") (name "Net-(E22C-O)") (class "Default")
      (node (ref "E22") (pin "14") (pinfunction "O_14") (pintype "output"))
      (node (ref "R47") (pin "1") (pinfunction "1_1") (pintype "passive"))
      (node (ref "R48") (pin "1") (pinfunction "1_1") (pintype "passive"))
    )
    (net (code "217") (name "Net-(E22D-I0)") (class "Default")
      (node (ref "D18") (pin "A") (pinfunction "A_A") (pintype "passive"))
      (node (ref "D30") (pin "A") (pinfunction "A_A") (pintype "passive"))
      (node (ref "D42") (pin "A") (pinfunction "A_A") (pintype "passive"))
      (node (ref "E22") (pin "11") (pinfunction "I0_11") (pintype "input"))
      (node (ref "R7") (pin "1") (pinfunction "1_1") (pintype "passive"))
    )
    (net (code "218") (name "Net-(E22D-O)") (class "Default")
      (node (ref "E22") (pin "13") (pinfunction "O_13") (pintype "output"))
      (node (ref "R44") (pin "1") (pinfunction "1_1") (pintype "passive"))
      (node (ref "R45") (pin "1") (pinfunction "1_1") (pintype "passive"))
    )
    (net (code "219") (name "Net-(E23A-I)") (class "Default")
      (node (ref "E23") (pin "1") (pinfunction "I_1") (pintype "input"))
      (node (ref "E24") (pin "14") (pinfunction "O_14") (pintype "output"))
    )
    (net (code "220") (name "Net-(E23A-O)") (class "Default")
      (node (ref "E23") (pin "2") (pinfunction "O_2") (pintype "open_collector"))
      (node (ref "I18") (pin "A") (pinfunction "A_A") (pintype "passive"))
      (node (ref "R129") (pin "2") (pinfunction "2_2") (pintype "passive"))
    )
    (net (code "221") (name "Net-(E23B-I)") (class "Default")
      (node (ref "E23") (pin "3") (pinfunction "I_3") (pintype "input"))
      (node (ref "E24") (pin "13") (pinfunction "O_13") (pintype "output"))
    )
    (net (code "222") (name "Net-(E23B-O)") (class "Default")
      (node (ref "E23") (pin "4") (pinfunction "O_4") (pintype "open_collector"))
      (node (ref "I19") (pin "A") (pinfunction "A_A") (pintype "passive"))
      (node (ref "R130") (pin "2") (pinfunction "2_2") (pintype "passive"))
    )
    (net (code "223") (name "Net-(E23E-O)") (class "Default")
      (node (ref "E23") (pin "10") (pinfunction "O_10") (pintype "open_collector"))
      (node (ref "I21") (pin "A") (pinfunction "A_A") (pintype "passive"))
      (node (ref "R132") (pin "2") (pinfunction "2_2") (pintype "passive"))
    )
    (net (code "224") (name "Net-(E23F-O)") (class "Default")
      (node (ref "E23") (pin "12") (pinfunction "O_12") (pintype "open_collector"))
      (node (ref "I20") (pin "A") (pinfunction "A_A") (pintype "passive"))
      (node (ref "R131") (pin "2") (pinfunction "2_2") (pintype "passive"))
    )
    (net (code "225") (name "Net-(E24A-O)") (class "Default")
      (node (ref "E24") (pin "3") (pinfunction "O_3") (pintype "output"))
      (node (ref "E27") (pin "11") (pinfunction "I_11") (pintype "input"))
    )
    (net (code "226") (name "Net-(E24B-O)") (class "Default")
      (node (ref "E24") (pin "2") (pinfunction "O_2") (pintype "output"))
      (node (ref "E27") (pin "13") (pinfunction "I_13") (pintype "input"))
    )
    (net (code "227") (name "Net-(E25A-I1)") (class "Default")
      (node (ref "D94") (pin "C") (pinfunction "C_C") (pintype "passive"))
      (node (ref "E25") (pin "3") (pinfunction "I1_3") (pintype "input"))
      (node (ref "R103") (pin "2") (pinfunction "2_2") (pintype "passive"))
    )
    (net (code "228") (name "Net-(E25B-I1)") (class "Default")
      (node (ref "D95") (pin "C") (pinfunction "C_C") (pintype "passive"))
      (node (ref "E25") (pin "6") (pinfunction "I1_6") (pintype "input"))
      (node (ref "R105") (pin "2") (pinfunction "2_2") (pintype "passive"))
    )
    (net (code "229") (name "Net-(E25C-I0)") (class "Default")
      (node (ref "D96") (pin "C") (pinfunction "C_C") (pintype "passive"))
      (node (ref "E25") (pin "8") (pinfunction "I0_8") (pintype "input"))
      (node (ref "R107") (pin "2") (pinfunction "2_2") (pintype "passive"))
    )
    (net (code "230") (name "Net-(E25D-I1)") (class "Default")
      (node (ref "D97") (pin "C") (pinfunction "C_C") (pintype "passive"))
      (node (ref "E25") (pin "12") (pinfunction "I1_12") (pintype "input"))
      (node (ref "R109") (pin "2") (pinfunction "2_2") (pintype "passive"))
    )
    (net (code "231") (name "Net-(E26A-I1)") (class "Default")
      (node (ref "D24") (pin "A") (pinfunction "A_A") (pintype "passive"))
      (node (ref "D36") (pin "A") (pinfunction "A_A") (pintype "passive"))
      (node (ref "D48") (pin "A") (pinfunction "A_A") (pintype "passive"))
      (node (ref "E26") (pin "5") (pinfunction "I1_5") (pintype "input"))
      (node (ref "R1") (pin "1") (pinfunction "1_1") (pintype "passive"))
    )
    (net (code "232") (name "Net-(E26A-O)") (class "Default")
      (node (ref "E26") (pin "3") (pinfunction "O_3") (pintype "output"))
      (node (ref "R26") (pin "1") (pinfunction "1_1") (pintype "passive"))
      (node (ref "R27") (pin "1") (pinfunction "1_1") (pintype "passive"))
    )
    (net (code "233") (name "Net-(E26B-I1)") (class "Default")
      (node (ref "D23") (pin "A") (pinfunction "A_A") (pintype "passive"))
      (node (ref "D35") (pin "A") (pinfunction "A_A") (pintype "passive"))
      (node (ref "D47") (pin "A") (pinfunction "A_A") (pintype "passive"))
      (node (ref "E26") (pin "7") (pinfunction "I1_7") (pintype "input"))
      (node (ref "R2") (pin "1") (pinfunction "1_1") (pintype "passive"))
    )
    (net (code "234") (name "Net-(E26B-O)") (class "Default")
      (node (ref "E26") (pin "2") (pinfunction "O_2") (pintype "output"))
      (node (ref "R29") (pin "1") (pinfunction "1_1") (pintype "passive"))
      (node (ref "R30") (pin "1") (pinfunction "1_1") (pintype "passive"))
    )
    (net (code "235") (name "Net-(E26C-I0)") (class "Default")
      (node (ref "D21") (pin "A") (pinfunction "A_A") (pintype "passive"))
      (node (ref "D33") (pin "A") (pinfunction "A_A") (pintype "passive"))
      (node (ref "D45") (pin "A") (pinfunction "A_A") (pintype "passive"))
      (node (ref "E26") (pin "9") (pinfunction "I0_9") (pintype "input"))
      (node (ref "R4") (pin "1") (pinfunction "1_1") (pintype "passive"))
    )
    (net (code "236") (name "Net-(E26C-O)") (class "Default")
      (node (ref "E26") (pin "14") (pinfunction "O_14") (pintype "output"))
      (node (ref "R35") (pin "1") (pinfunction "1_1") (pintype "passive"))
      (node (ref "R36") (pin "1") (pinfunction "1_1") (pintype "passive"))
    )
    (net (code "237") (name "Net-(E26D-I0)") (class "Default")
      (node (ref "D22") (pin "A") (pinfunction "A_A") (pintype "passive"))
      (node (ref "D34") (pin "A") (pinfunction "A_A") (pintype "passive"))
      (node (ref "D46") (pin "A") (pinfunction "A_A") (pintype "passive"))
      (node (ref "E26") (pin "11") (pinfunction "I0_11") (pintype "input"))
      (node (ref "R3") (pin "1") (pinfunction "1_1") (pintype "passive"))
    )
    (net (code "238") (name "Net-(E26D-O)") (class "Default")
      (node (ref "E26") (pin "13") (pinfunction "O_13") (pintype "output"))
      (node (ref "R32") (pin "1") (pinfunction "1_1") (pintype "passive"))
      (node (ref "R33") (pin "1") (pinfunction "1_1") (pintype "passive"))
    )
    (net (code "239") (name "Net-(E27A-I)") (class "Default")
      (node (ref "E27") (pin "1") (pinfunction "I_1") (pintype "input"))
      (node (ref "E28") (pin "3") (pinfunction "O_3") (pintype "output"))
    )
    (net (code "240") (name "Net-(E27A-O)") (class "Default")
      (node (ref "E27") (pin "2") (pinfunction "O_2") (pintype "open_collector"))
      (node (ref "I15") (pin "A") (pinfunction "A_A") (pintype "passive"))
      (node (ref "R141") (pin "2") (pinfunction "2_2") (pintype "passive"))
    )
    (net (code "241") (name "Net-(E27B-I)") (class "Default")
      (node (ref "E27") (pin "3") (pinfunction "I_3") (pintype "input"))
      (node (ref "E28") (pin "14") (pinfunction "O_14") (pintype "output"))
    )
    (net (code "242") (name "Net-(E27B-O)") (class "Default")
      (node (ref "E27") (pin "4") (pinfunction "O_4") (pintype "open_collector"))
      (node (ref "I14") (pin "A") (pinfunction "A_A") (pintype "passive"))
      (node (ref "R140") (pin "2") (pinfunction "2_2") (pintype "passive"))
    )
    (net (code "243") (name "Net-(E27C-I)") (class "Default")
      (node (ref "E27") (pin "5") (pinfunction "I_5") (pintype "input"))
      (node (ref "E28") (pin "13") (pinfunction "O_13") (pintype "output"))
    )
    (net (code "244") (name "Net-(E27C-O)") (class "Default")
      (node (ref "E27") (pin "6") (pinfunction "O_6") (pintype "open_collector"))
      (node (ref "I13") (pin "A") (pinfunction "A_A") (pintype "passive"))
      (node (ref "R139") (pin "2") (pinfunction "2_2") (pintype "passive"))
    )
    (net (code "245") (name "Net-(E27E-O)") (class "Default")
      (node (ref "E27") (pin "10") (pinfunction "O_10") (pintype "open_collector"))
      (node (ref "I17") (pin "A") (pinfunction "A_A") (pintype "passive"))
      (node (ref "R128") (pin "2") (pinfunction "2_2") (pintype "passive"))
    )
    (net (code "246") (name "Net-(E27F-O)") (class "Default")
      (node (ref "E27") (pin "12") (pinfunction "O_12") (pintype "open_collector"))
      (node (ref "I16") (pin "A") (pinfunction "A_A") (pintype "passive"))
      (node (ref "R127") (pin "2") (pinfunction "2_2") (pintype "passive"))
    )
    (net (code "247") (name "Net-(Q1-B)") (class "Default")
      (node (ref "C1") (pin "2") (pinfunction "2_2") (pintype "passive"))
      (node (ref "D1") (pin "C") (pinfunction "C_C") (pintype "passive"))
      (node (ref "Q1") (pin "2") (pinfunction "B_2") (pintype "passive"))
      (node (ref "R27") (pin "2") (pinfunction "2_2") (pintype "passive"))
    )
    (net (code "248") (name "Net-(Q1-C)") (class "Default")
      (node (ref "C1") (pin "1") (pinfunction "1_1") (pintype "passive"))
      (node (ref "I1") (pin "A") (pinfunction "A_A") (pintype "passive"))
      (node (ref "Q1") (pin "3") (pinfunction "C_3") (pintype "passive"))
      (node (ref "R25") (pin "2") (pinfunction "2_2") (pintype "passive"))
    )
    (net (code "249") (name "Net-(Q2-B)") (class "Default")
      (node (ref "C2") (pin "2") (pinfunction "2_2") (pintype "passive"))
      (node (ref "D2") (pin "C") (pinfunction "C_C") (pintype "passive"))
      (node (ref "Q2") (pin "2") (pinfunction "B_2") (pintype "passive"))
      (node (ref "R30") (pin "2") (pinfunction "2_2") (pintype "passive"))
    )
    (net (code "250") (name "Net-(Q2-C)") (class "Default")
      (node (ref "C2") (pin "1") (pinfunction "1_1") (pintype "passive"))
      (node (ref "I2") (pin "A") (pinfunction "A_A") (pintype "passive"))
      (node (ref "Q2") (pin "3") (pinfunction "C_3") (pintype "passive"))
      (node (ref "R28") (pin "2") (pinfunction "2_2") (pintype "passive"))
    )
    (net (code "251") (name "Net-(Q3-B)") (class "Default")
      (node (ref "C3") (pin "2") (pinfunction "2_2") (pintype "passive"))
      (node (ref "D3") (pin "C") (pinfunction "C_C") (pintype "passive"))
      (node (ref "Q3") (pin "2") (pinfunction "B_2") (pintype "passive"))
      (node (ref "R33") (pin "2") (pinfunction "2_2") (pintype "passive"))
    )
    (net (code "252") (name "Net-(Q3-C)") (class "Default")
      (node (ref "C3") (pin "1") (pinfunction "1_1") (pintype "passive"))
      (node (ref "I3") (pin "A") (pinfunction "A_A") (pintype "passive"))
      (node (ref "Q3") (pin "3") (pinfunction "C_3") (pintype "passive"))
      (node (ref "R31") (pin "2") (pinfunction "2_2") (pintype "passive"))
    )
    (net (code "253") (name "Net-(Q4-B)") (class "Default")
      (node (ref "C4") (pin "2") (pinfunction "2_2") (pintype "passive"))
      (node (ref "D4") (pin "C") (pinfunction "C_C") (pintype "passive"))
      (node (ref "Q4") (pin "2") (pinfunction "B_2") (pintype "passive"))
      (node (ref "R36") (pin "2") (pinfunction "2_2") (pintype "passive"))
    )
    (net (code "254") (name "Net-(Q4-C)") (class "Default")
      (node (ref "C4") (pin "1") (pinfunction "1_1") (pintype "passive"))
      (node (ref "I4") (pin "A") (pinfunction "A_A") (pintype "passive"))
      (node (ref "Q4") (pin "3") (pinfunction "C_3") (pintype "passive"))
      (node (ref "R34") (pin "2") (pinfunction "2_2") (pintype "passive"))
    )
    (net (code "255") (name "Net-(Q5-B)") (class "Default")
      (node (ref "C5") (pin "2") (pinfunction "2_2") (pintype "passive"))
      (node (ref "D5") (pin "C") (pinfunction "C_C") (pintype "passive"))
      (node (ref "Q5") (pin "2") (pinfunction "B_2") (pintype "passive"))
      (node (ref "R39") (pin "2") (pinfunction "2_2") (pintype "passive"))
    )
    (net (code "256") (name "Net-(Q5-C)") (class "Default")
      (node (ref "C5") (pin "1") (pinfunction "1_1") (pintype "passive"))
      (node (ref "I5") (pin "A") (pinfunction "A_A") (pintype "passive"))
      (node (ref "Q5") (pin "3") (pinfunction "C_3") (pintype "passive"))
      (node (ref "R37") (pin "2") (pinfunction "2_2") (pintype "passive"))
    )
    (net (code "257") (name "Net-(Q6-B)") (class "Default")
      (node (ref "C6") (pin "2") (pinfunction "2_2") (pintype "passive"))
      (node (ref "D6") (pin "C") (pinfunction "C_C") (pintype "passive"))
      (node (ref "Q6") (pin "2") (pinfunction "B_2") (pintype "passive"))
      (node (ref "R42") (pin "2") (pinfunction "2_2") (pintype "passive"))
    )
    (net (code "258") (name "Net-(Q6-C)") (class "Default")
      (node (ref "C6") (pin "1") (pinfunction "1_1") (pintype "passive"))
      (node (ref "I6") (pin "A") (pinfunction "A_A") (pintype "passive"))
      (node (ref "Q6") (pin "3") (pinfunction "C_3") (pintype "passive"))
      (node (ref "R40") (pin "2") (pinfunction "2_2") (pintype "passive"))
    )
    (net (code "259") (name "Net-(Q7-B)") (class "Default")
      (node (ref "C7") (pin "2") (pinfunction "2_2") (pintype "passive"))
      (node (ref "D7") (pin "C") (pinfunction "C_C") (pintype "passive"))
      (node (ref "Q7") (pin "2") (pinfunction "B_2") (pintype "passive"))
      (node (ref "R45") (pin "2") (pinfunction "2_2") (pintype "passive"))
    )
    (net (code "260") (name "Net-(Q7-C)") (class "Default")
      (node (ref "C7") (pin "1") (pinfunction "1_1") (pintype "passive"))
      (node (ref "I7") (pin "A") (pinfunction "A_A") (pintype "passive"))
      (node (ref "Q7") (pin "3") (pinfunction "C_3") (pintype "passive"))
      (node (ref "R43") (pin "2") (pinfunction "2_2") (pintype "passive"))
    )
    (net (code "261") (name "Net-(Q8-B)") (class "Default")
      (node (ref "C8") (pin "2") (pinfunction "2_2") (pintype "passive"))
      (node (ref "D8") (pin "C") (pinfunction "C_C") (pintype "passive"))
      (node (ref "Q8") (pin "2") (pinfunction "B_2") (pintype "passive"))
      (node (ref "R48") (pin "2") (pinfunction "2_2") (pintype "passive"))
    )
    (net (code "262") (name "Net-(Q8-C)") (class "Default")
      (node (ref "C8") (pin "1") (pinfunction "1_1") (pintype "passive"))
      (node (ref "I8") (pin "A") (pinfunction "A_A") (pintype "passive"))
      (node (ref "Q8") (pin "3") (pinfunction "C_3") (pintype "passive"))
      (node (ref "R46") (pin "2") (pinfunction "2_2") (pintype "passive"))
    )
    (net (code "263") (name "Net-(Q9-B)") (class "Default")
      (node (ref "C9") (pin "2") (pinfunction "2_2") (pintype "passive"))
      (node (ref "D9") (pin "C") (pinfunction "C_C") (pintype "passive"))
      (node (ref "Q9") (pin "2") (pinfunction "B_2") (pintype "passive"))
      (node (ref "R51") (pin "2") (pinfunction "2_2") (pintype "passive"))
    )
    (net (code "264") (name "Net-(Q9-C)") (class "Default")
      (node (ref "C9") (pin "1") (pinfunction "1_1") (pintype "passive"))
      (node (ref "I9") (pin "A") (pinfunction "A_A") (pintype "passive"))
      (node (ref "Q9") (pin "3") (pinfunction "C_3") (pintype "passive"))
      (node (ref "R49") (pin "2") (pinfunction "2_2") (pintype "passive"))
    )
    (net (code "265") (name "Net-(Q10-B)") (class "Default")
      (node (ref "C10") (pin "2") (pinfunction "2_2") (pintype "passive"))
      (node (ref "D10") (pin "C") (pinfunction "C_C") (pintype "passive"))
      (node (ref "Q10") (pin "2") (pinfunction "B_2") (pintype "passive"))
      (node (ref "R54") (pin "2") (pinfunction "2_2") (pintype "passive"))
    )
    (net (code "266") (name "Net-(Q10-C)") (class "Default")
      (node (ref "C10") (pin "1") (pinfunction "1_1") (pintype "passive"))
      (node (ref "I10") (pin "A") (pinfunction "A_A") (pintype "passive"))
      (node (ref "Q10") (pin "3") (pinfunction "C_3") (pintype "passive"))
      (node (ref "R52") (pin "2") (pinfunction "2_2") (pintype "passive"))
    )
    (net (code "267") (name "Net-(Q11-B)") (class "Default")
      (node (ref "C11") (pin "2") (pinfunction "2_2") (pintype "passive"))
      (node (ref "D11") (pin "C") (pinfunction "C_C") (pintype "passive"))
      (node (ref "Q11") (pin "2") (pinfunction "B_2") (pintype "passive"))
      (node (ref "R57") (pin "2") (pinfunction "2_2") (pintype "passive"))
    )
    (net (code "268") (name "Net-(Q11-C)") (class "Default")
      (node (ref "C11") (pin "1") (pinfunction "1_1") (pintype "passive"))
      (node (ref "I11") (pin "A") (pinfunction "A_A") (pintype "passive"))
      (node (ref "Q11") (pin "3") (pinfunction "C_3") (pintype "passive"))
      (node (ref "R55") (pin "2") (pinfunction "2_2") (pintype "passive"))
    )
    (net (code "269") (name "Net-(Q12-B)") (class "Default")
      (node (ref "C12") (pin "2") (pinfunction "2_2") (pintype "passive"))
      (node (ref "D12") (pin "C") (pinfunction "C_C") (pintype "passive"))
      (node (ref "Q12") (pin "2") (pinfunction "B_2") (pintype "passive"))
      (node (ref "R60") (pin "2") (pinfunction "2_2") (pintype "passive"))
    )
    (net (code "270") (name "Net-(Q12-C)") (class "Default")
      (node (ref "C12") (pin "1") (pinfunction "1_1") (pintype "passive"))
      (node (ref "I12") (pin "A") (pinfunction "A_A") (pintype "passive"))
      (node (ref "Q12") (pin "3") (pinfunction "C_3") (pintype "passive"))
      (node (ref "R58") (pin "2") (pinfunction "2_2") (pintype "passive"))
    )
    (net (code "271") (name "Net-(Q13-B)") (class "Default")
      (node (ref "Q13") (pin "2") (pinfunction "B_2") (pintype "passive"))
      (node (ref "R154") (pin "2") (pinfunction "2_2") (pintype "passive"))
    )
    (net (code "272") (name "Net-(Q13-E)") (class "Default")
      (node (ref "Q13") (pin "1") (pinfunction "E_1") (pintype "passive"))
      (node (ref "Q14") (pin "2") (pinfunction "B_2") (pintype "passive"))
      (node (ref "R155") (pin "1") (pinfunction "1_1") (pintype "passive"))
    )
    (net (code "273") (name "Net-(Q14-C)") (class "Default")
      (node (ref "Q14") (pin "3") (pinfunction "C_3") (pintype "passive"))
      (node (ref "Q15") (pin "2") (pinfunction "B_2") (pintype "passive"))
      (node (ref "R157") (pin "2") (pinfunction "2_2") (pintype "passive"))
    )
    (net (code "274") (name "Net-(Q14-E)") (class "Default")
      (node (ref "D116") (pin "A") (pinfunction "A_A") (pintype "passive"))
      (node (ref "Q14") (pin "1") (pinfunction "E_1") (pintype "passive"))
      (node (ref "Q15") (pin "1") (pinfunction "E_1") (pintype "passive"))
      (node (ref "R156") (pin "1") (pinfunction "1_1") (pintype "passive"))
    )
    (net (code "275") (name "Net-(Q15-C)") (class "Default")
      (node (ref "C14") (pin "2") (pinfunction "2_2") (pintype "passive"))
      (node (ref "D118") (pin "C") (pinfunction "C_C") (pintype "passive"))
      (node (ref "D120") (pin "A") (pinfunction "A_A") (pintype "passive"))
      (node (ref "Q15") (pin "3") (pinfunction "C_3") (pintype "passive"))
      (node (ref "R158") (pin "2") (pinfunction "2_2") (pintype "passive"))
    )
    (net (code "276") (name "Net-(Q16-B)") (class "Default")
      (node (ref "Q16") (pin "2") (pinfunction "B_2") (pintype "passive"))
      (node (ref "Q19") (pin "3") (pinfunction "C_3") (pintype "passive"))
      (node (ref "R167") (pin "1") (pinfunction "1_1") (pintype "passive"))
    )
    (net (code "277") (name "Net-(Q16-C)") (class "Default")
      (node (ref "I28") (pin "B") (pinfunction "B_B") (pintype "passive"))
      (node (ref "Q16") (pin "3") (pinfunction "C_3") (pintype "passive"))
      (node (ref "R168") (pin "1") (pinfunction "1_1") (pintype "passive"))
    )
    (net (code "278") (name "Net-(Q16-E)") (class "Default")
      (node (ref "D122") (pin "C") (pinfunction "C_C") (pintype "passive"))
      (node (ref "Q16") (pin "1") (pinfunction "E_1") (pintype "passive"))
      (node (ref "R168") (pin "2") (pinfunction "2_2") (pintype "passive"))
    )
    (net (code "279") (name "Net-(Q17-B)") (class "Default")
      (node (ref "Q17") (pin "2") (pinfunction "B_2") (pintype "passive"))
      (node (ref "R172") (pin "2") (pinfunction "2_2") (pintype "passive"))
    )
    (net (code "280") (name "Net-(Q17-C)") (class "Default")
      (node (ref "Q17") (pin "3") (pinfunction "C_3") (pintype "passive"))
      (node (ref "R163") (pin "1") (pinfunction "1_1") (pintype "passive"))
    )
    (net (code "281") (name "Net-(Q18-B)") (class "Default")
      (node (ref "Q18") (pin "2") (pinfunction "B_2") (pintype "passive"))
      (node (ref "R174") (pin "2") (pinfunction "2_2") (pintype "passive"))
    )
    (net (code "282") (name "Net-(Q18-C)") (class "Default")
      (node (ref "Q18") (pin "3") (pinfunction "C_3") (pintype "passive"))
      (node (ref "R165") (pin "1") (pinfunction "1_1") (pintype "passive"))
    )
    (net (code "283") (name "Net-(Q19-B)") (class "Default")
      (node (ref "Q19") (pin "2") (pinfunction "B_2") (pintype "passive"))
      (node (ref "R166") (pin "2") (pinfunction "2_2") (pintype "passive"))
    )
    (net (code "284") (name "Net-(R87-Pad1)") (class "Default")
      (node (ref "R87") (pin "1") (pinfunction "1_1") (pintype "passive"))
      (node (ref "R88") (pin "1") (pinfunction "1_1") (pintype "passive"))
      (node (ref "S3") (pin "A1") (pinfunction "A1_A1") (pintype "bidirectional"))
    )
    (net (code "285") (name "Net-(R89-Pad1)") (class "Default")
      (node (ref "R89") (pin "1") (pinfunction "1_1") (pintype "passive"))
      (node (ref "R90") (pin "1") (pinfunction "1_1") (pintype "passive"))
      (node (ref "S4") (pin "A1") (pinfunction "A1_A1") (pintype "bidirectional"))
    )
    (net (code "286") (name "Net-(R91-Pad1)") (class "Default")
      (node (ref "R91") (pin "1") (pinfunction "1_1") (pintype "passive"))
      (node (ref "R92") (pin "1") (pinfunction "1_1") (pintype "passive"))
      (node (ref "S5") (pin "A1") (pinfunction "A1_A1") (pintype "bidirectional"))
    )
    (net (code "287") (name "Net-(R93-Pad1)") (class "Default")
      (node (ref "R93") (pin "1") (pinfunction "1_1") (pintype "passive"))
      (node (ref "R94") (pin "1") (pinfunction "1_1") (pintype "passive"))
      (node (ref "S6") (pin "A1") (pinfunction "A1_A1") (pintype "bidirectional"))
    )
    (net (code "288") (name "Net-(R95-Pad1)") (class "Default")
      (node (ref "R95") (pin "1") (pinfunction "1_1") (pintype "passive"))
      (node (ref "R96") (pin "1") (pinfunction "1_1") (pintype "passive"))
      (node (ref "S7") (pin "A2") (pinfunction "A2_A2") (pintype "bidirectional"))
    )
    (net (code "289") (name "Net-(R97-Pad1)") (class "Default")
      (node (ref "R97") (pin "1") (pinfunction "1_1") (pintype "passive"))
      (node (ref "R98") (pin "1") (pinfunction "1_1") (pintype "passive"))
      (node (ref "S8") (pin "A1") (pinfunction "A1_A1") (pintype "bidirectional"))
    )
    (net (code "290") (name "Net-(S2\\-A1)") (class "Default")
      (node (ref "R85") (pin "1") (pinfunction "1_1") (pintype "passive"))
      (node (ref "R86") (pin "1") (pinfunction "1_1") (pintype "passive"))
      (node (ref "S2\\") (pin "L1") (pinfunction "A1_L1") (pintype "bidirectional"))
      (node (ref "S2\\") (pin "R1") (pinfunction "B1_R1") (pintype "bidirectional"))
    )
    (net (code "291") (name "Net-(S9-A1)") (class "Default")
      (node (ref "R100") (pin "1") (pinfunction "1_1") (pintype "passive"))
      (node (ref "R99") (pin "1") (pinfunction "1_1") (pintype "passive"))
      (node (ref "S9") (pin "L1") (pinfunction "A1_L1") (pintype "bidirectional"))
      (node (ref "S9") (pin "R1") (pinfunction "B1_R1") (pintype "bidirectional"))
    )
    (net (code "292") (name "Net-(S10-A1)") (class "Default")
      (node (ref "R101") (pin "1") (pinfunction "1_1") (pintype "passive"))
      (node (ref "R102") (pin "1") (pinfunction "1_1") (pintype "passive"))
      (node (ref "S10") (pin "L1") (pinfunction "A1_L1") (pintype "bidirectional"))
      (node (ref "S10") (pin "R1") (pinfunction "B1_R1") (pintype "bidirectional"))
    )
    (net (code "293") (name "Net-(S11-A1)") (class "Default")
      (node (ref "R103") (pin "1") (pinfunction "1_1") (pintype "passive"))
      (node (ref "R104") (pin "1") (pinfunction "1_1") (pintype "passive"))
      (node (ref "S11") (pin "L1") (pinfunction "A1_L1") (pintype "bidirectional"))
      (node (ref "S11") (pin "R1") (pinfunction "B1_R1") (pintype "bidirectional"))
    )
    (net (code "294") (name "Net-(S12-A1)") (class "Default")
      (node (ref "R105") (pin "1") (pinfunction "1_1") (pintype "passive"))
      (node (ref "R106") (pin "1") (pinfunction "1_1") (pintype "passive"))
      (node (ref "S12") (pin "L1") (pinfunction "A1_L1") (pintype "bidirectional"))
      (node (ref "S12") (pin "R1") (pinfunction "B1_R1") (pintype "bidirectional"))
    )
    (net (code "295") (name "Net-(S13-A1)") (class "Default")
      (node (ref "R107") (pin "1") (pinfunction "1_1") (pintype "passive"))
      (node (ref "R108") (pin "1") (pinfunction "1_1") (pintype "passive"))
      (node (ref "S13") (pin "L1") (pinfunction "A1_L1") (pintype "bidirectional"))
      (node (ref "S13") (pin "R1") (pinfunction "B1_R1") (pintype "bidirectional"))
    )
    (net (code "296") (name "Net-(S14-A1)") (class "Default")
      (node (ref "R109") (pin "1") (pinfunction "1_1") (pintype "passive"))
      (node (ref "R110") (pin "1") (pinfunction "1_1") (pintype "passive"))
      (node (ref "S14") (pin "L1") (pinfunction "A1_L1") (pintype "bidirectional"))
      (node (ref "S14") (pin "R1") (pinfunction "B1_R1") (pintype "bidirectional"))
    )
    (net (code "297") (name "Net-(S15-A1)") (class "Default")
      (node (ref "R111") (pin "1") (pinfunction "1_1") (pintype "passive"))
      (node (ref "R112") (pin "1") (pinfunction "1_1") (pintype "passive"))
      (node (ref "S15") (pin "L1") (pinfunction "A1_L1") (pintype "bidirectional"))
      (node (ref "S15") (pin "R1") (pinfunction "B1_R1") (pintype "bidirectional"))
    )
    (net (code "298") (name "Net-(S16-A1)") (class "Default")
      (node (ref "R113") (pin "1") (pinfunction "1_1") (pintype "passive"))
      (node (ref "R114") (pin "1") (pinfunction "1_1") (pintype "passive"))
      (node (ref "S16") (pin "L1") (pinfunction "A1_L1") (pintype "bidirectional"))
      (node (ref "S16") (pin "R1") (pinfunction "B1_R1") (pintype "bidirectional"))
    )
    (net (code "299") (name "Net-(S17-A1)") (class "Default")
      (node (ref "R115") (pin "1") (pinfunction "1_1") (pintype "passive"))
      (node (ref "R116") (pin "1") (pinfunction "1_1") (pintype "passive"))
      (node (ref "S17") (pin "L1") (pinfunction "A1_L1") (pintype "bidirectional"))
      (node (ref "S17") (pin "R1") (pinfunction "B1_R1") (pintype "bidirectional"))
    )
    (net (code "300") (name "Net-(S18-A1)") (class "Default")
      (node (ref "R117") (pin "1") (pinfunction "1_1") (pintype "passive"))
      (node (ref "R118") (pin "1") (pinfunction "1_1") (pintype "passive"))
      (node (ref "S18") (pin "L1") (pinfunction "A1_L1") (pintype "bidirectional"))
      (node (ref "S18") (pin "R1") (pinfunction "B1_R1") (pintype "bidirectional"))
    )
    (net (code "301") (name "Net-(S19-A1)") (class "Default")
      (node (ref "R119") (pin "1") (pinfunction "1_1") (pintype "passive"))
      (node (ref "R120") (pin "1") (pinfunction "1_1") (pintype "passive"))
      (node (ref "S19") (pin "L1") (pinfunction "A1_L1") (pintype "bidirectional"))
      (node (ref "S19") (pin "R1") (pinfunction "B1_R1") (pintype "bidirectional"))
    )
    (net (code "302") (name "Net-(S20-A1)") (class "Default")
      (node (ref "R121") (pin "1") (pinfunction "1_1") (pintype "passive"))
      (node (ref "R122") (pin "1") (pinfunction "1_1") (pintype "passive"))
      (node (ref "S20") (pin "L1") (pinfunction "A1_L1") (pintype "bidirectional"))
      (node (ref "S20") (pin "R1") (pinfunction "B1_R1") (pintype "bidirectional"))
    )
    (net (code "303") (name "Net-(S21-A1)") (class "Default")
      (node (ref "R123") (pin "1") (pinfunction "1_1") (pintype "passive"))
      (node (ref "R124") (pin "1") (pinfunction "1_1") (pintype "passive"))
      (node (ref "S21") (pin "L1") (pinfunction "A1_L1") (pintype "bidirectional"))
      (node (ref "S21") (pin "R1") (pinfunction "B1_R1") (pintype "bidirectional"))
    )
    (net (code "304") (name "Net-(S22-A1)") (class "Default")
      (node (ref "R125") (pin "1") (pinfunction "1_1") (pintype "passive"))
      (node (ref "R126") (pin "1") (pinfunction "1_1") (pintype "passive"))
      (node (ref "S22") (pin "L1") (pinfunction "A1_L1") (pintype "bidirectional"))
      (node (ref "S22") (pin "R1") (pinfunction "B1_R1") (pintype "bidirectional"))
    )
    (net (code "305") (name "PAN_LOCK") (class "Default")
      (node (ref "BLUE") (pin "1") (pinfunction "1_1") (pintype "passive"))
      (node (ref "S10") (pin "L2") (pinfunction "A2_L2") (pintype "bidirectional"))
      (node (ref "S10") (pin "R2") (pinfunction "B2_R2") (pintype "bidirectional"))
      (node (ref "S2\\") (pin "L2") (pinfunction "A2_L2") (pintype "bidirectional"))
      (node (ref "S2\\") (pin "R2") (pinfunction "B2_R2") (pintype "bidirectional"))
      (node (ref "S3") (pin "A2") (pinfunction "A2_A2") (pintype "bidirectional"))
      (node (ref "S4") (pin "A2") (pinfunction "A2_A2") (pintype "bidirectional"))
      (node (ref "S5") (pin "A2") (pinfunction "A2_A2") (pintype "bidirectional"))
      (node (ref "S6") (pin "A2") (pinfunction "A2_A2") (pintype "bidirectional"))
      (node (ref "S7") (pin "A1") (pinfunction "A1_A1") (pintype "bidirectional"))
      (node (ref "S8") (pin "A2") (pinfunction "A2_A2") (pintype "bidirectional"))
      (node (ref "S9") (pin "L2") (pinfunction "A2_L2") (pintype "bidirectional"))
      (node (ref "S9") (pin "R2") (pinfunction "B2_R2") (pintype "bidirectional"))
    )
    (net (code "306") (name "PULSE_LA") (class "Default")
      (node (ref "Q17") (pin "1") (pinfunction "E_1") (pintype "passive"))
      (node (ref "U$2") (pin "DR2") (pinfunction "1_DR2") (pintype "bidirectional"))
    )
    (net (code "307") (name "SSTP") (class "Default")
      (node (ref "D92") (pin "C") (pinfunction "C_C") (pintype "passive"))
      (node (ref "E6") (pin "5") (pinfunction "I1_5") (pintype "input"))
      (node (ref "R99") (pin "2") (pinfunction "2_2") (pintype "passive"))
    )
    (net (code "308") (name "STATE_EN") (class "Default")
      (node (ref "R143") (pin "1") (pinfunction "1_1") (pintype "passive"))
      (node (ref "R61") (pin "2") (pinfunction "2_2") (pintype "passive"))
      (node (ref "R63") (pin "2") (pinfunction "2_2") (pintype "passive"))
      (node (ref "R65") (pin "2") (pinfunction "2_2") (pintype "passive"))
      (node (ref "R67") (pin "2") (pinfunction "2_2") (pintype "passive"))
      (node (ref "R69") (pin "2") (pinfunction "2_2") (pintype "passive"))
      (node (ref "R71") (pin "2") (pinfunction "2_2") (pintype "passive"))
      (node (ref "R73") (pin "2") (pinfunction "2_2") (pintype "passive"))
      (node (ref "R75") (pin "2") (pinfunction "2_2") (pintype "passive"))
      (node (ref "R77") (pin "2") (pinfunction "2_2") (pintype "passive"))
      (node (ref "R79") (pin "2") (pinfunction "2_2") (pintype "passive"))
      (node (ref "R81") (pin "2") (pinfunction "2_2") (pintype "passive"))
      (node (ref "R83") (pin "2") (pinfunction "2_2") (pintype "passive"))
      (node (ref "S1") (pin "6") (pinfunction "6_6") (pintype "passive"))
    )
    (net (code "309") (name "STATUS_EN") (class "Default")
      (node (ref "D106") (pin "C") (pinfunction "C_C") (pintype "passive"))
      (node (ref "R148") (pin "1") (pinfunction "1_1") (pintype "passive"))
      (node (ref "S1") (pin "5") (pinfunction "5_5") (pintype "passive"))
    )
    (net (code "310") (name "STOP") (class "Default")
      (node (ref "E4") (pin "13") (pinfunction "O_13") (pintype "open_collector"))
      (node (ref "U$2") (pin "DS2") (pinfunction "1_DS2") (pintype "bidirectional"))
    )
    (net (code "311") (name "SWITCH") (class "Default")
      (node (ref "D81") (pin "A") (pinfunction "A_A") (pintype "passive"))
      (node (ref "D85") (pin "C") (pinfunction "C_C") (pintype "passive"))
      (node (ref "R85") (pin "2") (pinfunction "2_2") (pintype "passive"))
      (node (ref "R86") (pin "2") (pinfunction "2_2") (pintype "passive"))
      (node (ref "U$2") (pin "DV2") (pinfunction "1_DV2") (pintype "bidirectional"))
    )
    (net (code "312") (name "TP4") (class "Default")
      (node (ref "E13") (pin "10") (pinfunction "I1_10") (pintype "input"))
      (node (ref "E13") (pin "9") (pinfunction "I0_9") (pintype "input"))
      (node (ref "U$2") (pin "CJ2") (pinfunction "1_CJ2") (pintype "bidirectional"))
    )
    (net (code "313") (name "TS1") (class "Default")
      (node (ref "E2") (pin "7") (pinfunction "I1_7") (pintype "input"))
      (node (ref "U$2") (pin "CK2") (pinfunction "1_CK2") (pintype "bidirectional"))
    )
    (net (code "314") (name "TS3") (class "Default")
      (node (ref "E2") (pin "5") (pinfunction "I1_5") (pintype "input"))
      (node (ref "U$2") (pin "CM2") (pinfunction "1_CM2") (pintype "bidirectional"))
    )
    (net (code "315") (name "TS4") (class "Default")
      (node (ref "E11") (pin "11") (pinfunction "I0_11") (pintype "input"))
      (node (ref "U$2") (pin "CP2") (pinfunction "1_CP2") (pintype "bidirectional"))
    )
    (net (code "316") (name "U_MODE") (class "Default")
      (node (ref "E13") (pin "4") (pinfunction "I0_4") (pintype "input"))
      (node (ref "U$2") (pin "DM2") (pinfunction "1_DM2") (pintype "bidirectional"))
    )
    (net (code "317") (name "VCC") (class "Default")
      (node (ref "C18") (pin "+") (pinfunction "+_+") (pintype "passive"))
      (node (ref "C19") (pin "+") (pinfunction "+_+") (pintype "passive"))
      (node (ref "C20") (pin "+") (pinfunction "+_+") (pintype "passive"))
      (node (ref "C22") (pin "1") (pinfunction "1_1") (pintype "passive"))
      (node (ref "C23") (pin "1") (pinfunction "1_1") (pintype "passive"))
      (node (ref "C24") (pin "1") (pinfunction "1_1") (pintype "passive"))
      (node (ref "C25") (pin "1") (pinfunction "1_1") (pintype "passive"))
      (node (ref "C26") (pin "1") (pinfunction "1_1") (pintype "passive"))
      (node (ref "C27") (pin "1") (pinfunction "1_1") (pintype "passive"))
      (node (ref "C28") (pin "1") (pinfunction "1_1") (pintype "passive"))
      (node (ref "C29") (pin "1") (pinfunction "1_1") (pintype "passive"))
      (node (ref "C30") (pin "1") (pinfunction "1_1") (pintype "passive"))
      (node (ref "C31") (pin "1") (pinfunction "1_1") (pintype "passive"))
      (node (ref "C32") (pin "1") (pinfunction "1_1") (pintype "passive"))
      (node (ref "C33") (pin "1") (pinfunction "1_1") (pintype "passive"))
      (node (ref "C34") (pin "1") (pinfunction "1_1") (pintype "passive"))
      (node (ref "C35") (pin "1") (pinfunction "1_1") (pintype "passive"))
      (node (ref "C36") (pin "1") (pinfunction "1_1") (pintype "passive"))
      (node (ref "C37") (pin "1") (pinfunction "1_1") (pintype "passive"))
      (node (ref "C38") (pin "1") (pinfunction "1_1") (pintype "passive"))
      (node (ref "C39") (pin "1") (pinfunction "1_1") (pintype "passive"))
      (node (ref "R1") (pin "2") (pinfunction "2_2") (pintype "passive"))
      (node (ref "R10") (pin "2") (pinfunction "2_2") (pintype "passive"))
      (node (ref "R100") (pin "2") (pinfunction "2_2") (pintype "passive"))
      (node (ref "R102") (pin "2") (pinfunction "2_2") (pintype "passive"))
      (node (ref "R104") (pin "2") (pinfunction "2_2") (pintype "passive"))
      (node (ref "R106") (pin "2") (pinfunction "2_2") (pintype "passive"))
      (node (ref "R108") (pin "2") (pinfunction "2_2") (pintype "passive"))
      (node (ref "R11") (pin "2") (pinfunction "2_2") (pintype "passive"))
      (node (ref "R110") (pin "2") (pinfunction "2_2") (pintype "passive"))
      (node (ref "R112") (pin "2") (pinfunction "2_2") (pintype "passive"))
      (node (ref "R114") (pin "2") (pinfunction "2_2") (pintype "passive"))
      (node (ref "R116") (pin "2") (pinfunction "2_2") (pintype "passive"))
      (node (ref "R118") (pin "2") (pinfunction "2_2") (pintype "passive"))
      (node (ref "R12") (pin "2") (pinfunction "2_2") (pintype "passive"))
      (node (ref "R120") (pin "2") (pinfunction "2_2") (pintype "passive"))
      (node (ref "R122") (pin "2") (pinfunction "2_2") (pintype "passive"))
      (node (ref "R124") (pin "2") (pinfunction "2_2") (pintype "passive"))
      (node (ref "R126") (pin "2") (pinfunction "2_2") (pintype "passive"))
      (node (ref "R142") (pin "2") (pinfunction "2_2") (pintype "passive"))
      (node (ref "R143") (pin "2") (pinfunction "2_2") (pintype "passive"))
      (node (ref "R144") (pin "2") (pinfunction "2_2") (pintype "passive"))
      (node (ref "R145") (pin "2") (pinfunction "2_2") (pintype "passive"))
      (node (ref "R146") (pin "2") (pinfunction "2_2") (pintype "passive"))
      (node (ref "R147") (pin "2") (pinfunction "2_2") (pintype "passive"))
      (node (ref "R151") (pin "2") (pinfunction "2_2") (pintype "passive"))
      (node (ref "R152") (pin "2") (pinfunction "2_2") (pintype "passive"))
      (node (ref "R155") (pin "2") (pinfunction "2_2") (pintype "passive"))
      (node (ref "R156") (pin "2") (pinfunction "2_2") (pintype "passive"))
      (node (ref "R161") (pin "2") (pinfunction "2_2") (pintype "passive"))
      (node (ref "R162") (pin "2") (pinfunction "2_2") (pintype "passive"))
      (node (ref "R163") (pin "2") (pinfunction "2_2") (pintype "passive"))
      (node (ref "R164") (pin "2") (pinfunction "2_2") (pintype "passive"))
      (node (ref "R165") (pin "2") (pinfunction "2_2") (pintype "passive"))
      (node (ref "R167") (pin "2") (pinfunction "2_2") (pintype "passive"))
      (node (ref "R169") (pin "1") (pinfunction "1_1") (pintype "passive"))
      (node (ref "R170") (pin "2") (pinfunction "2_2") (pintype "passive"))
      (node (ref "R175") (pin "2") (pinfunction "2_2") (pintype "passive"))
      (node (ref "R2") (pin "2") (pinfunction "2_2") (pintype "passive"))
      (node (ref "R3") (pin "2") (pinfunction "2_2") (pintype "passive"))
      (node (ref "R4") (pin "2") (pinfunction "2_2") (pintype "passive"))
      (node (ref "R5") (pin "2") (pinfunction "2_2") (pintype "passive"))
      (node (ref "R6") (pin "2") (pinfunction "2_2") (pintype "passive"))
      (node (ref "R7") (pin "2") (pinfunction "2_2") (pintype "passive"))
      (node (ref "R8") (pin "2") (pinfunction "2_2") (pintype "passive"))
      (node (ref "R88") (pin "2") (pinfunction "2_2") (pintype "passive"))
      (node (ref "R9") (pin "2") (pinfunction "2_2") (pintype "passive"))
      (node (ref "R90") (pin "2") (pinfunction "2_2") (pintype "passive"))
      (node (ref "R92") (pin "2") (pinfunction "2_2") (pintype "passive"))
      (node (ref "R94") (pin "2") (pinfunction "2_2") (pintype "passive"))
      (node (ref "R96") (pin "2") (pinfunction "2_2") (pintype "passive"))
      (node (ref "R98") (pin "2") (pinfunction "2_2") (pintype "passive"))
      (node (ref "U$2") (pin "AA2") (pinfunction "1_AA2") (pintype "bidirectional"))
      (node (ref "U$2") (pin "BA2") (pinfunction "1_BA2") (pintype "bidirectional"))
      (node (ref "U$2") (pin "CA2") (pinfunction "1_CA2") (pintype "bidirectional"))
    )
    (net (code "318") (name "WILL_START") (class "Default")
      (node (ref "E10") (pin "2") (pinfunction "O_2") (pintype "output"))
      (node (ref "E11") (pin "7") (pinfunction "I1_7") (pintype "input"))
      (node (ref "E12") (pin "13") (pinfunction "I1_13") (pintype "input"))
      (node (ref "R153") (pin "1") (pinfunction "1_1") (pintype "passive"))
      (node (ref "R175") (pin "1") (pinfunction "1_1") (pintype "passive"))
    )
    (net (code "319") (name "unconnected-(S2\\-A3-PadL3)") (class "Default")
      (node (ref "S2\\") (pin "L3") (pinfunction "A3_L3") (pintype "bidirectional"))
    )
    (net (code "320") (name "unconnected-(S2\\-B3-PadR3)") (class "Default")
      (node (ref "S2\\") (pin "R3") (pinfunction "B3_R3") (pintype "bidirectional"))
    )
    (net (code "321") (name "unconnected-(S3-PadA3)") (class "Default")
      (node (ref "S3") (pin "A3") (pinfunction "A3_A3") (pintype "bidirectional"))
    )
    (net (code "322") (name "unconnected-(S4-PadA3)") (class "Default")
      (node (ref "S4") (pin "A3") (pinfunction "A3_A3") (pintype "bidirectional"))
    )
    (net (code "323") (name "unconnected-(S5-PadA3)") (class "Default")
      (node (ref "S5") (pin "A3") (pinfunction "A3_A3") (pintype "bidirectional"))
    )
    (net (code "324") (name "unconnected-(S6-PadA3)") (class "Default")
      (node (ref "S6") (pin "A3") (pinfunction "A3_A3") (pintype "bidirectional"))
    )
    (net (code "325") (name "unconnected-(S7-PadA3)") (class "Default")
      (node (ref "S7") (pin "A3") (pinfunction "A3_A3") (pintype "bidirectional"))
    )
    (net (code "326") (name "unconnected-(S8-PadA3)") (class "Default")
      (node (ref "S8") (pin "A3") (pinfunction "A3_A3") (pintype "bidirectional"))
    )
    (net (code "327") (name "unconnected-(S9-A3-PadL3)") (class "Default")
      (node (ref "S9") (pin "L3") (pinfunction "A3_L3") (pintype "bidirectional"))
    )
    (net (code "328") (name "unconnected-(S9-B3-PadR3)") (class "Default")
      (node (ref "S9") (pin "R3") (pinfunction "B3_R3") (pintype "bidirectional"))
    )
    (net (code "329") (name "unconnected-(S10-A3-PadL3)") (class "Default")
      (node (ref "S10") (pin "L3") (pinfunction "A3_L3") (pintype "bidirectional"))
    )
    (net (code "330") (name "unconnected-(S10-B3-PadR3)") (class "Default")
      (node (ref "S10") (pin "R3") (pinfunction "B3_R3") (pintype "bidirectional"))
    )
    (net (code "331") (name "unconnected-(S11-A3-PadL3)") (class "Default")
      (node (ref "S11") (pin "L3") (pinfunction "A3_L3") (pintype "bidirectional"))
    )
    (net (code "332") (name "unconnected-(S11-B3-PadR3)") (class "Default")
      (node (ref "S11") (pin "R3") (pinfunction "B3_R3") (pintype "bidirectional"))
    )
    (net (code "333") (name "unconnected-(S12-A3-PadL3)") (class "Default")
      (node (ref "S12") (pin "L3") (pinfunction "A3_L3") (pintype "bidirectional"))
    )
    (net (code "334") (name "unconnected-(S12-B3-PadR3)") (class "Default")
      (node (ref "S12") (pin "R3") (pinfunction "B3_R3") (pintype "bidirectional"))
    )
    (net (code "335") (name "unconnected-(S13-A3-PadL3)") (class "Default")
      (node (ref "S13") (pin "L3") (pinfunction "A3_L3") (pintype "bidirectional"))
    )
    (net (code "336") (name "unconnected-(S13-B3-PadR3)") (class "Default")
      (node (ref "S13") (pin "R3") (pinfunction "B3_R3") (pintype "bidirectional"))
    )
    (net (code "337") (name "unconnected-(S14-A3-PadL3)") (class "Default")
      (node (ref "S14") (pin "L3") (pinfunction "A3_L3") (pintype "bidirectional"))
    )
    (net (code "338") (name "unconnected-(S14-B3-PadR3)") (class "Default")
      (node (ref "S14") (pin "R3") (pinfunction "B3_R3") (pintype "bidirectional"))
    )
    (net (code "339") (name "unconnected-(S15-A3-PadL3)") (class "Default")
      (node (ref "S15") (pin "L3") (pinfunction "A3_L3") (pintype "bidirectional"))
    )
    (net (code "340") (name "unconnected-(S15-B3-PadR3)") (class "Default")
      (node (ref "S15") (pin "R3") (pinfunction "B3_R3") (pintype "bidirectional"))
    )
    (net (code "341") (name "unconnected-(S16-A3-PadL3)") (class "Default")
      (node (ref "S16") (pin "L3") (pinfunction "A3_L3") (pintype "bidirectional"))
    )
    (net (code "342") (name "unconnected-(S16-B3-PadR3)") (class "Default")
      (node (ref "S16") (pin "R3") (pinfunction "B3_R3") (pintype "bidirectional"))
    )
    (net (code "343") (name "unconnected-(S17-A3-PadL3)") (class "Default")
      (node (ref "S17") (pin "L3") (pinfunction "A3_L3") (pintype "bidirectional"))
    )
    (net (code "344") (name "unconnected-(S17-B3-PadR3)") (class "Default")
      (node (ref "S17") (pin "R3") (pinfunction "B3_R3") (pintype "bidirectional"))
    )
    (net (code "345") (name "unconnected-(S18-A3-PadL3)") (class "Default")
      (node (ref "S18") (pin "L3") (pinfunction "A3_L3") (pintype "bidirectional"))
    )
    (net (code "346") (name "unconnected-(S18-B3-PadR3)") (class "Default")
      (node (ref "S18") (pin "R3") (pinfunction "B3_R3") (pintype "bidirectional"))
    )
    (net (code "347") (name "unconnected-(S19-A3-PadL3)") (class "Default")
      (node (ref "S19") (pin "L3") (pinfunction "A3_L3") (pintype "bidirectional"))
    )
    (net (code "348") (name "unconnected-(S19-B3-PadR3)") (class "Default")
      (node (ref "S19") (pin "R3") (pinfunction "B3_R3") (pintype "bidirectional"))
    )
    (net (code "349") (name "unconnected-(S20-A3-PadL3)") (class "Default")
      (node (ref "S20") (pin "L3") (pinfunction "A3_L3") (pintype "bidirectional"))
    )
    (net (code "350") (name "unconnected-(S20-B3-PadR3)") (class "Default")
      (node (ref "S20") (pin "R3") (pinfunction "B3_R3") (pintype "bidirectional"))
    )
    (net (code "351") (name "unconnected-(S21-A3-PadL3)") (class "Default")
      (node (ref "S21") (pin "L3") (pinfunction "A3_L3") (pintype "bidirectional"))
    )
    (net (code "352") (name "unconnected-(S21-B3-PadR3)") (class "Default")
      (node (ref "S21") (pin "R3") (pinfunction "B3_R3") (pintype "bidirectional"))
    )
    (net (code "353") (name "unconnected-(S22-A3-PadL3)") (class "Default")
      (node (ref "S22") (pin "L3") (pinfunction "A3_L3") (pintype "bidirectional"))
    )
    (net (code "354") (name "unconnected-(S22-B3-PadR3)") (class "Default")
      (node (ref "S22") (pin "R3") (pinfunction "B3_R3") (pintype "bidirectional"))
    )
    (net (code "355") (name "~{RUN}") (class "Default")
      (node (ref "E11") (pin "6") (pinfunction "I0_6") (pintype "input"))
      (node (ref "E9") (pin "1") (pinfunction "I_1") (pintype "input"))
      (node (ref "U$2") (pin "BU2") (pinfunction "1_BU2") (pintype "bidirectional"))
    )
  )
)
